# oresat-gps-card.net
KiCad netlist of a schematic drawn in EAGLE
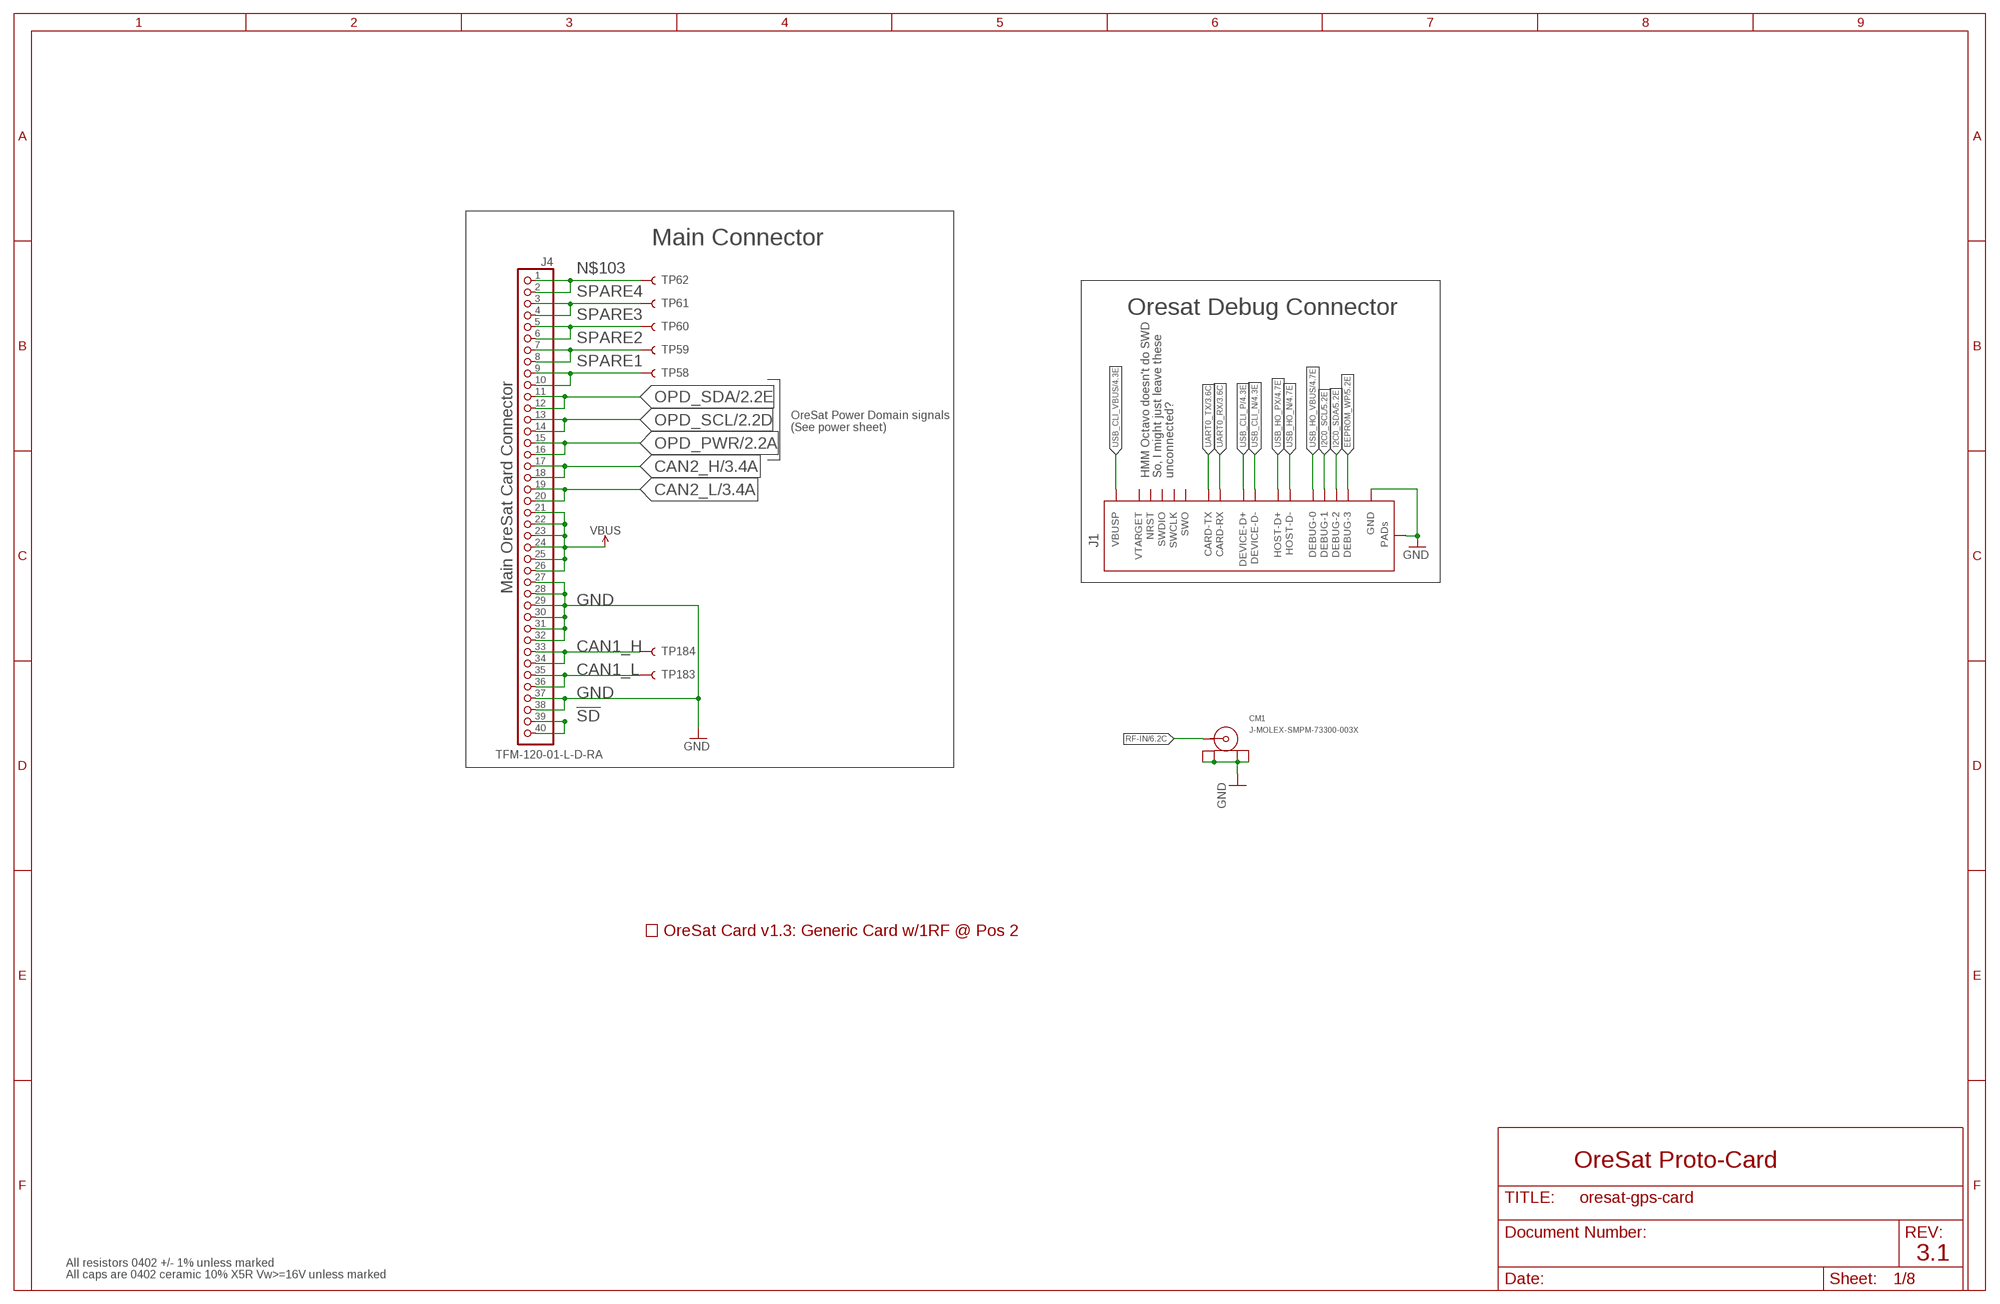
[diagram p0: schematic, sheet 1]
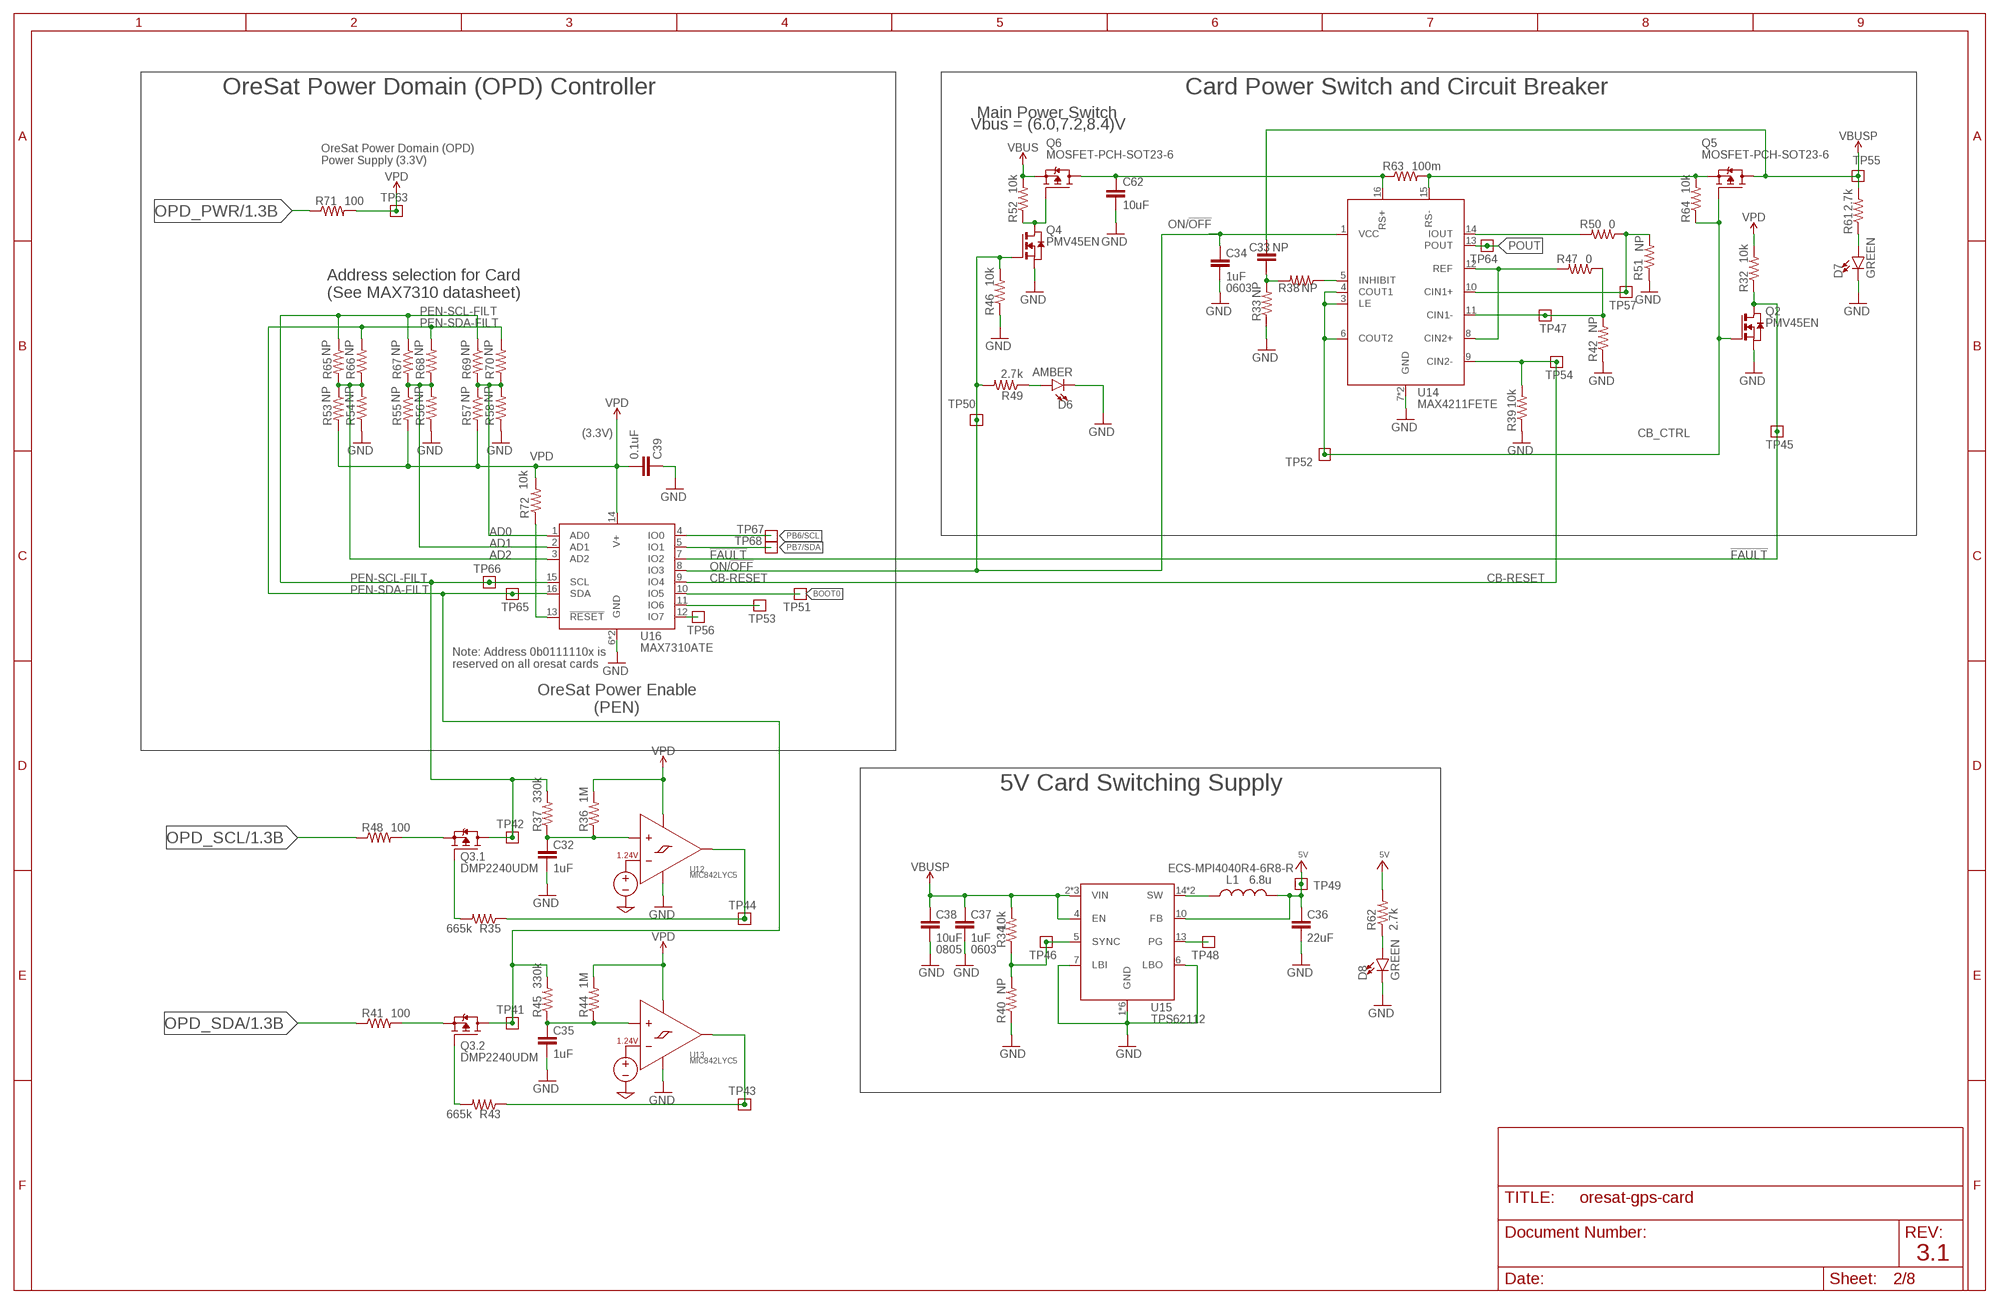
[diagram p1: schematic, sheet 2]
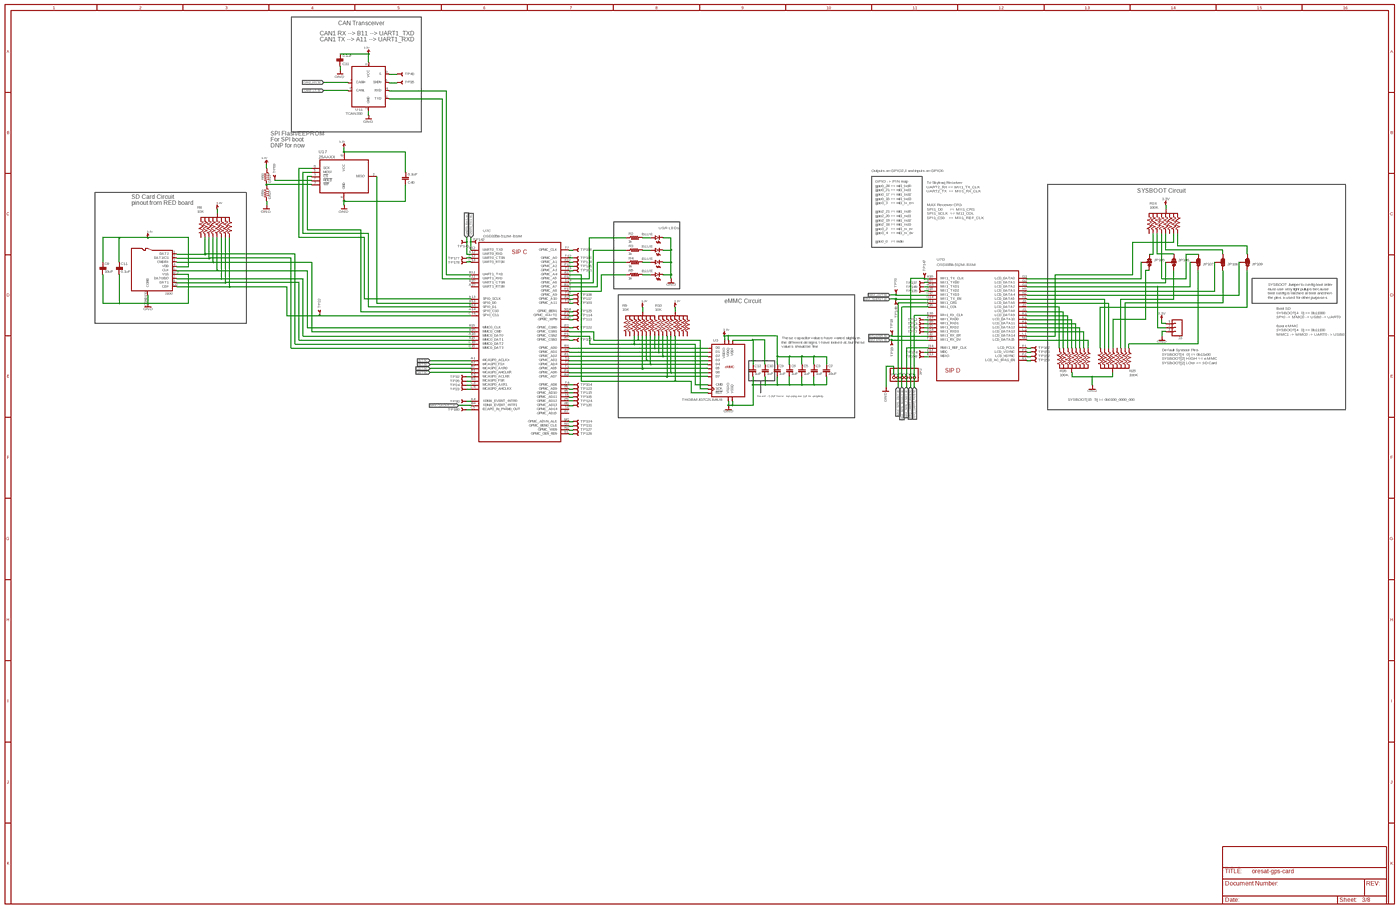
[diagram p2: schematic, sheet 3, overview]
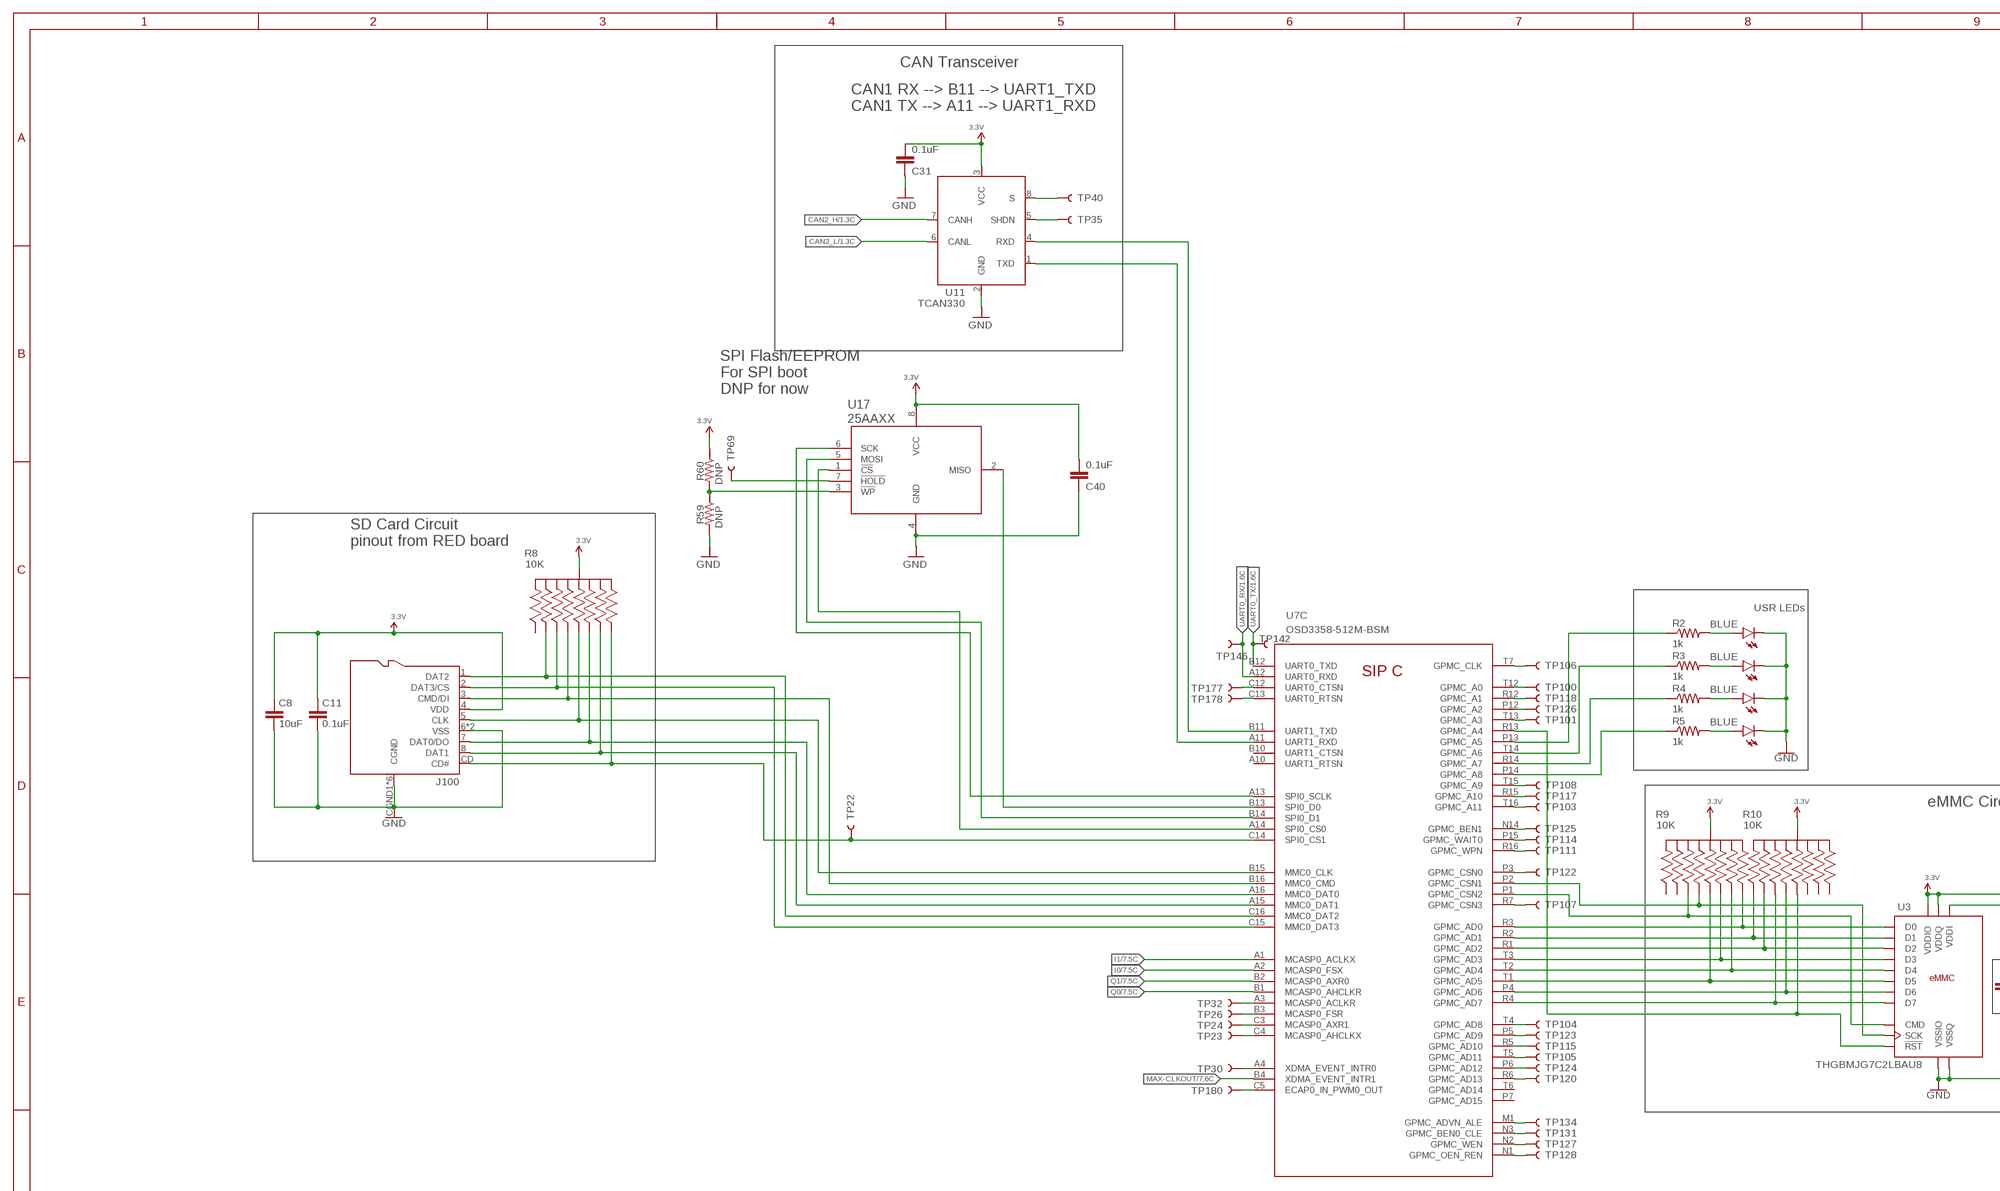
[diagram p3: schematic, sheet 3, part 1 of 4]
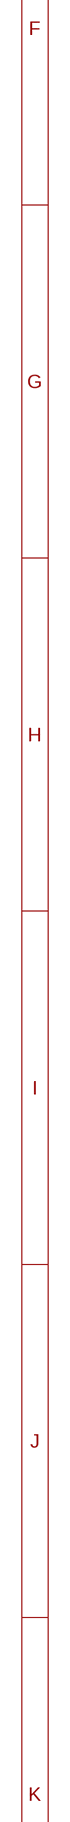
[diagram p4: schematic, sheet 3, part 2 of 4]
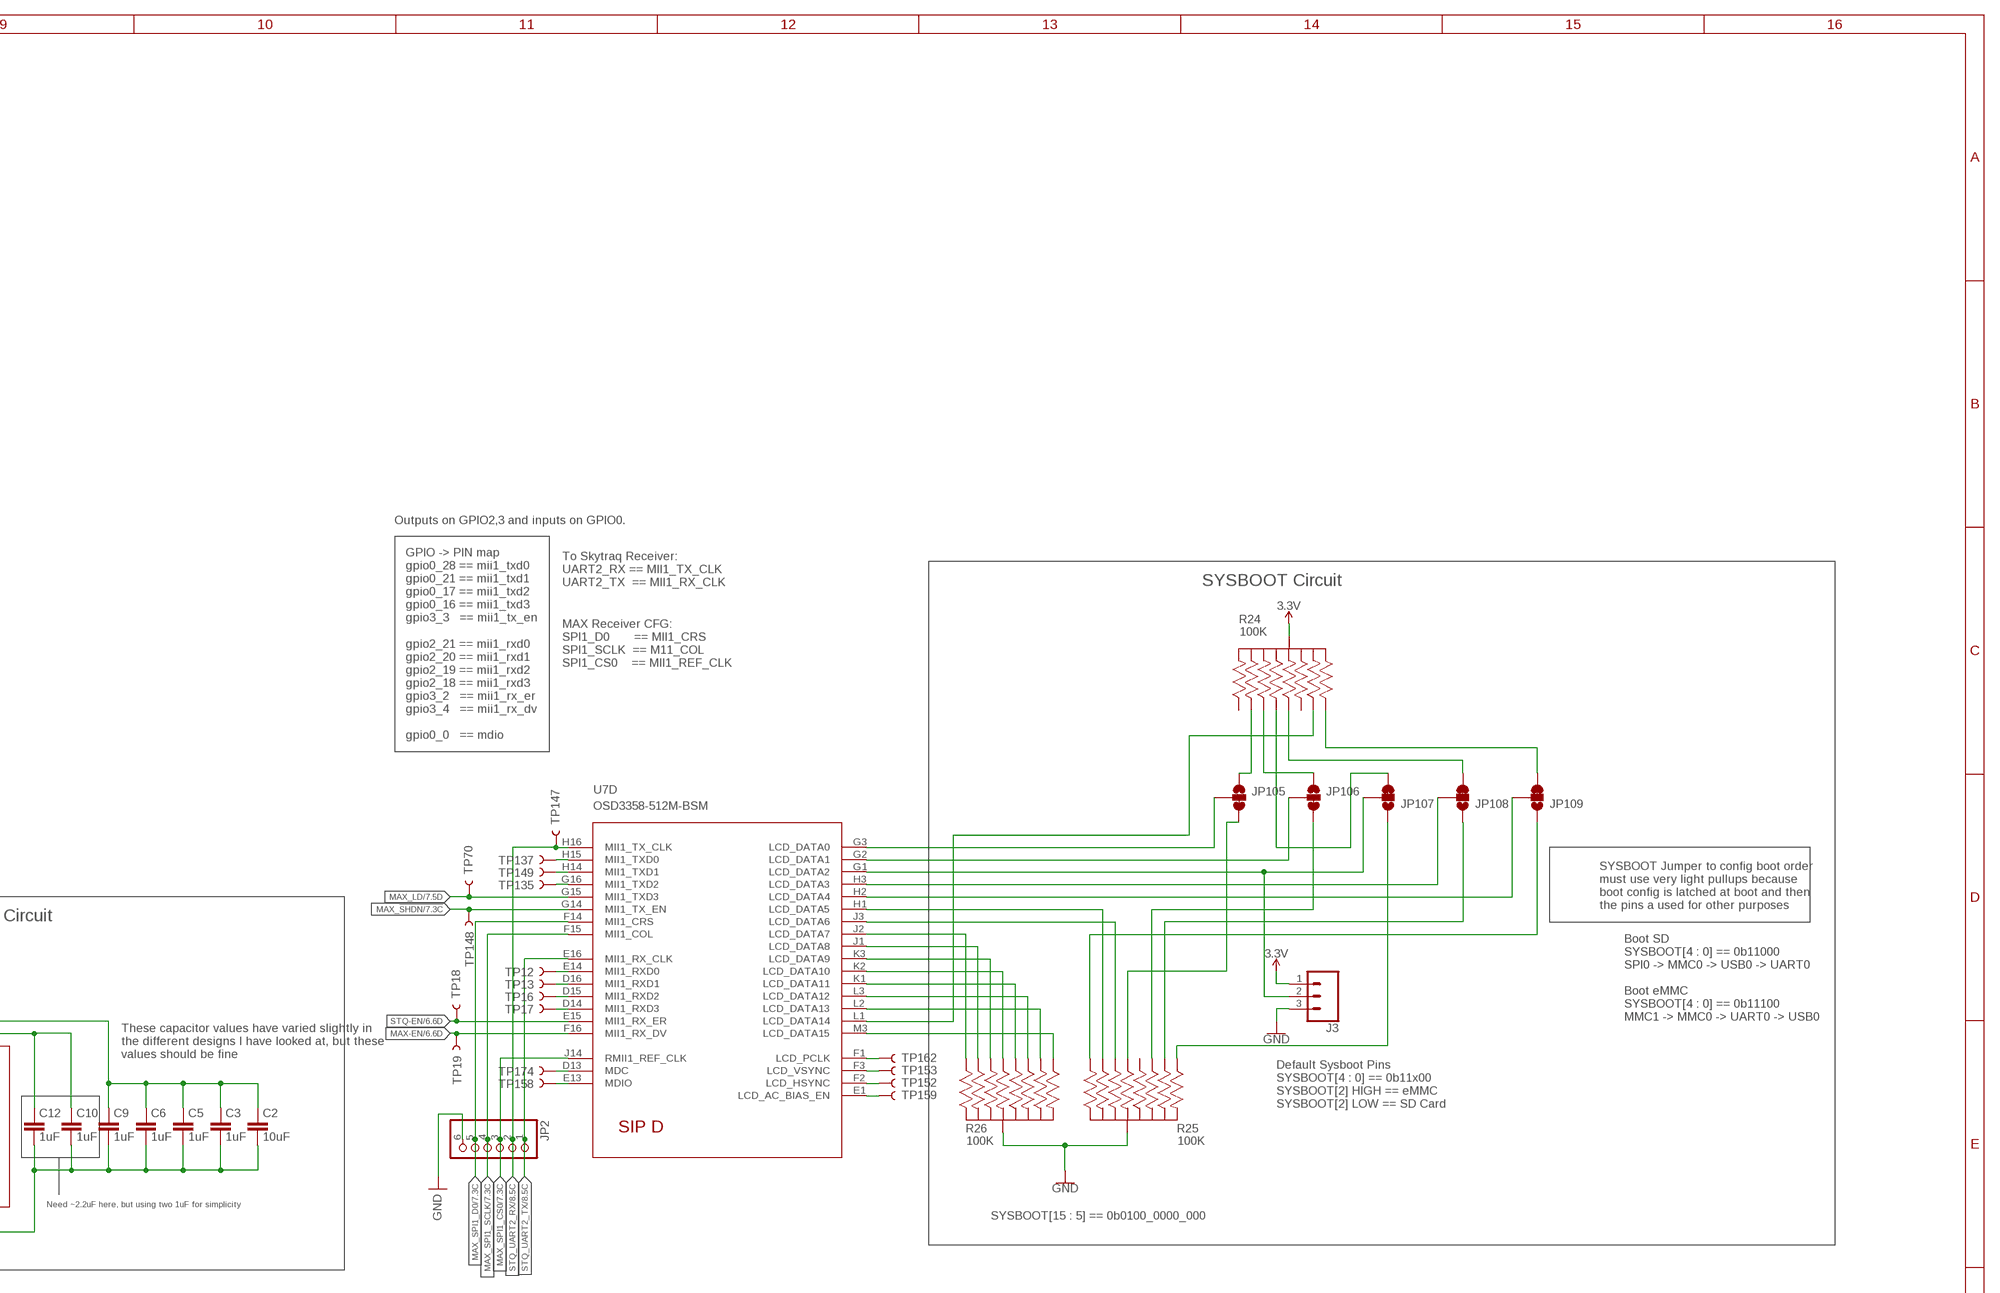
[diagram p5: schematic, sheet 3, part 3 of 4]
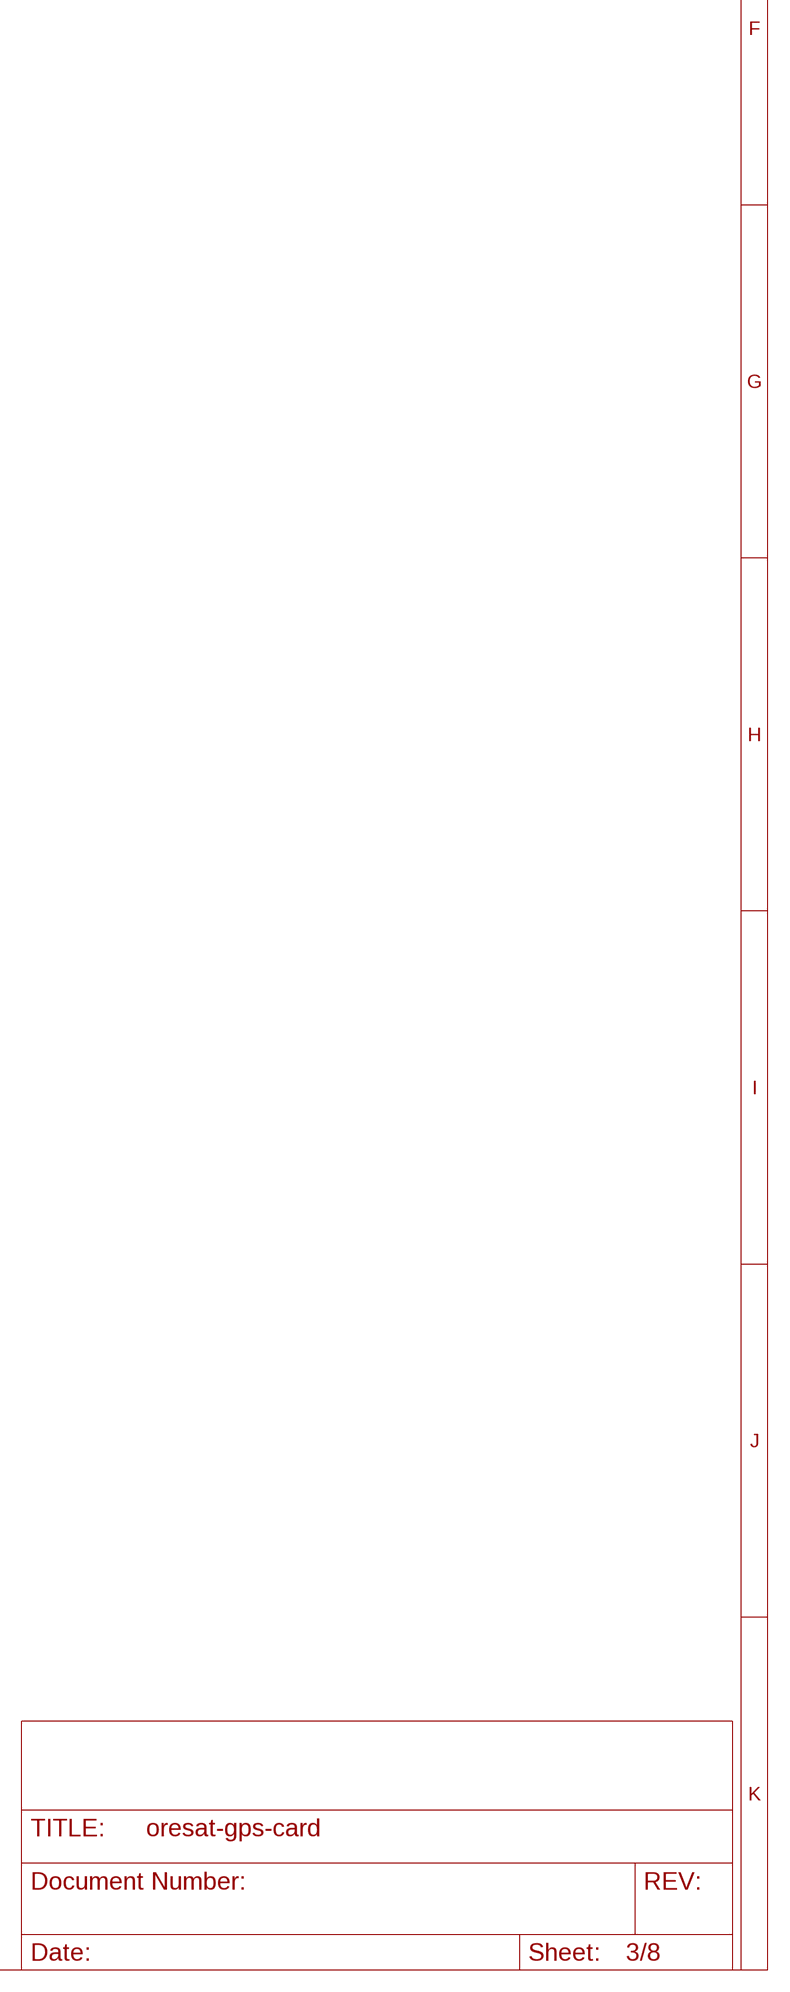
[diagram p6: schematic, sheet 3, part 4 of 4]
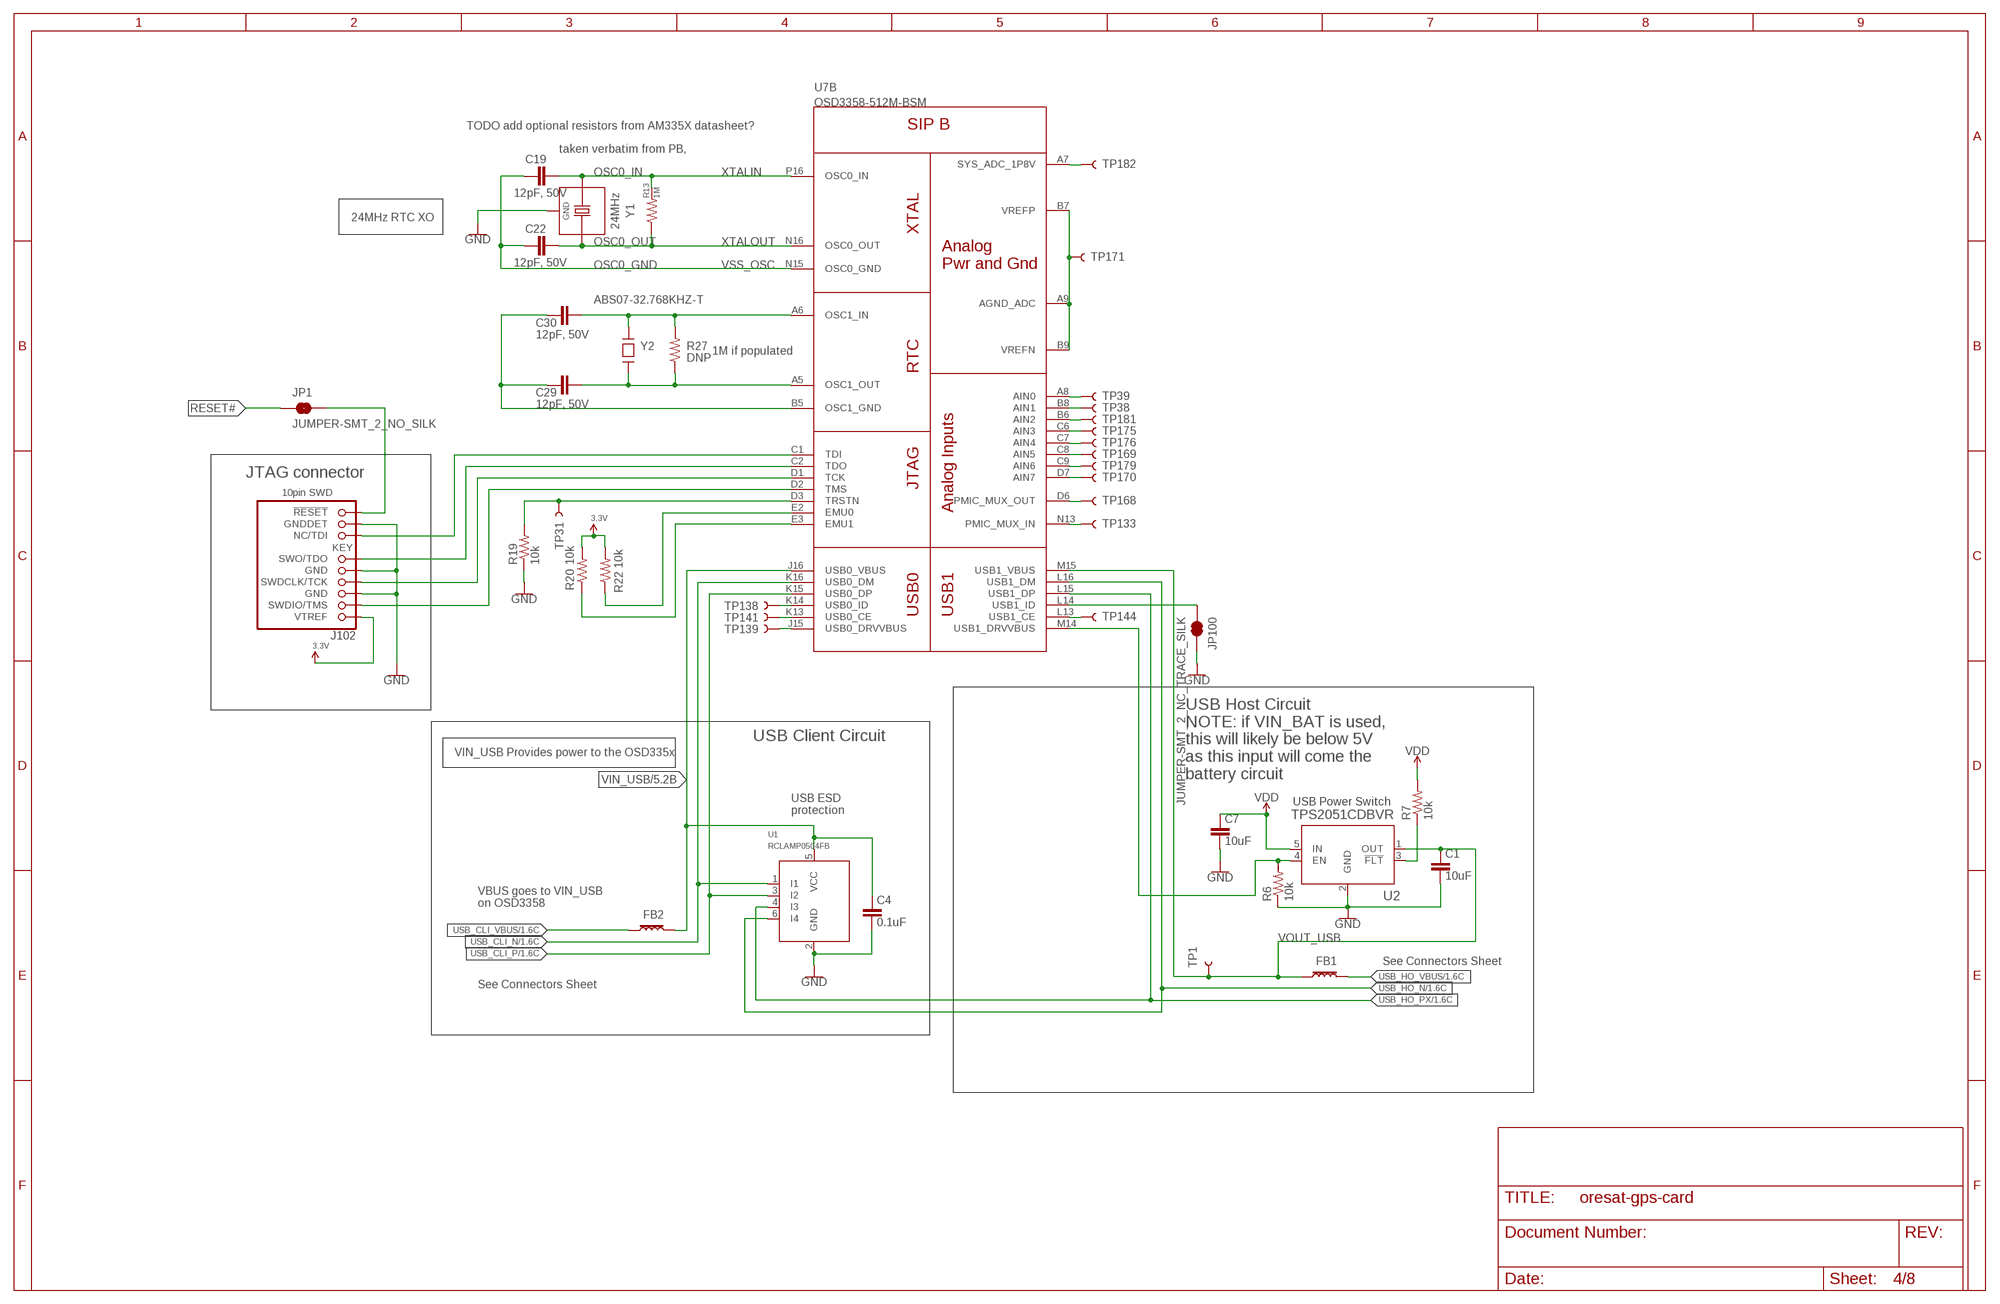
[diagram p7: schematic, sheet 4]
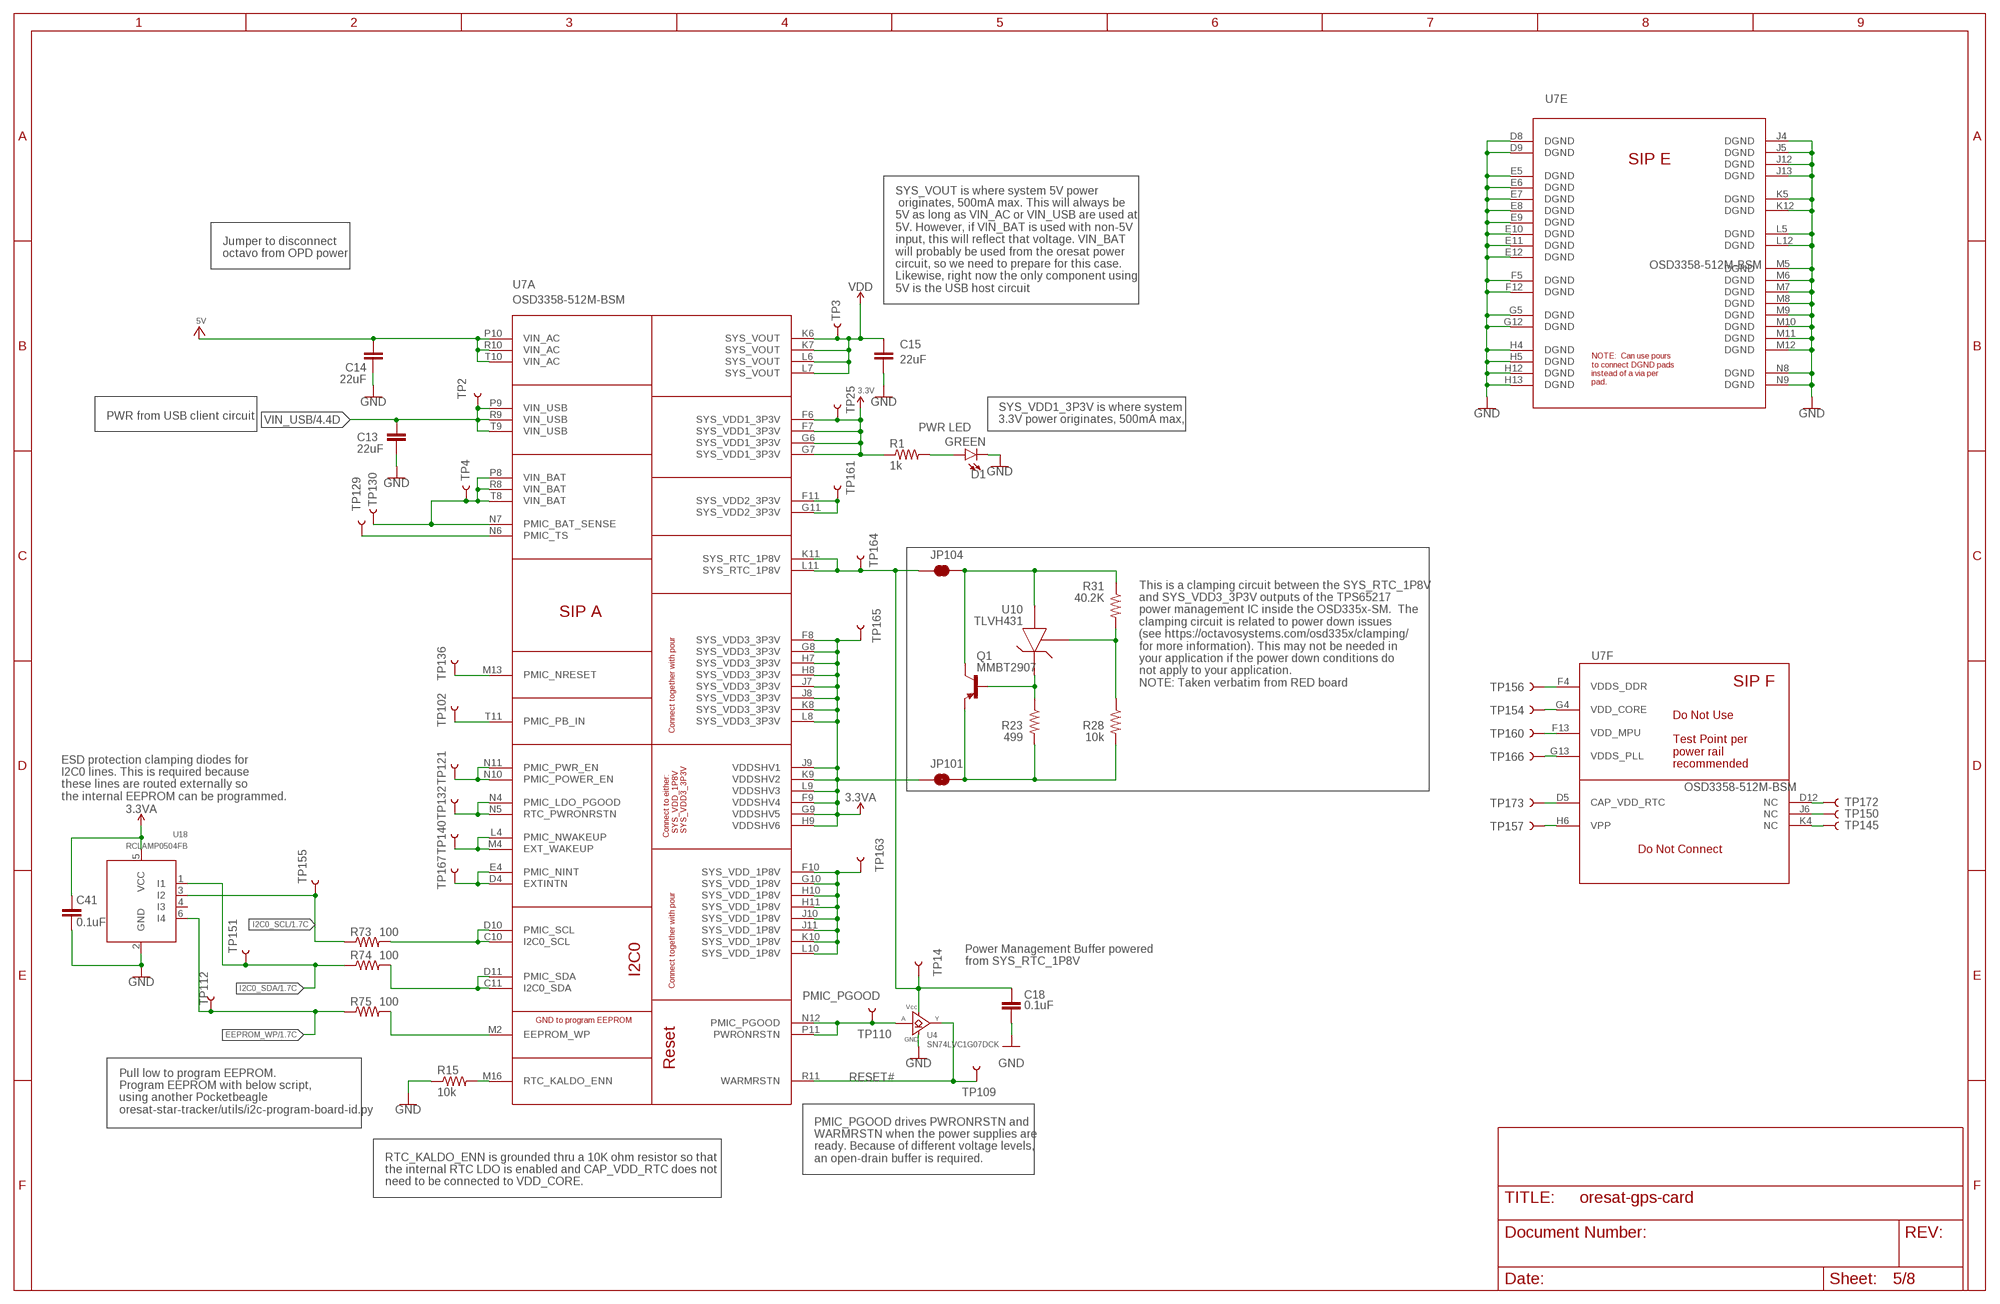
[diagram p8: schematic, sheet 5]
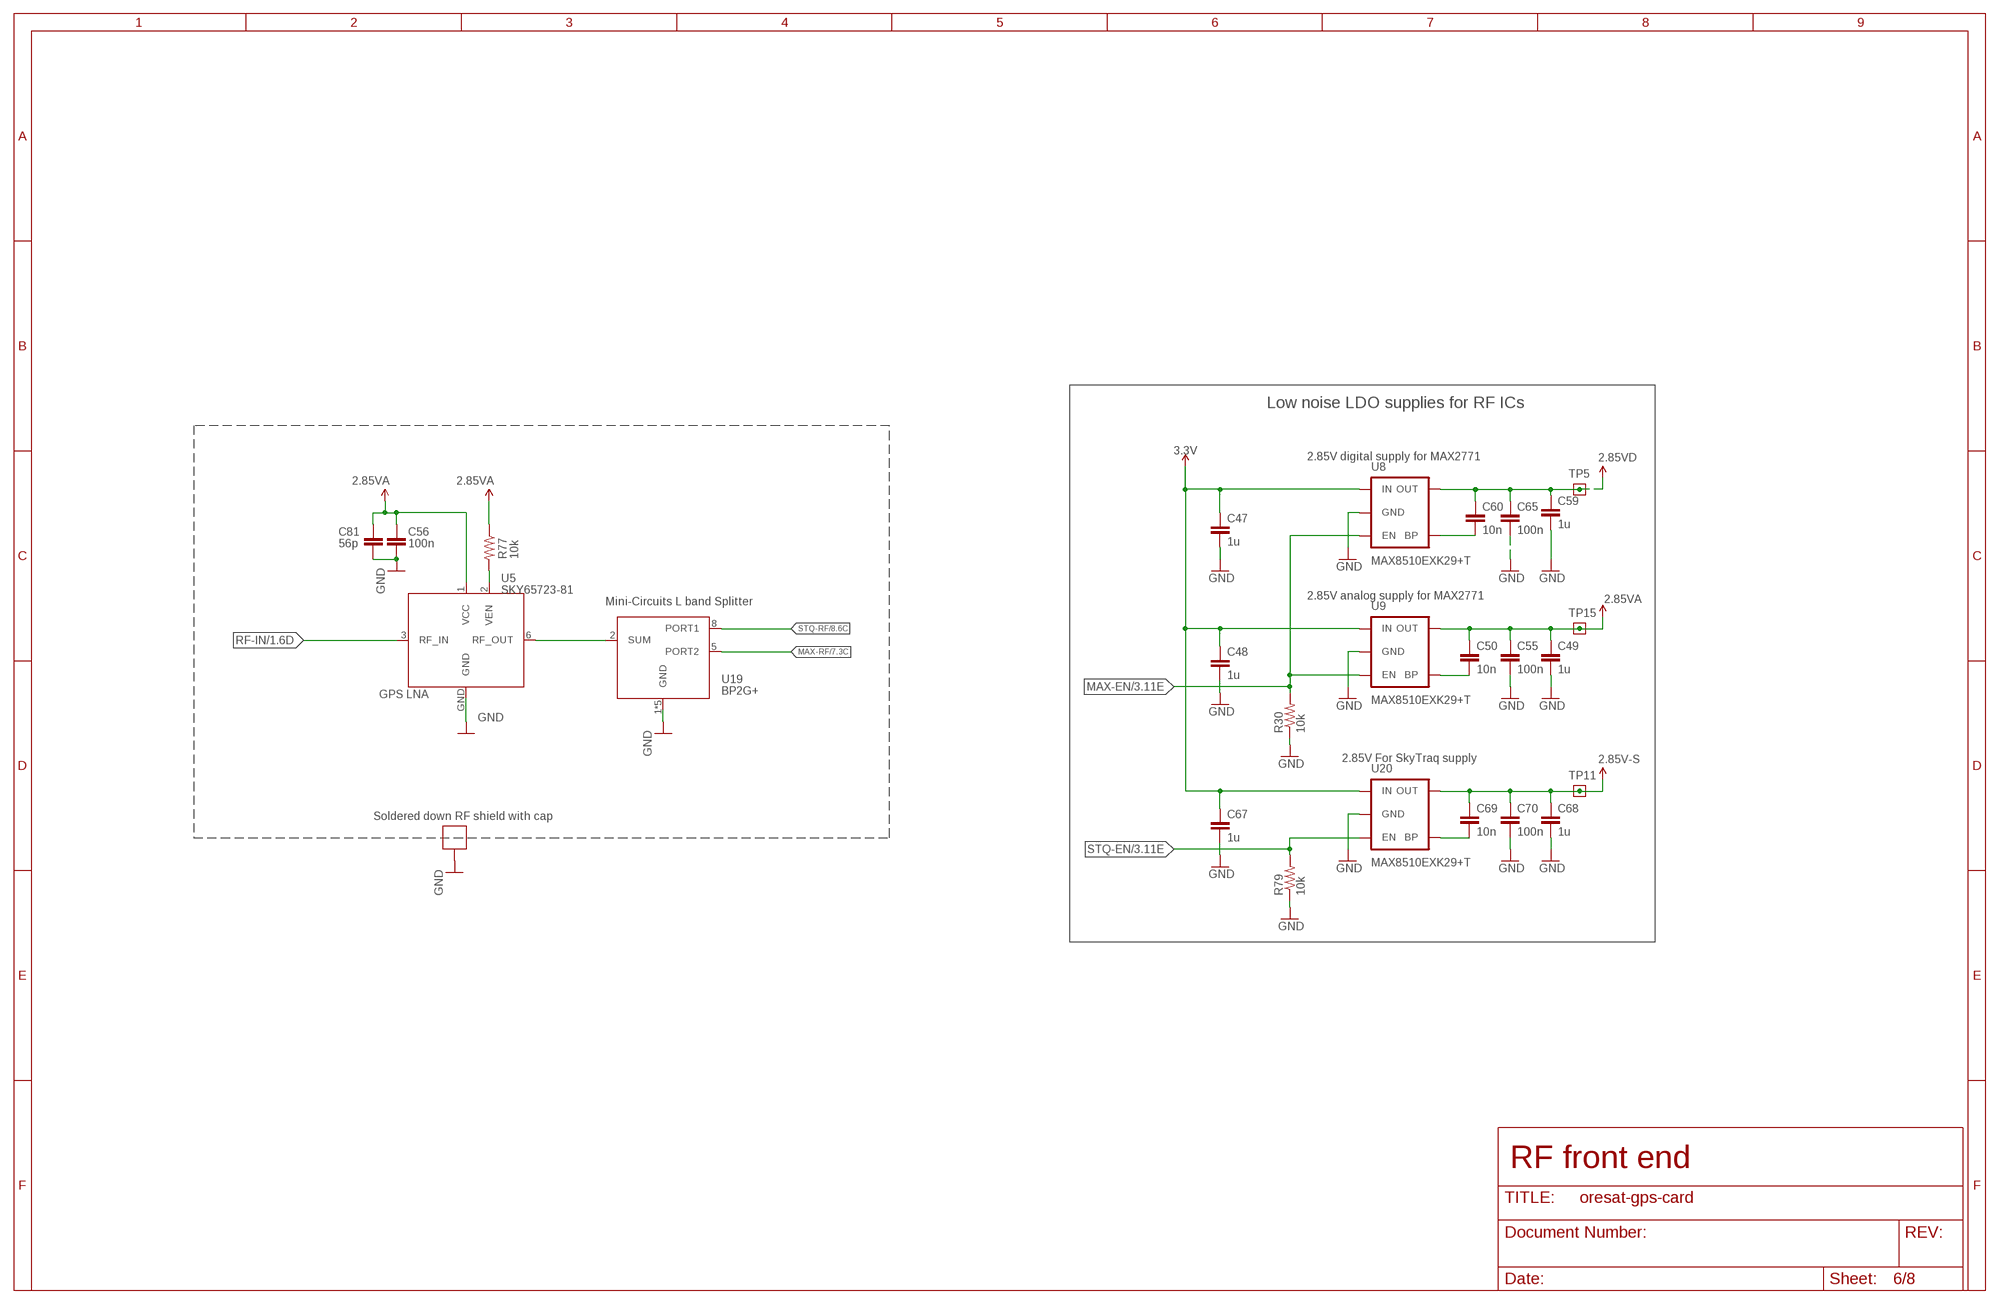
[diagram p9: schematic, sheet 6]
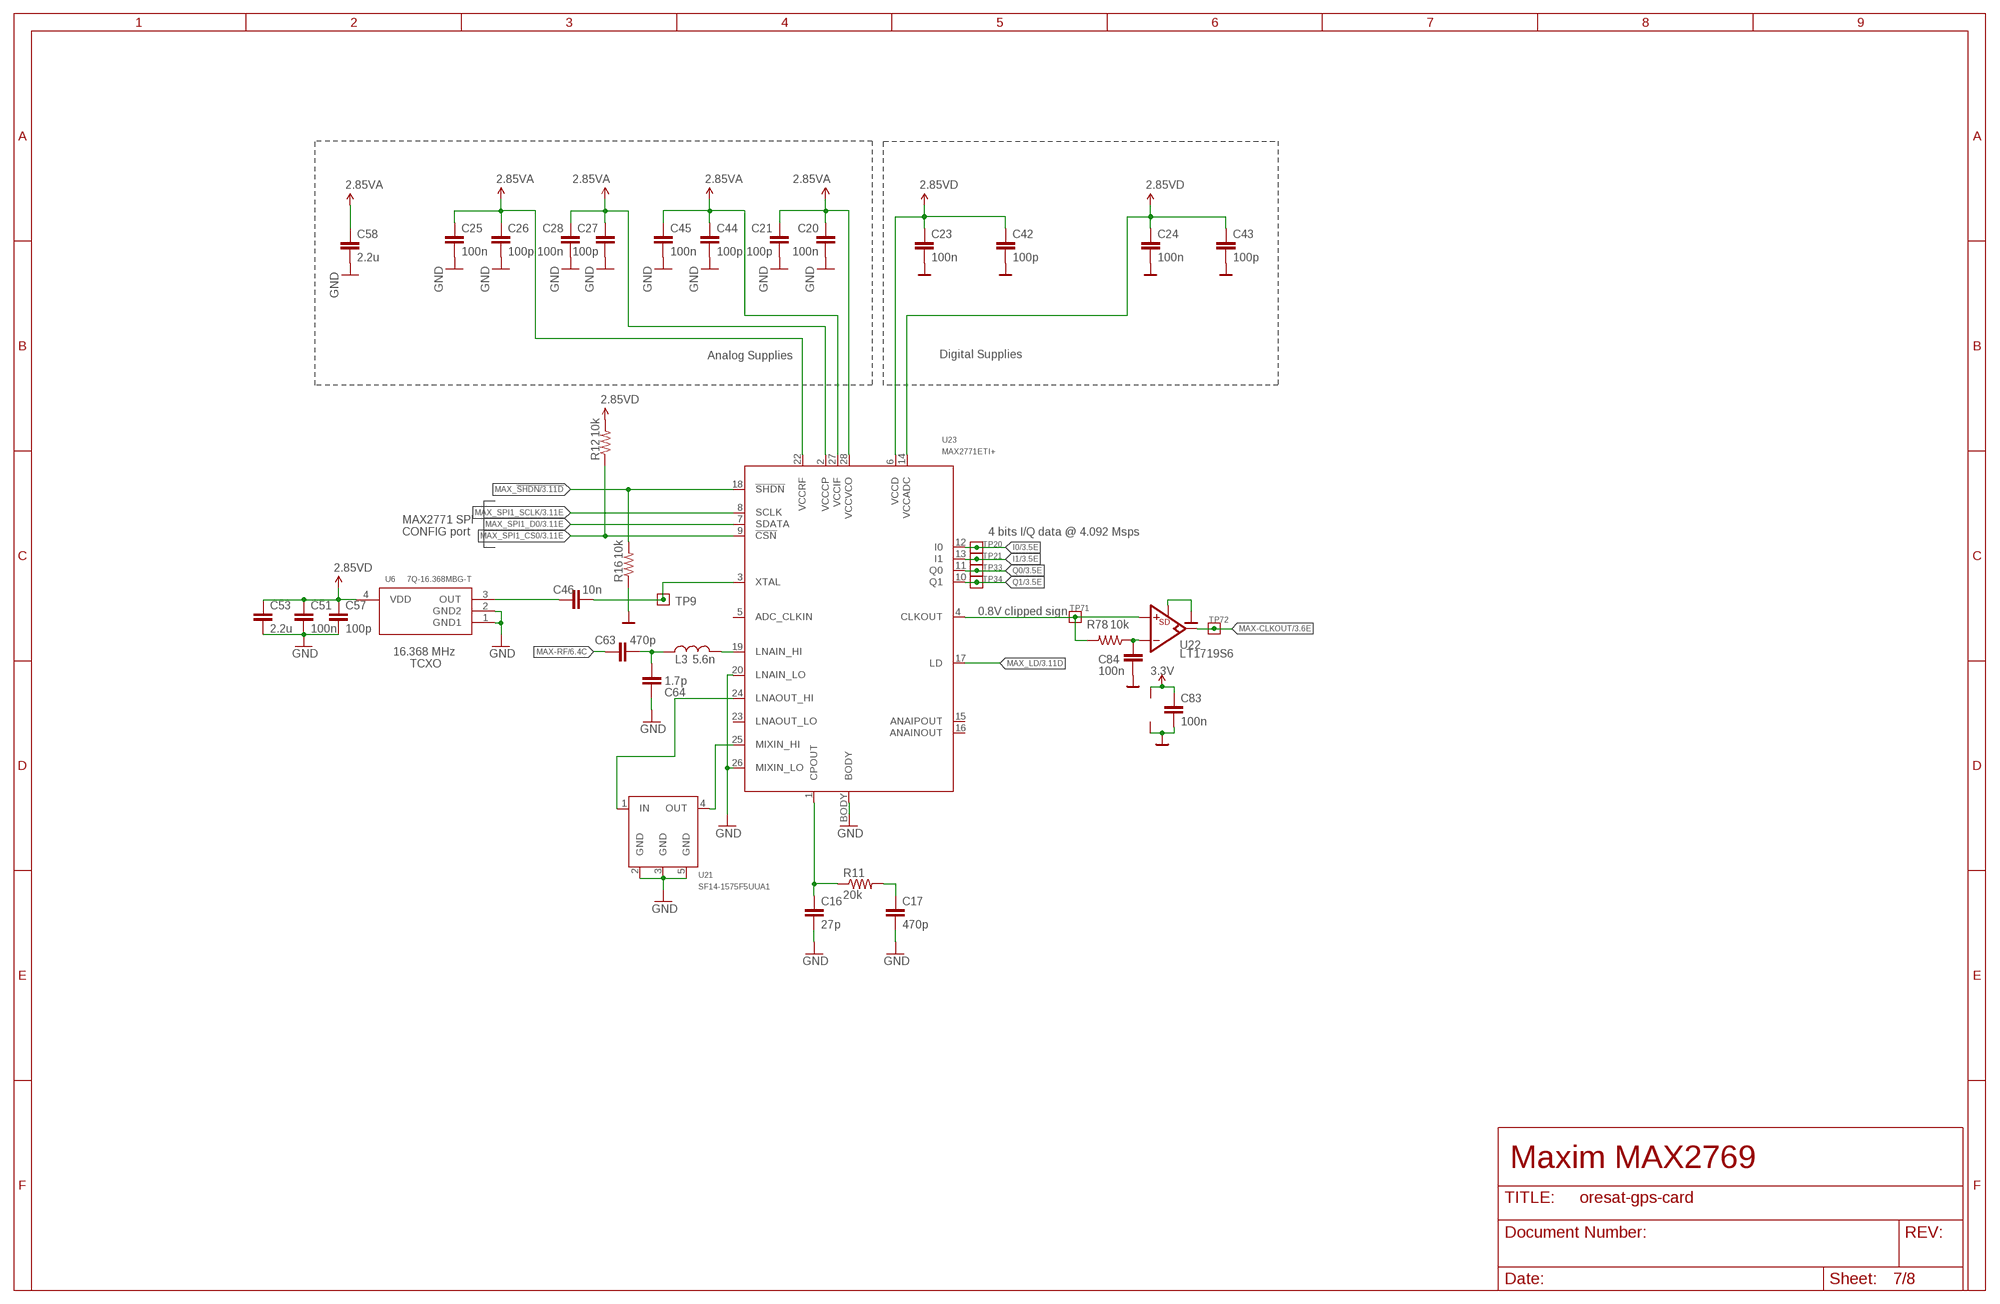
[diagram p10: schematic, sheet 7]
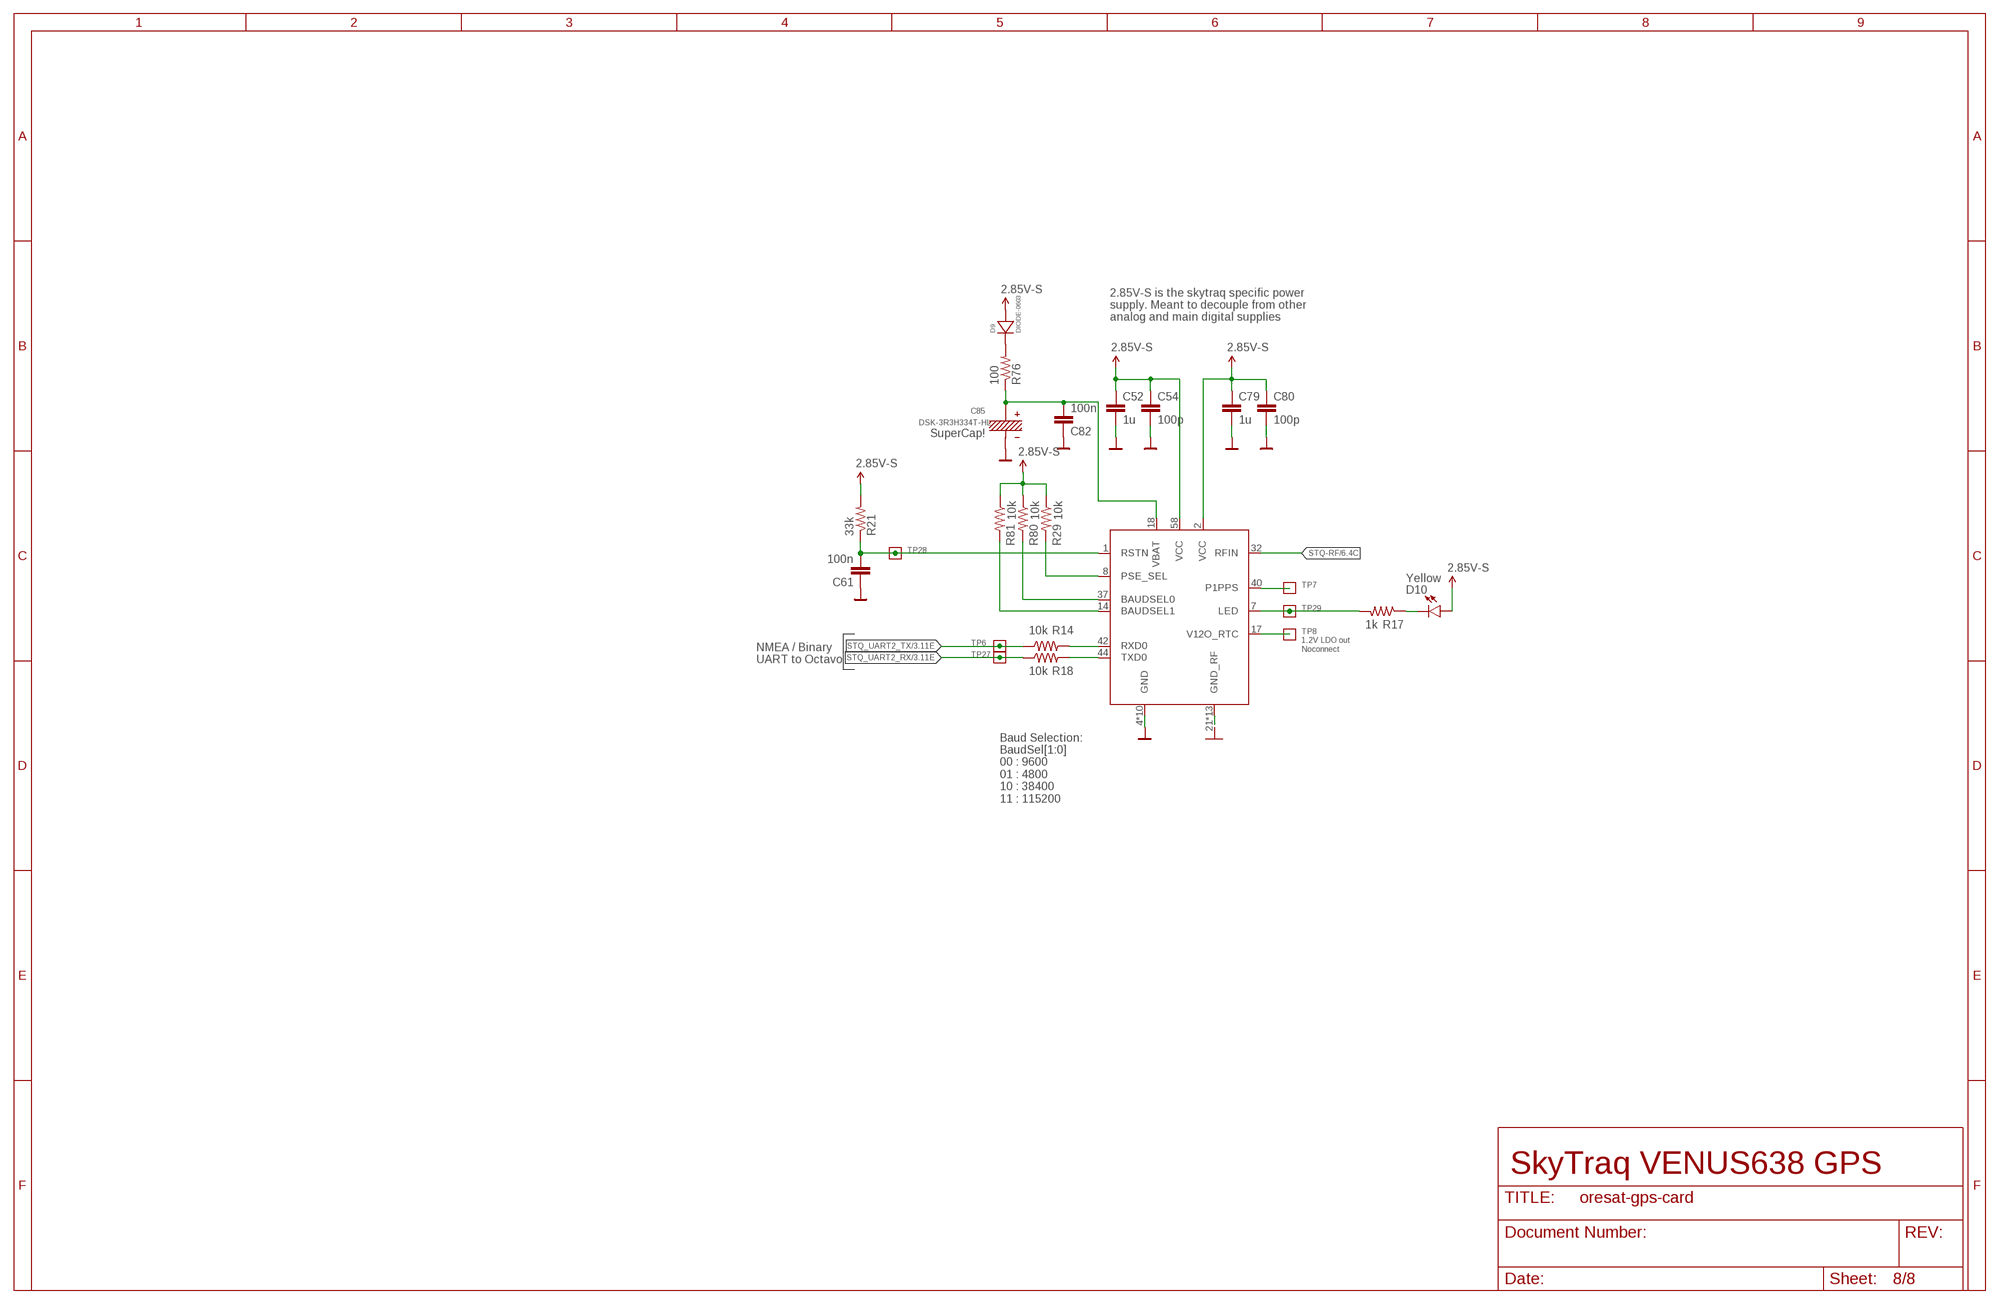
[diagram p11: schematic, sheet 8]

(export (version "E")
  (design (tool "Eeschema 10.0.6"))
  (components
    (comp (ref "C16")
      (value "27p")
      (footprint "eagle-import:.0603-B-NOSILK")
      (libsource (lib "eagle-import") (part "C-EU0603-B-NOSILK"))
    )
    (comp (ref "C17")
      (value "470p")
      (footprint "eagle-import:.0603-B-NOSILK")
      (libsource (lib "eagle-import") (part "C-EU0603-B-NOSILK"))
    )
    (comp (ref "C20")
      (value "100n")
      (footprint "eagle-import:.0603-B-NOSILK")
      (libsource (lib "eagle-import") (part "C-EU0603-B-NOSILK"))
    )
    (comp (ref "C21")
      (value "100p")
      (footprint "eagle-import:.0603-B-NOSILK")
      (libsource (lib "eagle-import") (part "C-EU0603-B-NOSILK"))
    )
    (comp (ref "C23")
      (value "100n")
      (footprint "eagle-import:.0603-B-NOSILK")
      (libsource (lib "eagle-import") (part "C-EU0603-B-NOSILK"))
    )
    (comp (ref "C24")
      (value "100n")
      (footprint "eagle-import:.0603-B-NOSILK")
      (libsource (lib "eagle-import") (part "C-EU0603-B-NOSILK"))
    )
    (comp (ref "C25")
      (value "100n")
      (footprint "eagle-import:.0603-B-NOSILK")
      (libsource (lib "eagle-import") (part "C-EU0603-B-NOSILK"))
    )
    (comp (ref "C26")
      (value "100p")
      (footprint "eagle-import:.0603-B-NOSILK")
      (libsource (lib "eagle-import") (part "C-EU0603-B-NOSILK"))
    )
    (comp (ref "C27")
      (value "100p")
      (footprint "eagle-import:.0603-B-NOSILK")
      (libsource (lib "eagle-import") (part "C-EU0603-B-NOSILK"))
    )
    (comp (ref "C28")
      (value "100n")
      (footprint "eagle-import:.0603-B-NOSILK")
      (libsource (lib "eagle-import") (part "C-EU0603-B-NOSILK"))
    )
    (comp (ref "C42")
      (value "100p")
      (footprint "eagle-import:.0603-B-NOSILK")
      (libsource (lib "eagle-import") (part "C-EU0603-B-NOSILK"))
    )
    (comp (ref "C43")
      (value "100p")
      (footprint "eagle-import:.0603-B-NOSILK")
      (libsource (lib "eagle-import") (part "C-EU0603-B-NOSILK"))
    )
    (comp (ref "C44")
      (value "100p")
      (footprint "eagle-import:.0603-B-NOSILK")
      (libsource (lib "eagle-import") (part "C-EU0603-B-NOSILK"))
    )
    (comp (ref "C45")
      (value "100n")
      (footprint "eagle-import:.0603-B-NOSILK")
      (libsource (lib "eagle-import") (part "C-EU0603-B-NOSILK"))
    )
    (comp (ref "C46")
      (value "10n")
      (footprint "eagle-import:.0603-B-NOSILK")
      (libsource (lib "eagle-import") (part "C-EU0603-B-NOSILK"))
    )
    (comp (ref "C51")
      (value "100n")
      (footprint "eagle-import:.0603-B-NOSILK")
      (libsource (lib "eagle-import") (part "C-EU0603-B-NOSILK"))
    )
    (comp (ref "C53")
      (value "2.2u")
      (footprint "eagle-import:.0603-B-NOSILK")
      (libsource (lib "eagle-import") (part "C-EU0603-B-NOSILK"))
    )
    (comp (ref "C57")
      (value "100p")
      (footprint "eagle-import:.0603-B-NOSILK")
      (libsource (lib "eagle-import") (part "C-EU0603-B-NOSILK"))
    )
    (comp (ref "C58")
      (value "2.2u")
      (footprint "eagle-import:.0603-B-NOSILK")
      (libsource (lib "eagle-import") (part "rcl_custom_C-EU0603-B-NOSILK"))
    )
    (comp (ref "C63")
      (value "470p")
      (footprint "eagle-import:.0402-B-NOSILK")
      (libsource (lib "eagle-import") (part "C-EU0402-B-NOSILK"))
    )
    (comp (ref "C64")
      (value "1.7p")
      (footprint "eagle-import:.0402-B-NOSILK")
      (libsource (lib "eagle-import") (part "C-EU0402-B-NOSILK"))
    )
    (comp (ref "C83")
      (value "100n")
      (footprint "eagle-import:.0603-B-NOSILK")
      (libsource (lib "eagle-import") (part "C-EU0603-B-NOSILK"))
    )
    (comp (ref "C84")
      (value "100n")
      (footprint "eagle-import:.0603-B-NOSILK")
      (libsource (lib "eagle-import") (part "C-EU0603-B-NOSILK"))
    )
    (comp (ref "L3")
      (value "5.6n")
      (footprint "eagle-import:.0402-B-NOSILK")
      (libsource (lib "eagle-import") (part "L-US0402-B-NOSILK"))
    )
    (comp (ref "R11")
      (value "20k")
      (footprint "eagle-import:.0603-B-NOSILK")
      (libsource (lib "eagle-import") (part "R-US_0603-B-NOSILK"))
    )
    (comp (ref "R12")
      (value "10k")
      (footprint "eagle-import:.0603-B-NOSILK")
      (libsource (lib "eagle-import") (part "R-US_0603-B-NOSILK"))
    )
    (comp (ref "R16")
      (value "10k")
      (footprint "eagle-import:.0603-B-NOSILK")
      (libsource (lib "eagle-import") (part "R-US_0603-B-NOSILK"))
    )
    (comp (ref "R78")
      (value "10k")
      (footprint "eagle-import:.0603-B-NOSILK")
      (libsource (lib "eagle-import") (part "R-US_0603-B-NOSILK"))
    )
    (comp (ref "TP9")
      (value "TEST-POINT15MIL-TEST-POINT")
      (footprint "eagle-import:15MIL-TEST-POINT")
      (libsource (lib "eagle-import") (part "TEST-POINT15MIL-TEST-POINT"))
    )
    (comp (ref "TP20")
      (value "TEST-POINT-LARGE-SQUARE")
      (footprint "eagle-import:1X01")
      (libsource (lib "eagle-import") (part "TEST-POINT-LARGE-SQUARE"))
    )
    (comp (ref "TP21")
      (value "TEST-POINT-LARGE-SQUARE")
      (footprint "eagle-import:1X01")
      (libsource (lib "eagle-import") (part "TEST-POINT-LARGE-SQUARE"))
    )
    (comp (ref "TP33")
      (value "TEST-POINT-LARGE-SQUARE")
      (footprint "eagle-import:1X01")
      (libsource (lib "eagle-import") (part "TEST-POINT-LARGE-SQUARE"))
    )
    (comp (ref "TP34")
      (value "TEST-POINT-LARGE-SQUARE")
      (footprint "eagle-import:1X01")
      (libsource (lib "eagle-import") (part "TEST-POINT-LARGE-SQUARE"))
    )
    (comp (ref "TP71")
      (value "TEST-POINT-LARGE-SQUARE")
      (footprint "eagle-import:1X01")
      (libsource (lib "eagle-import") (part "TEST-POINT-LARGE-SQUARE"))
    )
    (comp (ref "TP72")
      (value "TEST-POINT-LARGE-SQUARE")
      (footprint "eagle-import:1X01")
      (libsource (lib "eagle-import") (part "TEST-POINT-LARGE-SQUARE"))
    )
    (comp (ref "U6")
      (value "7Q-16.368MBG-T")
      (footprint "eagle-import:TCX_7Q")
      (fields (field (name "MFR") "TXC Corporation"))
      (libsource (lib "eagle-import") (part "7Q-16.368MBG-T"))
    )
    (comp (ref "U21")
      (value "SF14-1575F5UUA1")
      (footprint "eagle-import:SAW_1.4X1.1")
      (fields (field (name "MFR") "Kyocera International"))
      (libsource (lib "eagle-import") (part "SAW_1.4X1.1"))
    )
    (comp (ref "U22")
      (value "LT1719S6")
      (footprint "eagle-import:SOT23-6")
      (libsource (lib "eagle-import") (part "IC_COMP_W_SDSOT23-6"))
    )
    (comp (ref "U23")
      (value "MAX2771ETI+")
      (footprint "eagle-import:90-0023")
      (fields (field (name "MFR") "Maxim Integrated"))
      (libsource (lib "eagle-import") (part "MAX2771ETI+"))
    )
    (comp (ref "C13")
      (value "22uF")
      (footprint "eagle-import:C1210")
      (libsource (lib "eagle-import") (part "C-EUC1210"))
    )
    (comp (ref "C14")
      (value "22uF")
      (footprint "eagle-import:C1210")
      (libsource (lib "eagle-import") (part "C-EUC1210"))
    )
    (comp (ref "C15")
      (value "22uF")
      (footprint "eagle-import:C1210")
      (libsource (lib "eagle-import") (part "C-EUC1210"))
    )
    (comp (ref "C18")
      (value "0.1uF")
      (footprint "eagle-import:.0603-A")
      (libsource (lib "eagle-import") (part "C-EU0603-A"))
    )
    (comp (ref "C41")
      (value "0.1uF")
      (footprint "eagle-import:.0603-A")
      (libsource (lib "eagle-import") (part "C-EU0603-A"))
    )
    (comp (ref "D1")
      (value "GREEN")
      (footprint "eagle-import:LED-0603")
      (libsource (lib "eagle-import") (part "LED-GREEN0603"))
    )
    (comp (ref "JP101")
      (value "JUMPER-SMT_2_NC_TRACE_SILK")
      (footprint "eagle-import:SMT-JUMPER_2_NC_TRACE_SILK")
      (libsource (lib "eagle-import") (part "JUMPER-SMT_2_NC_TRACE_SILK"))
    )
    (comp (ref "JP104")
      (value "JUMPER-SMT_2_NC_TRACE_SILK")
      (footprint "eagle-import:SMT-JUMPER_2_NC_TRACE_SILK")
      (libsource (lib "eagle-import") (part "JUMPER-SMT_2_NC_TRACE_SILK"))
    )
    (comp (ref "Q1")
      (value "MMBT2907")
      (footprint "eagle-import:SOT23-BEC")
      (fields (field (name "MPN") "MMBT2907A-7-F"))
      (libsource (lib "eagle-import") (part "MMBT2907SMD"))
    )
    (comp (ref "R1")
      (value "1k")
      (footprint "eagle-import:.0603-A")
      (libsource (lib "eagle-import") (part "R-US_0603-A"))
    )
    (comp (ref "R15")
      (value "10k")
      (footprint "eagle-import:.0603-A")
      (libsource (lib "eagle-import") (part "R-US_0603-A"))
    )
    (comp (ref "R23")
      (value "499")
      (footprint "eagle-import:.0603-A")
      (libsource (lib "eagle-import") (part "R-US_0603-A"))
    )
    (comp (ref "R28")
      (value "10k")
      (footprint "eagle-import:.0603-A")
      (libsource (lib "eagle-import") (part "R-US_0603-A"))
    )
    (comp (ref "R31")
      (value "40.2K")
      (footprint "eagle-import:.0603-A")
      (libsource (lib "eagle-import") (part "R-US_0603-A"))
    )
    (comp (ref "R73")
      (value "100")
      (footprint "eagle-import:.0603-A")
      (libsource (lib "eagle-import") (part "R-US_0603-A"))
    )
    (comp (ref "R74")
      (value "100")
      (footprint "eagle-import:.0603-A")
      (libsource (lib "eagle-import") (part "R-US_0603-A"))
    )
    (comp (ref "R75")
      (value "100")
      (footprint "eagle-import:.0603-A")
      (libsource (lib "eagle-import") (part "R-US_0603-A"))
    )
    (comp (ref "TP2")
      (value "TEST-POINT3X4")
      (footprint "eagle-import:PAD.03X.04")
      (libsource (lib "eagle-import") (part "TEST-POINT3X4"))
    )
    (comp (ref "TP3")
      (value "TEST-POINT3X4")
      (footprint "eagle-import:PAD.03X.04")
      (libsource (lib "eagle-import") (part "TEST-POINT3X4"))
    )
    (comp (ref "TP4")
      (value "TEST-POINT3X4")
      (footprint "eagle-import:PAD.03X.04")
      (libsource (lib "eagle-import") (part "TEST-POINT3X4"))
    )
    (comp (ref "TP14")
      (value "TEST-POINT3X4")
      (footprint "eagle-import:PAD.03X.04")
      (libsource (lib "eagle-import") (part "TEST-POINT3X4"))
    )
    (comp (ref "TP25")
      (value "TEST-POINT3X4")
      (footprint "eagle-import:PAD.03X.04")
      (libsource (lib "eagle-import") (part "TEST-POINT3X4"))
    )
    (comp (ref "TP102")
      (value "TEST-POINT3X4")
      (footprint "eagle-import:PAD.03X.04")
      (libsource (lib "eagle-import") (part "TEST-POINT3X4"))
    )
    (comp (ref "TP109")
      (value "TEST-POINT3X4")
      (footprint "eagle-import:PAD.03X.04")
      (libsource (lib "eagle-import") (part "TEST-POINT3X4"))
    )
    (comp (ref "TP110")
      (value "TEST-POINT3X4")
      (footprint "eagle-import:PAD.03X.04")
      (libsource (lib "eagle-import") (part "TEST-POINT3X4"))
    )
    (comp (ref "TP112")
      (value "TEST-POINT3X4")
      (footprint "eagle-import:PAD.03X.04")
      (libsource (lib "eagle-import") (part "TEST-POINT3X4"))
    )
    (comp (ref "TP121")
      (value "TEST-POINT3X4")
      (footprint "eagle-import:PAD.03X.04")
      (libsource (lib "eagle-import") (part "TEST-POINT3X4"))
    )
    (comp (ref "TP129")
      (value "TEST-POINT3X4")
      (footprint "eagle-import:PAD.03X.04")
      (libsource (lib "eagle-import") (part "TEST-POINT3X4"))
    )
    (comp (ref "TP130")
      (value "TEST-POINT3X4")
      (footprint "eagle-import:PAD.03X.04")
      (libsource (lib "eagle-import") (part "TEST-POINT3X4"))
    )
    (comp (ref "TP132")
      (value "TEST-POINT3X4")
      (footprint "eagle-import:PAD.03X.04")
      (libsource (lib "eagle-import") (part "TEST-POINT3X4"))
    )
    (comp (ref "TP136")
      (value "TEST-POINT3X4")
      (footprint "eagle-import:PAD.03X.04")
      (libsource (lib "eagle-import") (part "TEST-POINT3X4"))
    )
    (comp (ref "TP140")
      (value "TEST-POINT3X4")
      (footprint "eagle-import:PAD.03X.04")
      (libsource (lib "eagle-import") (part "TEST-POINT3X4"))
    )
    (comp (ref "TP145")
      (value "TEST-POINT3X4")
      (footprint "eagle-import:PAD.03X.04")
      (libsource (lib "eagle-import") (part "TEST-POINT3X4"))
    )
    (comp (ref "TP150")
      (value "TEST-POINT3X4")
      (footprint "eagle-import:PAD.03X.04")
      (libsource (lib "eagle-import") (part "TEST-POINT3X4"))
    )
    (comp (ref "TP151")
      (value "TEST-POINT3X4")
      (footprint "eagle-import:PAD.03X.04")
      (libsource (lib "eagle-import") (part "TEST-POINT3X4"))
    )
    (comp (ref "TP154")
      (value "TEST-POINT3X4")
      (footprint "eagle-import:PAD.03X.04")
      (libsource (lib "eagle-import") (part "TEST-POINT3X4"))
    )
    (comp (ref "TP155")
      (value "TEST-POINT3X4")
      (footprint "eagle-import:PAD.03X.04")
      (libsource (lib "eagle-import") (part "TEST-POINT3X4"))
    )
    (comp (ref "TP156")
      (value "TEST-POINT3X4")
      (footprint "eagle-import:PAD.03X.04")
      (libsource (lib "eagle-import") (part "TEST-POINT3X4"))
    )
    (comp (ref "TP157")
      (value "TEST-POINT3X4")
      (footprint "eagle-import:PAD.03X.04")
      (libsource (lib "eagle-import") (part "TEST-POINT3X4"))
    )
    (comp (ref "TP160")
      (value "TEST-POINT3X4")
      (footprint "eagle-import:PAD.03X.04")
      (libsource (lib "eagle-import") (part "TEST-POINT3X4"))
    )
    (comp (ref "TP161")
      (value "TEST-POINT3X4")
      (footprint "eagle-import:PAD.03X.04")
      (libsource (lib "eagle-import") (part "TEST-POINT3X4"))
    )
    (comp (ref "TP163")
      (value "TEST-POINT3X4")
      (footprint "eagle-import:PAD.03X.04")
      (libsource (lib "eagle-import") (part "TEST-POINT3X4"))
    )
    (comp (ref "TP164")
      (value "TEST-POINT3X4")
      (footprint "eagle-import:PAD.03X.04")
      (libsource (lib "eagle-import") (part "TEST-POINT3X4"))
    )
    (comp (ref "TP165")
      (value "TEST-POINT3X4")
      (footprint "eagle-import:PAD.03X.04")
      (libsource (lib "eagle-import") (part "TEST-POINT3X4"))
    )
    (comp (ref "TP166")
      (value "TEST-POINT3X4")
      (footprint "eagle-import:PAD.03X.04")
      (libsource (lib "eagle-import") (part "TEST-POINT3X4"))
    )
    (comp (ref "TP167")
      (value "TEST-POINT3X4")
      (footprint "eagle-import:PAD.03X.04")
      (libsource (lib "eagle-import") (part "TEST-POINT3X4"))
    )
    (comp (ref "TP172")
      (value "TEST-POINT3X4")
      (footprint "eagle-import:PAD.03X.04")
      (libsource (lib "eagle-import") (part "TEST-POINT3X4"))
    )
    (comp (ref "TP173")
      (value "TEST-POINT3X4")
      (footprint "eagle-import:PAD.03X.04")
      (libsource (lib "eagle-import") (part "TEST-POINT3X4"))
    )
    (comp (ref "U4")
      (value "SN74LVC1G07DCK")
      (footprint "eagle-import:C70(TI-DCK)")
      (fields (field (name "MPN") "SN74LVC1G07DCKR"))
      (libsource (lib "eagle-import") (part "SN74LVC1G07DCK"))
    )
    (comp (ref "U7")
      (value "OSD3358-512M-BSM")
      (footprint "eagle-import:OSD335X-BGA-256")
      (fields (field (name "MFR") "Octavo Systems"))
      (libsource (lib "eagle-import") (part "OSD3358-512M-BSM"))
    )
    (comp (ref "U10")
      (value "TLVH431")
      (footprint "eagle-import:SOT23-3")
      (fields (field (name "MPN") "TLVH431BQDBZRQ1"))
      (libsource (lib "eagle-import") (part "TLVH431"))
    )
    (comp (ref "U18")
      (value "RCLAMP0504FB")
      (footprint "eagle-import:SC70-6")
      (fields (field (name "MPN") "RCLAMP0504FBTCT"))
      (libsource (lib "eagle-import") (part "RCLAMP0504FB"))
    )
    (comp (ref "C2")
      (value "10uF")
      (footprint "eagle-import:.0805-B")
      (libsource (lib "eagle-import") (part "C-EU0805-B"))
    )
    (comp (ref "C3")
      (value "1uF")
      (footprint "eagle-import:.0603-A")
      (libsource (lib "eagle-import") (part "C-EU0603-A"))
    )
    (comp (ref "C5")
      (value "1uF")
      (footprint "eagle-import:.0603-A")
      (libsource (lib "eagle-import") (part "C-EU0603-A"))
    )
    (comp (ref "C6")
      (value "1uF")
      (footprint "eagle-import:.0603-A")
      (libsource (lib "eagle-import") (part "C-EU0603-A"))
    )
    (comp (ref "C8")
      (value "10uF")
      (footprint "eagle-import:.0805-B")
      (libsource (lib "eagle-import") (part "C-EU0805-B"))
    )
    (comp (ref "C9")
      (value "1uF")
      (footprint "eagle-import:.0603-A")
      (libsource (lib "eagle-import") (part "C-EU0603-A"))
    )
    (comp (ref "C10")
      (value "1uF")
      (footprint "eagle-import:.0603-A")
      (libsource (lib "eagle-import") (part "C-EU0603-A"))
    )
    (comp (ref "C11")
      (value "0.1uF")
      (footprint "eagle-import:.0603-A")
      (libsource (lib "eagle-import") (part "C-EU0603-A"))
    )
    (comp (ref "C12")
      (value "1uF")
      (footprint "eagle-import:.0603-A")
      (libsource (lib "eagle-import") (part "C-EU0603-A"))
    )
    (comp (ref "C31")
      (value "0.1uF")
      (footprint "eagle-import:.0603-A")
      (libsource (lib "eagle-import") (part "C-EU0603-A"))
    )
    (comp (ref "C40")
      (value "0.1uF")
      (footprint "eagle-import:.0603-A")
      (libsource (lib "eagle-import") (part "C-EU0603-A"))
    )
    (comp (ref "D2")
      (value "BLUE")
      (footprint "eagle-import:LED-0603")
      (libsource (lib "eagle-import") (part "LED-BLUE0603"))
    )
    (comp (ref "D3")
      (value "BLUE")
      (footprint "eagle-import:LED-0603")
      (libsource (lib "eagle-import") (part "LED-BLUE0603"))
    )
    (comp (ref "D4")
      (value "BLUE")
      (footprint "eagle-import:LED-0603")
      (libsource (lib "eagle-import") (part "LED-BLUE0603"))
    )
    (comp (ref "D5")
      (value "BLUE")
      (footprint "eagle-import:LED-0603")
      (libsource (lib "eagle-import") (part "LED-BLUE0603"))
    )
    (comp (ref "J3")
      (value "CONN_03LONGPADS")
      (footprint "eagle-import:1X03_LONGPADS")
      (libsource (lib "eagle-import") (part "CONN_03LONGPADS"))
    )
    (comp (ref "J100")
      (value "DM3BT-DSF-PEJS")
      (footprint "eagle-import:DM3BT-DSF-PEJS")
      (fields (field (name "DPN") "HR1942CT-ND") (field (name "MFR") "Hirose Electric"))
      (libsource (lib "eagle-import") (part "DM3BT-DSF-PEJS"))
    )
    (comp (ref "JP2")
      (value "PINHD-1X6")
      (footprint "eagle-import:1X06")
      (libsource (lib "eagle-import") (part "PINHD-1X6"))
    )
    (comp (ref "JP105")
      (value "JUMPER-SMT_3_1-NC_TRACE_SILK")
      (footprint "eagle-import:SMT-JUMPER_3_1-NC_TRACE_SILK")
      (libsource (lib "eagle-import") (part "JUMPER-SMT_3_1-NC_TRACE_SILK"))
    )
    (comp (ref "JP106")
      (value "JUMPER-SMT_3_1-NC_TRACE_SILK")
      (footprint "eagle-import:SMT-JUMPER_3_1-NC_TRACE_SILK")
      (libsource (lib "eagle-import") (part "JUMPER-SMT_3_1-NC_TRACE_SILK"))
    )
    (comp (ref "JP107")
      (value "JUMPER-SMT_3_1-NC_TRACE_SILK")
      (footprint "eagle-import:SMT-JUMPER_3_1-NC_TRACE_SILK")
      (libsource (lib "eagle-import") (part "JUMPER-SMT_3_1-NC_TRACE_SILK"))
    )
    (comp (ref "JP108")
      (value "JUMPER-SMT_3_1-NC_TRACE_SILK")
      (footprint "eagle-import:SMT-JUMPER_3_1-NC_TRACE_SILK")
      (libsource (lib "eagle-import") (part "JUMPER-SMT_3_1-NC_TRACE_SILK"))
    )
    (comp (ref "JP109")
      (value "JUMPER-SMT_3_1-NC_TRACE_SILK")
      (footprint "eagle-import:SMT-JUMPER_3_1-NC_TRACE_SILK")
      (libsource (lib "eagle-import") (part "JUMPER-SMT_3_1-NC_TRACE_SILK"))
    )
    (comp (ref "R2")
      (value "1k")
      (footprint "eagle-import:.0603-A")
      (libsource (lib "eagle-import") (part "R-US_0603-A"))
    )
    (comp (ref "R3")
      (value "1k")
      (footprint "eagle-import:.0603-A")
      (libsource (lib "eagle-import") (part "R-US_0603-A"))
    )
    (comp (ref "R4")
      (value "1k")
      (footprint "eagle-import:.0603-A")
      (libsource (lib "eagle-import") (part "R-US_0603-A"))
    )
    (comp (ref "R5")
      (value "1k")
      (footprint "eagle-import:.0603-A")
      (libsource (lib "eagle-import") (part "R-US_0603-A"))
    )
    (comp (ref "R8")
      (value "10K")
      (footprint "eagle-import:ARRAY_EXBA-M")
      (fields
        (field (name "MFR") "Panasonic Electronic Components")
        (field (name "MPN") "EXB-A10PXXXJ")
        (field (name "MPN_1") "EXB-A10P103J")
      )
      (libsource (lib "eagle-import") (part "EXB-A10P391JC_ARRAY_EXBA-M"))
    )
    (comp (ref "R9")
      (value "10K")
      (footprint "eagle-import:ARRAY_EXBA-M")
      (fields
        (field (name "MFR") "Panasonic Electronic Components")
        (field (name "MPN") "EXB-A10PXXXJ")
        (field (name "MPN_1") "EXB-A10P103J")
      )
      (libsource (lib "eagle-import") (part "EXB-A10P391JC_ARRAY_EXBA-M"))
    )
    (comp (ref "R10")
      (value "10K")
      (footprint "eagle-import:ARRAY_EXBA-M")
      (fields
        (field (name "MFR") "Panasonic Electronic Components")
        (field (name "MPN") "EXB-A10PXXXJ")
        (field (name "DPN") "U7103CT-ND")
        (field (name "MPN_1") "EXB-A10P103J")
      )
      (libsource (lib "eagle-import") (part "EXB-A10P391JC_ARRAY_EXBA-M"))
    )
    (comp (ref "R24")
      (value "100K")
      (footprint "eagle-import:ARRAY_EXBA-M")
      (fields
        (field (name "MFR") "Panasonic Electronic Components")
        (field (name "MPN") "EXB-A10PXXXJ")
        (field (name "MPN_1") "EXB-A10P104J")
      )
      (libsource (lib "eagle-import") (part "EXB-A10P391JC_ARRAY_EXBA-M"))
    )
    (comp (ref "R25")
      (value "100K")
      (footprint "eagle-import:ARRAY_EXBA-M")
      (fields
        (field (name "MFR") "Panasonic Electronic Components")
        (field (name "MPN") "EXB-A10PXXXJ")
        (field (name "MPN_1") "EXB-A10P104J")
      )
      (libsource (lib "eagle-import") (part "EXB-A10P391JC_ARRAY_EXBA-M"))
    )
    (comp (ref "R26")
      (value "100K")
      (footprint "eagle-import:ARRAY_EXBA-M")
      (fields
        (field (name "MFR") "Panasonic Electronic Components")
        (field (name "MPN") "EXB-A10PXXXJ")
        (field (name "MPN_1") "EXB-A10P104J")
      )
      (libsource (lib "eagle-import") (part "EXB-A10P391JC_ARRAY_EXBA-M"))
    )
    (comp (ref "R59")
      (value "DNP")
      (footprint "eagle-import:.0603-A")
      (libsource (lib "eagle-import") (part "R-US_0603-A"))
    )
    (comp (ref "R60")
      (value "DNP")
      (footprint "eagle-import:.0603-A")
      (libsource (lib "eagle-import") (part "R-US_0603-A"))
    )
    (comp (ref "TP12")
      (value "TEST-POINT3X4")
      (footprint "eagle-import:PAD.03X.04")
      (libsource (lib "eagle-import") (part "TEST-POINT3X4"))
    )
    (comp (ref "TP13")
      (value "TEST-POINT3X4")
      (footprint "eagle-import:PAD.03X.04")
      (libsource (lib "eagle-import") (part "TEST-POINT3X4"))
    )
    (comp (ref "TP16")
      (value "TEST-POINT3X4")
      (footprint "eagle-import:PAD.03X.04")
      (libsource (lib "eagle-import") (part "TEST-POINT3X4"))
    )
    (comp (ref "TP17")
      (value "TEST-POINT3X4")
      (footprint "eagle-import:PAD.03X.04")
      (libsource (lib "eagle-import") (part "TEST-POINT3X4"))
    )
    (comp (ref "TP18")
      (value "TEST-POINT3X4")
      (footprint "eagle-import:PAD.03X.04")
      (libsource (lib "eagle-import") (part "TEST-POINT3X4"))
    )
    (comp (ref "TP19")
      (value "TEST-POINT3X4")
      (footprint "eagle-import:PAD.03X.04")
      (libsource (lib "eagle-import") (part "TEST-POINT3X4"))
    )
    (comp (ref "TP22")
      (value "TEST-POINT3X4")
      (footprint "eagle-import:PAD.03X.04")
      (libsource (lib "eagle-import") (part "TEST-POINT3X4"))
    )
    (comp (ref "TP23")
      (value "TEST-POINT3X4")
      (footprint "eagle-import:PAD.03X.04")
      (libsource (lib "eagle-import") (part "TEST-POINT3X4"))
    )
    (comp (ref "TP24")
      (value "TEST-POINT3X4")
      (footprint "eagle-import:PAD.03X.04")
      (libsource (lib "eagle-import") (part "TEST-POINT3X4"))
    )
    (comp (ref "TP26")
      (value "TEST-POINT3X4")
      (footprint "eagle-import:PAD.03X.04")
      (libsource (lib "eagle-import") (part "TEST-POINT3X4"))
    )
    (comp (ref "TP30")
      (value "TEST-POINT3X4")
      (footprint "eagle-import:PAD.03X.04")
      (libsource (lib "eagle-import") (part "TEST-POINT3X4"))
    )
    (comp (ref "TP32")
      (value "TEST-POINT3X4")
      (footprint "eagle-import:PAD.03X.04")
      (libsource (lib "eagle-import") (part "TEST-POINT3X4"))
    )
    (comp (ref "TP35")
      (value "TEST-POINT3X4")
      (footprint "eagle-import:PAD.03X.04")
      (libsource (lib "eagle-import") (part "TEST-POINT3X4"))
    )
    (comp (ref "TP40")
      (value "TEST-POINT3X4")
      (footprint "eagle-import:PAD.03X.04")
      (libsource (lib "eagle-import") (part "TEST-POINT3X4"))
    )
    (comp (ref "TP69")
      (value "TEST-POINT3X4")
      (footprint "eagle-import:PAD.03X.04")
      (libsource (lib "eagle-import") (part "TEST-POINT3X4"))
    )
    (comp (ref "TP70")
      (value "TEST-POINT3X4")
      (footprint "eagle-import:PAD.03X.04")
      (libsource (lib "eagle-import") (part "TEST-POINT3X4"))
    )
    (comp (ref "TP100")
      (value "TEST-POINT3X4")
      (footprint "eagle-import:PAD.03X.04")
      (libsource (lib "eagle-import") (part "TEST-POINT3X4"))
    )
    (comp (ref "TP101")
      (value "TEST-POINT3X4")
      (footprint "eagle-import:PAD.03X.04")
      (libsource (lib "eagle-import") (part "TEST-POINT3X4"))
    )
    (comp (ref "TP103")
      (value "TEST-POINT3X4")
      (footprint "eagle-import:PAD.03X.04")
      (libsource (lib "eagle-import") (part "TEST-POINT3X4"))
    )
    (comp (ref "TP104")
      (value "TEST-POINT3X4")
      (footprint "eagle-import:PAD.03X.04")
      (libsource (lib "eagle-import") (part "TEST-POINT3X4"))
    )
    (comp (ref "TP105")
      (value "TEST-POINT3X4")
      (footprint "eagle-import:PAD.03X.04")
      (libsource (lib "eagle-import") (part "TEST-POINT3X4"))
    )
    (comp (ref "TP106")
      (value "TEST-POINT3X4")
      (footprint "eagle-import:PAD.03X.04")
      (libsource (lib "eagle-import") (part "TEST-POINT3X4"))
    )
    (comp (ref "TP107")
      (value "TEST-POINT3X4")
      (footprint "eagle-import:PAD.03X.04")
      (libsource (lib "eagle-import") (part "TEST-POINT3X4"))
    )
    (comp (ref "TP108")
      (value "TEST-POINT3X4")
      (footprint "eagle-import:PAD.03X.04")
      (libsource (lib "eagle-import") (part "TEST-POINT3X4"))
    )
    (comp (ref "TP111")
      (value "TEST-POINT3X4")
      (footprint "eagle-import:PAD.03X.04")
      (libsource (lib "eagle-import") (part "TEST-POINT3X4"))
    )
    (comp (ref "TP114")
      (value "TEST-POINT3X4")
      (footprint "eagle-import:PAD.03X.04")
      (libsource (lib "eagle-import") (part "TEST-POINT3X4"))
    )
    (comp (ref "TP115")
      (value "TEST-POINT3X4")
      (footprint "eagle-import:PAD.03X.04")
      (libsource (lib "eagle-import") (part "TEST-POINT3X4"))
    )
    (comp (ref "TP117")
      (value "TEST-POINT3X4")
      (footprint "eagle-import:PAD.03X.04")
      (libsource (lib "eagle-import") (part "TEST-POINT3X4"))
    )
    (comp (ref "TP118")
      (value "TEST-POINT3X4")
      (footprint "eagle-import:PAD.03X.04")
      (libsource (lib "eagle-import") (part "TEST-POINT3X4"))
    )
    (comp (ref "TP120")
      (value "TEST-POINT3X4")
      (footprint "eagle-import:PAD.03X.04")
      (libsource (lib "eagle-import") (part "TEST-POINT3X4"))
    )
    (comp (ref "TP122")
      (value "TEST-POINT3X4")
      (footprint "eagle-import:PAD.03X.04")
      (libsource (lib "eagle-import") (part "TEST-POINT3X4"))
    )
    (comp (ref "TP123")
      (value "TEST-POINT3X4")
      (footprint "eagle-import:PAD.03X.04")
      (libsource (lib "eagle-import") (part "TEST-POINT3X4"))
    )
    (comp (ref "TP124")
      (value "TEST-POINT3X4")
      (footprint "eagle-import:PAD.03X.04")
      (libsource (lib "eagle-import") (part "TEST-POINT3X4"))
    )
    (comp (ref "TP125")
      (value "TEST-POINT3X4")
      (footprint "eagle-import:PAD.03X.04")
      (libsource (lib "eagle-import") (part "TEST-POINT3X4"))
    )
    (comp (ref "TP126")
      (value "TEST-POINT3X4")
      (footprint "eagle-import:PAD.03X.04")
      (libsource (lib "eagle-import") (part "TEST-POINT3X4"))
    )
    (comp (ref "TP127")
      (value "TEST-POINT3X4")
      (footprint "eagle-import:PAD.03X.04")
      (libsource (lib "eagle-import") (part "TEST-POINT3X4"))
    )
    (comp (ref "TP128")
      (value "TEST-POINT3X4")
      (footprint "eagle-import:PAD.03X.04")
      (libsource (lib "eagle-import") (part "TEST-POINT3X4"))
    )
    (comp (ref "TP131")
      (value "TEST-POINT3X4")
      (footprint "eagle-import:PAD.03X.04")
      (libsource (lib "eagle-import") (part "TEST-POINT3X4"))
    )
    (comp (ref "TP134")
      (value "TEST-POINT3X4")
      (footprint "eagle-import:PAD.03X.04")
      (libsource (lib "eagle-import") (part "TEST-POINT3X4"))
    )
    (comp (ref "TP135")
      (value "TEST-POINT3X4")
      (footprint "eagle-import:PAD.03X.04")
      (libsource (lib "eagle-import") (part "TEST-POINT3X4"))
    )
    (comp (ref "TP137")
      (value "TEST-POINT3X4")
      (footprint "eagle-import:PAD.03X.04")
      (libsource (lib "eagle-import") (part "TEST-POINT3X4"))
    )
    (comp (ref "TP142")
      (value "TEST-POINT3X4")
      (footprint "eagle-import:PAD.03X.04")
      (libsource (lib "eagle-import") (part "TEST-POINT3X4"))
    )
    (comp (ref "TP146")
      (value "TEST-POINT3X4")
      (footprint "eagle-import:PAD.03X.04")
      (libsource (lib "eagle-import") (part "TEST-POINT3X4"))
    )
    (comp (ref "TP147")
      (value "TEST-POINT3X4")
      (footprint "eagle-import:PAD.03X.04")
      (libsource (lib "eagle-import") (part "TEST-POINT3X4"))
    )
    (comp (ref "TP148")
      (value "TEST-POINT3X4")
      (footprint "eagle-import:PAD.03X.04")
      (libsource (lib "eagle-import") (part "TEST-POINT3X4"))
    )
    (comp (ref "TP149")
      (value "TEST-POINT3X4")
      (footprint "eagle-import:PAD.03X.04")
      (libsource (lib "eagle-import") (part "TEST-POINT3X4"))
    )
    (comp (ref "TP152")
      (value "TEST-POINT3X4")
      (footprint "eagle-import:PAD.03X.04")
      (libsource (lib "eagle-import") (part "TEST-POINT3X4"))
    )
    (comp (ref "TP153")
      (value "TEST-POINT3X4")
      (footprint "eagle-import:PAD.03X.04")
      (libsource (lib "eagle-import") (part "TEST-POINT3X4"))
    )
    (comp (ref "TP158")
      (value "TEST-POINT3X4")
      (footprint "eagle-import:PAD.03X.04")
      (libsource (lib "eagle-import") (part "TEST-POINT3X4"))
    )
    (comp (ref "TP159")
      (value "TEST-POINT3X4")
      (footprint "eagle-import:PAD.03X.04")
      (libsource (lib "eagle-import") (part "TEST-POINT3X4"))
    )
    (comp (ref "TP162")
      (value "TEST-POINT3X4")
      (footprint "eagle-import:PAD.03X.04")
      (libsource (lib "eagle-import") (part "TEST-POINT3X4"))
    )
    (comp (ref "TP174")
      (value "TEST-POINT3X4")
      (footprint "eagle-import:PAD.03X.04")
      (libsource (lib "eagle-import") (part "TEST-POINT3X4"))
    )
    (comp (ref "TP177")
      (value "TEST-POINT3X4")
      (footprint "eagle-import:PAD.03X.04")
      (libsource (lib "eagle-import") (part "TEST-POINT3X4"))
    )
    (comp (ref "TP178")
      (value "TEST-POINT3X4")
      (footprint "eagle-import:PAD.03X.04")
      (libsource (lib "eagle-import") (part "TEST-POINT3X4"))
    )
    (comp (ref "TP180")
      (value "TEST-POINT3X4")
      (footprint "eagle-import:PAD.03X.04")
      (libsource (lib "eagle-import") (part "TEST-POINT3X4"))
    )
    (comp (ref "U3")
      (value "THGBMJG7C2LBAU8")
      (footprint "eagle-import:BGA-153(11.5X13)(EMMC-BA)")
      (libsource (lib "eagle-import") (part "EMMC+RESET+5.1-COMPATIBLE-BA"))
    )
    (comp (ref "U11")
      (value "TCAN330")
      (footprint "eagle-import:SOT23-8_TI-DCN")
      (fields (field (name "MPN") "TCAN330GDCNT"))
      (libsource (lib "eagle-import") (part "TCAN330"))
    )
    (comp (ref "U17")
      (value "25AAXX")
      (footprint "eagle-import:SOIC8")
      (fields (field (name "MPN") "25AA02E48T-I/SN"))
      (libsource (lib "eagle-import") (part "25AAXX"))
    )
    (comp (ref "C1")
      (value "10uF")
      (footprint "eagle-import:.0805-B")
      (libsource (lib "eagle-import") (part "C-EU0805-B"))
    )
    (comp (ref "C4")
      (value "0.1uF")
      (footprint "eagle-import:.0603-A")
      (libsource (lib "eagle-import") (part "C-EU0603-A"))
    )
    (comp (ref "C7")
      (value "10uF")
      (footprint "eagle-import:.0805-B")
      (libsource (lib "eagle-import") (part "C-EU0805-B"))
    )
    (comp (ref "C19")
      (value "12pF, 50V")
      (footprint "eagle-import:.0603-A")
      (libsource (lib "eagle-import") (part "C-EU0603-A"))
    )
    (comp (ref "C22")
      (value "12pF, 50V")
      (footprint "eagle-import:.0603-A")
      (libsource (lib "eagle-import") (part "C-EU0603-A"))
    )
    (comp (ref "C29")
      (value "12pF, 50V")
      (footprint "eagle-import:.0603-A")
      (libsource (lib "eagle-import") (part "C-EU0603-A"))
    )
    (comp (ref "C30")
      (value "12pF, 50V")
      (footprint "eagle-import:.0603-A")
      (libsource (lib "eagle-import") (part "C-EU0603-A"))
    )
    (comp (ref "FB1")
      (value "30Ω/1.8A")
      (footprint "eagle-import:0603")
      (fields (field (name "MPN") "BLM18KG300JH1D"))
      (libsource (lib "eagle-import") (part "FERRITE_BEAD-0603"))
    )
    (comp (ref "FB2")
      (value "30Ω/1.8A")
      (footprint "eagle-import:0603")
      (fields (field (name "MPN") "BLM18KG300JH1D"))
      (libsource (lib "eagle-import") (part "FERRITE_BEAD-0603"))
    )
    (comp (ref "J102")
      (value "FTSH-105-XX-X-DV-K")
      (footprint "eagle-import:CON10_2X5_DUK_FTSH")
      (libsource (lib "eagle-import") (part "FTSH-105-XX-X-DV-K"))
    )
    (comp (ref "JP1")
      (value "JUMPER-SMT_2_NO_SILK")
      (footprint "eagle-import:SMT-JUMPER_2_NO_SILK")
      (libsource (lib "eagle-import") (part "JUMPER-SMT_2_NO_SILK"))
    )
    (comp (ref "JP100")
      (value "JUMPER-SMT_2_NC_TRACE_SILK")
      (footprint "eagle-import:SMT-JUMPER_2_NC_TRACE_SILK")
      (libsource (lib "eagle-import") (part "JUMPER-SMT_2_NC_TRACE_SILK"))
    )
    (comp (ref "R6")
      (value "10k")
      (footprint "eagle-import:.0603-A")
      (libsource (lib "eagle-import") (part "R-US_0603-A"))
    )
    (comp (ref "R7")
      (value "10k")
      (footprint "eagle-import:.0603-A")
      (libsource (lib "eagle-import") (part "R-US_0603-A"))
    )
    (comp (ref "R13")
      (value "1M")
      (footprint "eagle-import:.0603-A")
      (libsource (lib "eagle-import") (part "R-US_0603-A"))
    )
    (comp (ref "R19")
      (value "10k")
      (footprint "eagle-import:.0603-A")
      (libsource (lib "eagle-import") (part "R-US_0603-A"))
    )
    (comp (ref "R20")
      (value "10k")
      (footprint "eagle-import:.0603-A")
      (libsource (lib "eagle-import") (part "R-US_0603-A"))
    )
    (comp (ref "R22")
      (value "10k")
      (footprint "eagle-import:.0603-A")
      (libsource (lib "eagle-import") (part "R-US_0603-A"))
    )
    (comp (ref "R27")
      (value "DNP")
      (footprint "eagle-import:.0603-A")
      (libsource (lib "eagle-import") (part "R-US_0603-A"))
    )
    (comp (ref "TP1")
      (value "TEST-POINT3X4")
      (footprint "eagle-import:PAD.03X.04")
      (libsource (lib "eagle-import") (part "TEST-POINT3X4"))
    )
    (comp (ref "TP31")
      (value "TEST-POINT3X4")
      (footprint "eagle-import:PAD.03X.04")
      (libsource (lib "eagle-import") (part "TEST-POINT3X4"))
    )
    (comp (ref "TP38")
      (value "TEST-POINT3X4")
      (footprint "eagle-import:PAD.03X.04")
      (libsource (lib "eagle-import") (part "TEST-POINT3X4"))
    )
    (comp (ref "TP39")
      (value "TEST-POINT3X4")
      (footprint "eagle-import:PAD.03X.04")
      (libsource (lib "eagle-import") (part "TEST-POINT3X4"))
    )
    (comp (ref "TP133")
      (value "TEST-POINT3X4")
      (footprint "eagle-import:PAD.03X.04")
      (libsource (lib "eagle-import") (part "TEST-POINT3X4"))
    )
    (comp (ref "TP138")
      (value "TEST-POINT3X4")
      (footprint "eagle-import:PAD.03X.04")
      (libsource (lib "eagle-import") (part "TEST-POINT3X4"))
    )
    (comp (ref "TP139")
      (value "TEST-POINT3X4")
      (footprint "eagle-import:PAD.03X.04")
      (libsource (lib "eagle-import") (part "TEST-POINT3X4"))
    )
    (comp (ref "TP141")
      (value "TEST-POINT3X4")
      (footprint "eagle-import:PAD.03X.04")
      (libsource (lib "eagle-import") (part "TEST-POINT3X4"))
    )
    (comp (ref "TP144")
      (value "TEST-POINT3X4")
      (footprint "eagle-import:PAD.03X.04")
      (libsource (lib "eagle-import") (part "TEST-POINT3X4"))
    )
    (comp (ref "TP168")
      (value "TEST-POINT3X4")
      (footprint "eagle-import:PAD.03X.04")
      (libsource (lib "eagle-import") (part "TEST-POINT3X4"))
    )
    (comp (ref "TP169")
      (value "TEST-POINT3X4")
      (footprint "eagle-import:PAD.03X.04")
      (libsource (lib "eagle-import") (part "TEST-POINT3X4"))
    )
    (comp (ref "TP170")
      (value "TEST-POINT3X4")
      (footprint "eagle-import:PAD.03X.04")
      (libsource (lib "eagle-import") (part "TEST-POINT3X4"))
    )
    (comp (ref "TP171")
      (value "TEST-POINT3X4")
      (footprint "eagle-import:PAD.03X.04")
      (libsource (lib "eagle-import") (part "TEST-POINT3X4"))
    )
    (comp (ref "TP175")
      (value "TEST-POINT3X4")
      (footprint "eagle-import:PAD.03X.04")
      (libsource (lib "eagle-import") (part "TEST-POINT3X4"))
    )
    (comp (ref "TP176")
      (value "TEST-POINT3X4")
      (footprint "eagle-import:PAD.03X.04")
      (libsource (lib "eagle-import") (part "TEST-POINT3X4"))
    )
    (comp (ref "TP179")
      (value "TEST-POINT3X4")
      (footprint "eagle-import:PAD.03X.04")
      (libsource (lib "eagle-import") (part "TEST-POINT3X4"))
    )
    (comp (ref "TP181")
      (value "TEST-POINT3X4")
      (footprint "eagle-import:PAD.03X.04")
      (libsource (lib "eagle-import") (part "TEST-POINT3X4"))
    )
    (comp (ref "TP182")
      (value "TEST-POINT3X4")
      (footprint "eagle-import:PAD.03X.04")
      (libsource (lib "eagle-import") (part "TEST-POINT3X4"))
    )
    (comp (ref "U1")
      (value "RCLAMP0504FB")
      (footprint "eagle-import:SC70-6")
      (fields (field (name "MPN") "RCLAMP0504FBTCT"))
      (libsource (lib "eagle-import") (part "RCLAMP0504FB"))
    )
    (comp (ref "U2")
      (value "TPS2051CDBVR")
      (footprint "eagle-import:DBV5")
      (fields (field (name "MFR") "Texas Instruments"))
      (libsource (lib "eagle-import") (part "TPS2051CDBVR"))
    )
    (comp (ref "Y1")
      (value "24MHz")
      (footprint "eagle-import:5X3.2-4SMD")
      (fields (field (name "MPN") "ECS-240-12-30BQ-AEN-TR"))
      (libsource (lib "eagle-import") (part "ECS-240-12-30BQ-AEN-TR"))
    )
    (comp (ref "Y2")
      (value "ABS07-32.768KHZ-T")
      (footprint "eagle-import:CRYSTAL_3.2X1.5")
      (libsource (lib "eagle-import") (part "ABS07-32.768KHZ-T"))
    )
    (comp (ref "CM1")
      (value "J-MOLEX-SMPM-73300-003X")
      (footprint "eagle-import:J-MOLEX-SMPM-073300-003X")
      (fields (field (name "MFG") "MOLEX"))
      (libsource (lib "eagle-import") (part "J-MOLEX-SMPM-73300-003X"))
    )
    (comp (ref "J1")
      (value "ORESAT-DEBUG-CONNECTOR-CARD")
      (footprint "eagle-import:TE_2-1734592-0")
      (fields (field (name "MPN") "2-1734592-0"))
      (libsource (lib "eagle-import") (part "ORESAT-DEBUG-CONNECTOR-CARD"))
    )
    (comp (ref "J4")
      (value "TFM-120-01-L-D-RA")
      (footprint "eagle-import:J-SAMTEC-TFM-120-X1-XXX-D-RA")
      (libsource (lib "eagle-import") (part "J-SAMTEC-TFM-120-X1-XXX-D-RA"))
    )
    (comp (ref "PCB1")
      (value "ORESAT-CARD-V1.3-GENERIC-1RF-POS2")
      (footprint "eagle-import:ORESAT-CARD-V1.3-GENERIC-1RF-POS2")
      (libsource (lib "eagle-import") (part "ORESAT-CARD-V1.3-GENERIC-1RF-POS2"))
    )
    (comp (ref "TP58")
      (value "TEST-POINT3X4")
      (footprint "eagle-import:PAD.03X.04")
      (libsource (lib "eagle-import") (part "TEST-POINT3X4"))
    )
    (comp (ref "TP59")
      (value "TEST-POINT3X4")
      (footprint "eagle-import:PAD.03X.04")
      (libsource (lib "eagle-import") (part "TEST-POINT3X4"))
    )
    (comp (ref "TP60")
      (value "TEST-POINT3X4")
      (footprint "eagle-import:PAD.03X.04")
      (libsource (lib "eagle-import") (part "TEST-POINT3X4"))
    )
    (comp (ref "TP61")
      (value "TEST-POINT3X4")
      (footprint "eagle-import:PAD.03X.04")
      (libsource (lib "eagle-import") (part "TEST-POINT3X4"))
    )
    (comp (ref "TP62")
      (value "TEST-POINT3X4")
      (footprint "eagle-import:PAD.03X.04")
      (libsource (lib "eagle-import") (part "TEST-POINT3X4"))
    )
    (comp (ref "TP183")
      (value "TEST-POINT3X4")
      (footprint "eagle-import:PAD.03X.04")
      (libsource (lib "eagle-import") (part "TEST-POINT3X4"))
    )
    (comp (ref "TP184")
      (value "TEST-POINT3X4")
      (footprint "eagle-import:PAD.03X.04")
      (libsource (lib "eagle-import") (part "TEST-POINT3X4"))
    )
    (comp (ref "C47")
      (value "1u")
      (footprint "eagle-import:.0603-B-NOSILK")
      (libsource (lib "eagle-import") (part "rcl_custom_C-EU0603-B-NOSILK"))
    )
    (comp (ref "C48")
      (value "1u")
      (footprint "eagle-import:.0603-B-NOSILK")
      (libsource (lib "eagle-import") (part "rcl_custom_C-EU0603-B-NOSILK"))
    )
    (comp (ref "C49")
      (value "1u")
      (footprint "eagle-import:.0603-B-NOSILK")
      (libsource (lib "eagle-import") (part "rcl_custom_C-EU0603-B-NOSILK"))
    )
    (comp (ref "C50")
      (value "10n")
      (footprint "eagle-import:.0603-B-NOSILK")
      (libsource (lib "eagle-import") (part "C-EU0603-B-NOSILK"))
    )
    (comp (ref "C55")
      (value "100n")
      (footprint "eagle-import:.0603-B-NOSILK")
      (libsource (lib "eagle-import") (part "C-EU0603-B-NOSILK"))
    )
    (comp (ref "C56")
      (value "100n")
      (footprint "eagle-import:.0603-B-NOSILK")
      (libsource (lib "eagle-import") (part "C-EU0603-B-NOSILK"))
    )
    (comp (ref "C59")
      (value "1u")
      (footprint "eagle-import:.0603-B-NOSILK")
      (libsource (lib "eagle-import") (part "rcl_custom_C-EU0603-B-NOSILK"))
    )
    (comp (ref "C60")
      (value "10n")
      (footprint "eagle-import:.0603-B-NOSILK")
      (libsource (lib "eagle-import") (part "C-EU0603-B-NOSILK"))
    )
    (comp (ref "C65")
      (value "100n")
      (footprint "eagle-import:.0603-B-NOSILK")
      (libsource (lib "eagle-import") (part "C-EU0603-B-NOSILK"))
    )
    (comp (ref "C67")
      (value "1u")
      (footprint "eagle-import:.0603-B-NOSILK")
      (libsource (lib "eagle-import") (part "rcl_custom_C-EU0603-B-NOSILK"))
    )
    (comp (ref "C68")
      (value "1u")
      (footprint "eagle-import:.0603-B-NOSILK")
      (libsource (lib "eagle-import") (part "rcl_custom_C-EU0603-B-NOSILK"))
    )
    (comp (ref "C69")
      (value "10n")
      (footprint "eagle-import:.0603-B-NOSILK")
      (libsource (lib "eagle-import") (part "C-EU0603-B-NOSILK"))
    )
    (comp (ref "C70")
      (value "100n")
      (footprint "eagle-import:.0603-B-NOSILK")
      (libsource (lib "eagle-import") (part "C-EU0603-B-NOSILK"))
    )
    (comp (ref "C81")
      (value "56p")
      (footprint "eagle-import:.0402-C-NOSILK")
      (libsource (lib "eagle-import") (part "rcl_custom_C-EU0402-C-NOSILK"))
    )
    (comp (ref "R30")
      (value "10k")
      (footprint "eagle-import:.0603-B-NOSILK")
      (libsource (lib "eagle-import") (part "R-US_0603-B-NOSILK"))
    )
    (comp (ref "R77")
      (value "10k")
      (footprint "eagle-import:0402-C-NOSILK@1")
      (libsource (lib "eagle-import") (part "rcl_custom_R-US_0402-C-NOSILK"))
    )
    (comp (ref "R79")
      (value "10k")
      (footprint "eagle-import:.0603-B-NOSILK")
      (libsource (lib "eagle-import") (part "R-US_0603-B-NOSILK"))
    )
    (comp (ref "SH1")
      (value "BMI-S-202-SHIELD")
      (footprint "eagle-import:BMI-S-202")
      (fields (field (name "MFR") "Laird Technologies EMI") (field (name "MPN") "BMI-S-202-C"))
      (libsource (lib "eagle-import") (part "BMI-S-202-SHIELD"))
    )
    (comp (ref "TP5")
      (value "TEST-POINT15MIL-TEST-POINT")
      (footprint "eagle-import:15MIL-TEST-POINT")
      (libsource (lib "eagle-import") (part "TEST-POINT15MIL-TEST-POINT"))
    )
    (comp (ref "TP11")
      (value "TEST-POINT15MIL-TEST-POINT")
      (footprint "eagle-import:15MIL-TEST-POINT")
      (libsource (lib "eagle-import") (part "TEST-POINT15MIL-TEST-POINT"))
    )
    (comp (ref "TP15")
      (value "TEST-POINT15MIL-TEST-POINT")
      (footprint "eagle-import:15MIL-TEST-POINT")
      (libsource (lib "eagle-import") (part "TEST-POINT15MIL-TEST-POINT"))
    )
    (comp (ref "U5")
      (value "SKY65723-81")
      (footprint "eagle-import:SKY65723-81")
      (fields (field (name "MFR") "Skyworks Solutions"))
      (libsource (lib "eagle-import") (part "SKY65723-81"))
    )
    (comp (ref "U8")
      (value "MAX8510EXK29+T")
      (footprint "eagle-import:SC70")
      (fields (field (name "MFR") "Maxim Integrated"))
      (libsource (lib "eagle-import") (part "V_REG_LDOSMD2"))
    )
    (comp (ref "U9")
      (value "MAX8510EXK29+T")
      (footprint "eagle-import:SC70")
      (fields (field (name "MFR") "Maxim Integrated"))
      (libsource (lib "eagle-import") (part "V_REG_LDOSMD2"))
    )
    (comp (ref "U19")
      (value "BP2G+")
      (footprint "eagle-import:MINICIRCUITS")
      (libsource (lib "eagle-import") (part "MINICIRCUITS-BP2G"))
    )
    (comp (ref "U20")
      (value "MAX8510EXK29+T")
      (footprint "eagle-import:SC70")
      (fields (field (name "MFR") "Maxim Integrated"))
      (libsource (lib "eagle-import") (part "V_REG_LDOSMD2"))
    )
    (comp (ref "C52")
      (value "1u")
      (footprint "eagle-import:.0603-B-NOSILK")
      (libsource (lib "eagle-import") (part "C-EU0603-B-NOSILK"))
    )
    (comp (ref "C54")
      (value "100p")
      (footprint "eagle-import:.0603-B-NOSILK")
      (libsource (lib "eagle-import") (part "C-EU0603-B-NOSILK"))
    )
    (comp (ref "C61")
      (value "100n")
      (footprint "eagle-import:.0603-B-NOSILK")
      (libsource (lib "eagle-import") (part "C-EU0603-B-NOSILK"))
    )
    (comp (ref "C79")
      (value "1u")
      (footprint "eagle-import:.0603-B-NOSILK")
      (libsource (lib "eagle-import") (part "C-EU0603-B-NOSILK"))
    )
    (comp (ref "C80")
      (value "100p")
      (footprint "eagle-import:.0603-B-NOSILK")
      (libsource (lib "eagle-import") (part "C-EU0603-B-NOSILK"))
    )
    (comp (ref "C82")
      (value "100n")
      (footprint "eagle-import:.0603-B-NOSILK")
      (libsource (lib "eagle-import") (part "C-EU0603-B-NOSILK"))
    )
    (comp (ref "C85")
      (value "DSK-3R3H334T-HL")
      (footprint "eagle-import:CAP-ELNA-DS-SERIES")
      (libsource (lib "eagle-import") (part "CAP-ELNA-DS"))
    )
    (comp (ref "D9")
      (value "DIODE-0603")
      (footprint "eagle-import:0603-B-NOSILK-DIODE")
      (libsource (lib "eagle-import") (part "DIODE-0603"))
    )
    (comp (ref "D10")
      (value "Yellow")
      (footprint "eagle-import:LED-0603")
      (libsource (lib "eagle-import") (part "LED-YELLOW0603"))
    )
    (comp (ref "R14")
      (value "10k")
      (footprint "eagle-import:.0603-B-NOSILK")
      (libsource (lib "eagle-import") (part "R-US_0603-B-NOSILK"))
    )
    (comp (ref "R17")
      (value "1k")
      (footprint "eagle-import:.0603-B-NOSILK")
      (libsource (lib "eagle-import") (part "R-US_0603-B-NOSILK"))
    )
    (comp (ref "R18")
      (value "10k")
      (footprint "eagle-import:.0603-B-NOSILK")
      (libsource (lib "eagle-import") (part "R-US_0603-B-NOSILK"))
    )
    (comp (ref "R21")
      (value "33k")
      (footprint "eagle-import:.0603-B-NOSILK")
      (libsource (lib "eagle-import") (part "R-US_0603-B-NOSILK"))
    )
    (comp (ref "R29")
      (value "10k")
      (footprint "eagle-import:.0603-B-NOSILK")
      (libsource (lib "eagle-import") (part "R-US_0603-B-NOSILK"))
    )
    (comp (ref "R76")
      (value "100")
      (footprint "eagle-import:.0603-B-NOSILK")
      (libsource (lib "eagle-import") (part "R-US_0603-B-NOSILK"))
    )
    (comp (ref "R80")
      (value "10k")
      (footprint "eagle-import:.0603-B-NOSILK")
      (libsource (lib "eagle-import") (part "R-US_0603-B-NOSILK"))
    )
    (comp (ref "R81")
      (value "10k")
      (footprint "eagle-import:.0603-B-NOSILK")
      (libsource (lib "eagle-import") (part "R-US_0603-B-NOSILK"))
    )
    (comp (ref "TP6")
      (value "TEST-POINT15MIL-TEST-POINT")
      (footprint "eagle-import:15MIL-TEST-POINT")
      (libsource (lib "eagle-import") (part "TEST-POINT15MIL-TEST-POINT"))
    )
    (comp (ref "TP7")
      (value "TEST-POINT15MIL-TEST-POINT")
      (footprint "eagle-import:15MIL-TEST-POINT")
      (libsource (lib "eagle-import") (part "TEST-POINT15MIL-TEST-POINT"))
    )
    (comp (ref "TP8")
      (value "TEST-POINT15MIL-TEST-POINT")
      (footprint "eagle-import:15MIL-TEST-POINT")
      (libsource (lib "eagle-import") (part "TEST-POINT15MIL-TEST-POINT"))
    )
    (comp (ref "TP27")
      (value "TEST-POINT15MIL-TEST-POINT")
      (footprint "eagle-import:15MIL-TEST-POINT")
      (libsource (lib "eagle-import") (part "TEST-POINT15MIL-TEST-POINT"))
    )
    (comp (ref "TP28")
      (value "TEST-POINT15MIL-TEST-POINT")
      (footprint "eagle-import:15MIL-TEST-POINT")
      (libsource (lib "eagle-import") (part "TEST-POINT15MIL-TEST-POINT"))
    )
    (comp (ref "TP29")
      (value "TEST-POINT15MIL-TEST-POINT")
      (footprint "eagle-import:15MIL-TEST-POINT")
      (libsource (lib "eagle-import") (part "TEST-POINT15MIL-TEST-POINT"))
    )
    (comp (ref "U24")
      (value "VENUS838LPX-L")
      (footprint "eagle-import:VENUS838LPX")
      (libsource (lib "eagle-import") (part "VENUS838LPX-L"))
    )
    (comp (ref "C32")
      (value "1uF")
      (footprint "eagle-import:.0805-B-NOSILK")
      (libsource (lib "eagle-import") (part "C-EU0805-B-NOSILK"))
    )
    (comp (ref "C33")
      (value "NP")
      (footprint "eagle-import:.0603-A")
      (fields (field (name "MFR") "Samsung") (field (name "MPN") "CL05B104KO5NNNC"))
      (libsource (lib "eagle-import") (part "C-EU0603-A"))
    )
    (comp (ref "C34")
      (value "1uF")
      (footprint "eagle-import:.0603-A")
      (libsource (lib "eagle-import") (part "C-EU0603-A"))
    )
    (comp (ref "C35")
      (value "1uF")
      (footprint "eagle-import:.0805-B-NOSILK")
      (libsource (lib "eagle-import") (part "C-EU0805-B-NOSILK"))
    )
    (comp (ref "C36")
      (value "22uF")
      (footprint "eagle-import:C1210")
      (libsource (lib "eagle-import") (part "C-EUC1210"))
    )
    (comp (ref "C37")
      (value "1uF")
      (footprint "eagle-import:.0603-A")
      (libsource (lib "eagle-import") (part "C-EU0603-A"))
    )
    (comp (ref "C38")
      (value "10uF")
      (footprint "eagle-import:.0805-B")
      (libsource (lib "eagle-import") (part "C-EU0805-B"))
    )
    (comp (ref "C39")
      (value "0.1uF")
      (footprint "eagle-import:.0603-A")
      (libsource (lib "eagle-import") (part "C-EU0603-A"))
    )
    (comp (ref "C62")
      (value "10uF")
      (footprint "eagle-import:.0805-B")
      (libsource (lib "eagle-import") (part "C-EU0805-B"))
    )
    (comp (ref "D6")
      (value "AMBER")
      (footprint "eagle-import:LED-0603")
      (libsource (lib "eagle-import") (part "SparkFun-LED_529_LED-GREEN0603"))
    )
    (comp (ref "D7")
      (value "GREEN")
      (footprint "eagle-import:LED-0603")
      (libsource (lib "eagle-import") (part "LED-GREEN0603"))
    )
    (comp (ref "D8")
      (value "GREEN")
      (footprint "eagle-import:LED-0603")
      (libsource (lib "eagle-import") (part "LED-GREEN0603"))
    )
    (comp (ref "L1")
      (value "6.8u")
      (footprint "eagle-import:ECS-MPI4040")
      (fields (field (name "MPN") "ECS-MPI4040R4-6R8-R"))
      (libsource (lib "eagle-import") (part "L-ECS-MPI4040"))
    )
    (comp (ref "Q2")
      (value "PMV45EN")
      (footprint "eagle-import:SOT23")
      (fields (field (name "MPN") "PMV45EN2R"))
      (libsource (lib "eagle-import") (part "PMV45EN"))
    )
    (comp (ref "Q3")
      (value "DMP2240UDM")
      (footprint "eagle-import:SOT23-6")
      (fields (field (name "MPN") "DMP2240UDM-7"))
      (libsource (lib "eagle-import") (part "Q-MOSFET-PCH-dual-SOT23-6_MOSFET-PCH-SOT23-6"))
    )
    (comp (ref "Q4")
      (value "PMV45EN")
      (footprint "eagle-import:SOT23")
      (fields (field (name "MPN") "PMV45EN2R"))
      (libsource (lib "eagle-import") (part "PMV45EN"))
    )
    (comp (ref "Q5")
      (value "MOSFET-PCH-SOT23-6")
      (footprint "eagle-import:SOT23-6")
      (fields (field (name "MPN") "DMP3050LVT-7") (field (name "MPN_1") "DMP3050LVT-7"))
      (libsource (lib "eagle-import") (part "MOSFET-PCH-SOT23-6"))
    )
    (comp (ref "Q6")
      (value "MOSFET-PCH-SOT23-6")
      (footprint "eagle-import:SOT23-6")
      (fields (field (name "MPN") "DMP3050LVT-7") (field (name "MPN_1") "DMP3050LVT-7"))
      (libsource (lib "eagle-import") (part "MOSFET-PCH-SOT23-6"))
    )
    (comp (ref "R32")
      (value "10k")
      (footprint "eagle-import:.0603-A")
      (libsource (lib "eagle-import") (part "R-US_0603-A"))
    )
    (comp (ref "R33")
      (value "NP")
      (footprint "eagle-import:.0603-A")
      (fields (field (name "MFR") "Samsung") (field (name "MPN") "RC1005F6653CS"))
      (libsource (lib "eagle-import") (part "R-US_0603-A"))
    )
    (comp (ref "R34")
      (value "10k")
      (footprint "eagle-import:.0603-A")
      (libsource (lib "eagle-import") (part "R-US_0603-A"))
    )
    (comp (ref "R35")
      (value "665k")
      (footprint "eagle-import:.0603-A")
      (libsource (lib "eagle-import") (part "R-US_0603-A"))
    )
    (comp (ref "R36")
      (value "1M")
      (footprint "eagle-import:.0603-A")
      (libsource (lib "eagle-import") (part "R-US_0603-A"))
    )
    (comp (ref "R37")
      (value "330k")
      (footprint "eagle-import:.0603-A")
      (libsource (lib "eagle-import") (part "R-US_0603-A"))
    )
    (comp (ref "R38")
      (value "NP")
      (footprint "eagle-import:.0603-A")
      (fields (field (name "MFR") "Samsung") (field (name "MPN") "RC1005F6653CS"))
      (libsource (lib "eagle-import") (part "R-US_0603-A"))
    )
    (comp (ref "R39")
      (value "10k")
      (footprint "eagle-import:.0603-A")
      (libsource (lib "eagle-import") (part "R-US_0603-A"))
    )
    (comp (ref "R40")
      (value "NP")
      (footprint "eagle-import:.0603-A")
      (fields (field (name "MFR") "Samsung") (field (name "MPN") "RC1005F6653CS"))
      (libsource (lib "eagle-import") (part "R-US_0603-A"))
    )
    (comp (ref "R41")
      (value "100")
      (footprint "eagle-import:.0603-A")
      (libsource (lib "eagle-import") (part "R-US_0603-A"))
    )
    (comp (ref "R42")
      (value "NP")
      (footprint "eagle-import:.0603-A")
      (fields (field (name "MFR") "Samsung") (field (name "MPN") "RC1005F6653CS"))
      (libsource (lib "eagle-import") (part "R-US_0603-A"))
    )
    (comp (ref "R43")
      (value "665k")
      (footprint "eagle-import:.0603-A")
      (libsource (lib "eagle-import") (part "R-US_0603-A"))
    )
    (comp (ref "R44")
      (value "1M")
      (footprint "eagle-import:.0603-A")
      (libsource (lib "eagle-import") (part "R-US_0603-A"))
    )
    (comp (ref "R45")
      (value "330k")
      (footprint "eagle-import:.0603-A")
      (libsource (lib "eagle-import") (part "R-US_0603-A"))
    )
    (comp (ref "R46")
      (value "10k")
      (footprint "eagle-import:.0603-A")
      (libsource (lib "eagle-import") (part "R-US_0603-A"))
    )
    (comp (ref "R47")
      (value "0")
      (footprint "eagle-import:.0603-A")
      (libsource (lib "eagle-import") (part "R-US_0603-A"))
    )
    (comp (ref "R48")
      (value "100")
      (footprint "eagle-import:.0603-A")
      (libsource (lib "eagle-import") (part "R-US_0603-A"))
    )
    (comp (ref "R49")
      (value "2.7k")
      (footprint "eagle-import:.0603-A")
      (libsource (lib "eagle-import") (part "R-US_0603-A"))
    )
    (comp (ref "R50")
      (value "0")
      (footprint "eagle-import:.0603-A")
      (libsource (lib "eagle-import") (part "R-US_0603-A"))
    )
    (comp (ref "R51")
      (value "NP")
      (footprint "eagle-import:.0603-A")
      (fields (field (name "MFR") "Samsung") (field (name "MPN") "RC1005F6653CS"))
      (libsource (lib "eagle-import") (part "R-US_0603-A"))
    )
    (comp (ref "R52")
      (value "10k")
      (footprint "eagle-import:.0603-A")
      (libsource (lib "eagle-import") (part "R-US_0603-A"))
    )
    (comp (ref "R53")
      (value "NP")
      (footprint "eagle-import:.0603-A")
      (fields (field (name "MFR") "Samsung") (field (name "MPN") "RC1005F6653CS"))
      (libsource (lib "eagle-import") (part "R-US_0603-A"))
    )
    (comp (ref "R54")
      (value "NP")
      (footprint "eagle-import:.0603-A")
      (fields (field (name "MFR") "Samsung") (field (name "MPN") "RC1005F6653CS"))
      (libsource (lib "eagle-import") (part "R-US_0603-A"))
    )
    (comp (ref "R55")
      (value "NP")
      (footprint "eagle-import:.0603-A")
      (fields (field (name "MFR") "Samsung") (field (name "MPN") "RC1005F6653CS"))
      (libsource (lib "eagle-import") (part "R-US_0603-A"))
    )
    (comp (ref "R56")
      (value "NP")
      (footprint "eagle-import:.0603-A")
      (fields (field (name "MFR") "Samsung") (field (name "MPN") "RC1005F6653CS"))
      (libsource (lib "eagle-import") (part "R-US_0603-A"))
    )
    (comp (ref "R57")
      (value "NP")
      (footprint "eagle-import:.0603-A")
      (fields (field (name "MFR") "Samsung") (field (name "MPN") "RC1005F6653CS"))
      (libsource (lib "eagle-import") (part "R-US_0603-A"))
    )
    (comp (ref "R58")
      (value "NP")
      (footprint "eagle-import:.0603-A")
      (fields (field (name "MFR") "Samsung") (field (name "MPN") "RC1005F6653CS"))
      (libsource (lib "eagle-import") (part "R-US_0603-A"))
    )
    (comp (ref "R61")
      (value "2.7k")
      (footprint "eagle-import:.0603-A")
      (libsource (lib "eagle-import") (part "R-US_0603-A"))
    )
    (comp (ref "R62")
      (value "2.7k")
      (footprint "eagle-import:.0603-A")
      (libsource (lib "eagle-import") (part "R-US_0603-A"))
    )
    (comp (ref "R63")
      (value "100m")
      (footprint "eagle-import:R1206")
      (libsource (lib "eagle-import") (part "rcl_334_R-US_R1206"))
    )
    (comp (ref "R64")
      (value "10k")
      (footprint "eagle-import:.0603-A")
      (libsource (lib "eagle-import") (part "R-US_0603-A"))
    )
    (comp (ref "R65")
      (value "NP")
      (footprint "eagle-import:.0603-A")
      (fields (field (name "MFR") "Samsung") (field (name "MPN") "RC1005F6653CS"))
      (libsource (lib "eagle-import") (part "R-US_0603-A"))
    )
    (comp (ref "R66")
      (value "NP")
      (footprint "eagle-import:.0603-A")
      (fields (field (name "MFR") "Samsung") (field (name "MPN") "RC1005F6653CS"))
      (libsource (lib "eagle-import") (part "R-US_0603-A"))
    )
    (comp (ref "R67")
      (value "NP")
      (footprint "eagle-import:.0603-A")
      (fields (field (name "MFR") "Samsung") (field (name "MPN") "RC1005F6653CS"))
      (libsource (lib "eagle-import") (part "R-US_0603-A"))
    )
    (comp (ref "R68")
      (value "NP")
      (footprint "eagle-import:.0603-A")
      (fields (field (name "MFR") "Samsung") (field (name "MPN") "RC1005F6653CS"))
      (libsource (lib "eagle-import") (part "R-US_0603-A"))
    )
    (comp (ref "R69")
      (value "NP")
      (footprint "eagle-import:.0603-A")
      (fields (field (name "MFR") "Samsung") (field (name "MPN") "RC1005F6653CS"))
      (libsource (lib "eagle-import") (part "R-US_0603-A"))
    )
    (comp (ref "R70")
      (value "NP")
      (footprint "eagle-import:.0603-A")
      (fields (field (name "MFR") "Samsung") (field (name "MPN") "RC1005F6653CS"))
      (libsource (lib "eagle-import") (part "R-US_0603-A"))
    )
    (comp (ref "R71")
      (value "100")
      (footprint "eagle-import:.0603-A")
      (libsource (lib "eagle-import") (part "R-US_0603-A"))
    )
    (comp (ref "R72")
      (value "10k")
      (footprint "eagle-import:.0603-A")
      (libsource (lib "eagle-import") (part "R-US_0603-A"))
    )
    (comp (ref "TP41")
      (value "TEST-POINT")
      (footprint "eagle-import:2MM-TEST-POINT")
      (libsource (lib "eagle-import") (part "TEST-POINT"))
    )
    (comp (ref "TP42")
      (value "TEST-POINT")
      (footprint "eagle-import:2MM-TEST-POINT")
      (libsource (lib "eagle-import") (part "TEST-POINT"))
    )
    (comp (ref "TP43")
      (value "TEST-POINT")
      (footprint "eagle-import:2MM-TEST-POINT")
      (libsource (lib "eagle-import") (part "TEST-POINT"))
    )
    (comp (ref "TP44")
      (value "TEST-POINT")
      (footprint "eagle-import:2MM-TEST-POINT")
      (libsource (lib "eagle-import") (part "TEST-POINT"))
    )
    (comp (ref "TP45")
      (value "TEST-POINT")
      (footprint "eagle-import:2MM-TEST-POINT")
      (libsource (lib "eagle-import") (part "TEST-POINT"))
    )
    (comp (ref "TP46")
      (value "TEST-POINT")
      (footprint "eagle-import:2MM-TEST-POINT")
      (libsource (lib "eagle-import") (part "TEST-POINT"))
    )
    (comp (ref "TP47")
      (value "TEST-POINT")
      (footprint "eagle-import:2MM-TEST-POINT")
      (libsource (lib "eagle-import") (part "TEST-POINT"))
    )
    (comp (ref "TP48")
      (value "TEST-POINT")
      (footprint "eagle-import:2MM-TEST-POINT")
      (libsource (lib "eagle-import") (part "TEST-POINT"))
    )
    (comp (ref "TP49")
      (value "TEST-POINT")
      (footprint "eagle-import:2MM-TEST-POINT")
      (libsource (lib "eagle-import") (part "TEST-POINT"))
    )
    (comp (ref "TP50")
      (value "TEST-POINT")
      (footprint "eagle-import:2MM-TEST-POINT")
      (libsource (lib "eagle-import") (part "TEST-POINT"))
    )
    (comp (ref "TP51")
      (value "TEST-POINT")
      (footprint "eagle-import:2MM-TEST-POINT")
      (libsource (lib "eagle-import") (part "TEST-POINT"))
    )
    (comp (ref "TP52")
      (value "TEST-POINT")
      (footprint "eagle-import:2MM-TEST-POINT")
      (libsource (lib "eagle-import") (part "TEST-POINT"))
    )
    (comp (ref "TP53")
      (value "TEST-POINT")
      (footprint "eagle-import:2MM-TEST-POINT")
      (libsource (lib "eagle-import") (part "TEST-POINT"))
    )
    (comp (ref "TP54")
      (value "TEST-POINT")
      (footprint "eagle-import:2MM-TEST-POINT")
      (libsource (lib "eagle-import") (part "TEST-POINT"))
    )
    (comp (ref "TP55")
      (value "TEST-POINT")
      (footprint "eagle-import:2MM-TEST-POINT")
      (libsource (lib "eagle-import") (part "TEST-POINT"))
    )
    (comp (ref "TP56")
      (value "TEST-POINT")
      (footprint "eagle-import:2MM-TEST-POINT")
      (libsource (lib "eagle-import") (part "TEST-POINT"))
    )
    (comp (ref "TP57")
      (value "TEST-POINT")
      (footprint "eagle-import:2MM-TEST-POINT")
      (libsource (lib "eagle-import") (part "TEST-POINT"))
    )
    (comp (ref "TP63")
      (value "TEST-POINT")
      (footprint "eagle-import:2MM-TEST-POINT")
      (libsource (lib "eagle-import") (part "TEST-POINT"))
    )
    (comp (ref "TP64")
      (value "TEST-POINT")
      (footprint "eagle-import:2MM-TEST-POINT")
      (libsource (lib "eagle-import") (part "TEST-POINT"))
    )
    (comp (ref "TP65")
      (value "TEST-POINT")
      (footprint "eagle-import:2MM-TEST-POINT")
      (libsource (lib "eagle-import") (part "TEST-POINT"))
    )
    (comp (ref "TP66")
      (value "TEST-POINT")
      (footprint "eagle-import:2MM-TEST-POINT")
      (libsource (lib "eagle-import") (part "TEST-POINT"))
    )
    (comp (ref "TP67")
      (value "TEST-POINT")
      (footprint "eagle-import:2MM-TEST-POINT")
      (libsource (lib "eagle-import") (part "TEST-POINT"))
    )
    (comp (ref "TP68")
      (value "TEST-POINT")
      (footprint "eagle-import:2MM-TEST-POINT")
      (libsource (lib "eagle-import") (part "TEST-POINT"))
    )
    (comp (ref "U12")
      (value "MIC842LYC5")
      (footprint "eagle-import:SC70-5")
      (libsource (lib "eagle-import") (part "MIC842LYC5"))
    )
    (comp (ref "U13")
      (value "MIC842LYC5")
      (footprint "eagle-import:SC70-5")
      (libsource (lib "eagle-import") (part "MIC842LYC5"))
    )
    (comp (ref "U14")
      (value "MAX4211FETE")
      (footprint "eagle-import:QFN65P400X400X80-17T210")
      (fields (field (name "MPN") "MAX4211FETE+"))
      (libsource (lib "eagle-import") (part "MAX4211"))
    )
    (comp (ref "U15")
      (value "TPS62112")
      (footprint "eagle-import:S-PVQFN-16")
      (fields (field (name "MPN") "TPS62112RSAR"))
      (libsource (lib "eagle-import") (part "TPS6211X"))
    )
    (comp (ref "U16")
      (value "MAX7310ATE")
      (footprint "eagle-import:QFN65P400X400X80-17T210")
      (fields
        (field (name "MPN") "MAX7310ATE+")
        (field (name "MFR") "Maxim")
        (field (name "MPN_1") "MAX7310ATE")
      )
      (libsource (lib "eagle-import") (part "MAX7310"))
    )
  )
  (nets
    (net (code "1") (name "2.85V-S") (class "Default")
      (node (ref "C52") (pin "1") (pinfunction "1_1") (pintype "passive"))
      (node (ref "C54") (pin "1") (pinfunction "1_1") (pintype "passive"))
      (node (ref "C68") (pin "1") (pinfunction "1_1") (pintype "passive"))
      (node (ref "C69") (pin "1") (pinfunction "1_1") (pintype "passive"))
      (node (ref "C70") (pin "1") (pinfunction "1_1") (pintype "passive"))
      (node (ref "C79") (pin "1") (pinfunction "1_1") (pintype "passive"))
      (node (ref "C80") (pin "1") (pinfunction "1_1") (pintype "passive"))
      (node (ref "D10") (pin "A") (pinfunction "A_A") (pintype "passive"))
      (node (ref "D9") (pin "ANODE") (pinfunction "ANODE_ANODE") (pintype "passive"))
      (node (ref "R21") (pin "2") (pinfunction "2_2") (pintype "passive"))
      (node (ref "R29") (pin "1") (pinfunction "1_1") (pintype "passive"))
      (node (ref "R80") (pin "1") (pinfunction "1_1") (pintype "passive"))
      (node (ref "R81") (pin "1") (pinfunction "1_1") (pintype "passive"))
      (node (ref "TP11") (pin "P$1") (pinfunction "1_P$1") (pintype "passive"))
      (node (ref "U20") (pin "5") (pinfunction "OUT_5") (pintype "passive"))
      (node (ref "U24") (pin "2") (pinfunction "VCC_2") (pintype "power_in"))
      (node (ref "U24") (pin "58") (pinfunction "VCC_58") (pintype "power_in"))
    )
    (net (code "2") (name "2.85VA") (class "Default")
      (node (ref "C20") (pin "1") (pinfunction "1_1") (pintype "passive"))
      (node (ref "C21") (pin "1") (pinfunction "1_1") (pintype "passive"))
      (node (ref "C25") (pin "1") (pinfunction "1_1") (pintype "passive"))
      (node (ref "C26") (pin "1") (pinfunction "1_1") (pintype "passive"))
      (node (ref "C27") (pin "1") (pinfunction "1_1") (pintype "passive"))
      (node (ref "C28") (pin "1") (pinfunction "1_1") (pintype "passive"))
      (node (ref "C44") (pin "1") (pinfunction "1_1") (pintype "passive"))
      (node (ref "C45") (pin "1") (pinfunction "1_1") (pintype "passive"))
      (node (ref "C49") (pin "1") (pinfunction "1_1") (pintype "passive"))
      (node (ref "C50") (pin "1") (pinfunction "1_1") (pintype "passive"))
      (node (ref "C55") (pin "1") (pinfunction "1_1") (pintype "passive"))
      (node (ref "C56") (pin "1") (pinfunction "1_1") (pintype "passive"))
      (node (ref "C58") (pin "1") (pinfunction "1_1") (pintype "passive"))
      (node (ref "C81") (pin "1") (pinfunction "1_1") (pintype "passive"))
      (node (ref "R77") (pin "1") (pinfunction "1_1") (pintype "passive"))
      (node (ref "TP15") (pin "P$1") (pinfunction "1_P$1") (pintype "passive"))
      (node (ref "U23") (pin "2") (pinfunction "VCCCP_2") (pintype "power_in"))
      (node (ref "U23") (pin "22") (pinfunction "VCCRF_22") (pintype "power_in"))
      (node (ref "U23") (pin "27") (pinfunction "VCCIF_27") (pintype "power_in"))
      (node (ref "U23") (pin "28") (pinfunction "VCCVCO_28") (pintype "power_in"))
      (node (ref "U5") (pin "1") (pinfunction "VCC_1") (pintype "power_in"))
      (node (ref "U9") (pin "5") (pinfunction "OUT_5") (pintype "passive"))
    )
    (net (code "3") (name "2.85VD") (class "Default")
      (node (ref "C23") (pin "1") (pinfunction "1_1") (pintype "passive"))
      (node (ref "C24") (pin "1") (pinfunction "1_1") (pintype "passive"))
      (node (ref "C42") (pin "1") (pinfunction "1_1") (pintype "passive"))
      (node (ref "C43") (pin "1") (pinfunction "1_1") (pintype "passive"))
      (node (ref "C51") (pin "1") (pinfunction "1_1") (pintype "passive"))
      (node (ref "C53") (pin "1") (pinfunction "1_1") (pintype "passive"))
      (node (ref "C57") (pin "1") (pinfunction "1_1") (pintype "passive"))
      (node (ref "C59") (pin "1") (pinfunction "1_1") (pintype "passive"))
      (node (ref "C60") (pin "1") (pinfunction "1_1") (pintype "passive"))
      (node (ref "C65") (pin "1") (pinfunction "1_1") (pintype "passive"))
      (node (ref "R12") (pin "2") (pinfunction "2_2") (pintype "passive"))
      (node (ref "TP5") (pin "P$1") (pinfunction "1_P$1") (pintype "passive"))
      (node (ref "U23") (pin "14") (pinfunction "VCCADC_14") (pintype "power_in"))
      (node (ref "U23") (pin "6") (pinfunction "VCCD_6") (pintype "power_in"))
      (node (ref "U6") (pin "4") (pinfunction "VDD_4") (pintype "bidirectional"))
      (node (ref "U8") (pin "5") (pinfunction "OUT_5") (pintype "passive"))
    )
    (net (code "4") (name "3.3V") (class "Default")
      (node (ref "C11") (pin "1") (pinfunction "1_1") (pintype "passive"))
      (node (ref "C2") (pin "1") (pinfunction "1_1") (pintype "passive"))
      (node (ref "C3") (pin "1") (pinfunction "1_1") (pintype "passive"))
      (node (ref "C31") (pin "2") (pinfunction "2_2") (pintype "passive"))
      (node (ref "C40") (pin "2") (pinfunction "2_2") (pintype "passive"))
      (node (ref "C47") (pin "1") (pinfunction "1_1") (pintype "passive"))
      (node (ref "C48") (pin "1") (pinfunction "1_1") (pintype "passive"))
      (node (ref "C5") (pin "1") (pinfunction "1_1") (pintype "passive"))
      (node (ref "C6") (pin "1") (pinfunction "1_1") (pintype "passive"))
      (node (ref "C67") (pin "1") (pinfunction "1_1") (pintype "passive"))
      (node (ref "C8") (pin "1") (pinfunction "1_1") (pintype "passive"))
      (node (ref "C83") (pin "1") (pinfunction "1_1") (pintype "passive"))
      (node (ref "C9") (pin "1") (pinfunction "1_1") (pintype "passive"))
      (node (ref "J100") (pin "4") (pinfunction "VDD_4") (pintype "bidirectional"))
      (node (ref "J102") (pin "1") (pinfunction "VTREF_1") (pintype "passive"))
      (node (ref "J3") (pin "1") (pinfunction "1_1") (pintype "passive"))
      (node (ref "R1") (pin "1") (pinfunction "1_1") (pintype "passive"))
      (node (ref "R10") (pin "10") (pinfunction "55_10") (pintype "passive"))
      (node (ref "R10") (pin "5") (pinfunction "55_5") (pintype "passive"))
      (node (ref "R20") (pin "2") (pinfunction "2_2") (pintype "passive"))
      (node (ref "R22") (pin "2") (pinfunction "2_2") (pintype "passive"))
      (node (ref "R24") (pin "10") (pinfunction "55_10") (pintype "passive"))
      (node (ref "R24") (pin "5") (pinfunction "55_5") (pintype "passive"))
      (node (ref "R60") (pin "1") (pinfunction "1_1") (pintype "passive"))
      (node (ref "R8") (pin "10") (pinfunction "55_10") (pintype "passive"))
      (node (ref "R8") (pin "5") (pinfunction "55_5") (pintype "passive"))
      (node (ref "R9") (pin "10") (pinfunction "55_10") (pintype "passive"))
      (node (ref "R9") (pin "5") (pinfunction "55_5") (pintype "passive"))
      (node (ref "TP25") (pin "P$1") (pinfunction "1_P$1") (pintype "bidirectional"))
      (node (ref "U11") (pin "3") (pinfunction "VCC_3") (pintype "power_in"))
      (node (ref "U17") (pin "8") (pinfunction "VCC_8") (pintype "power_in"))
      (node (ref "U20") (pin "1") (pinfunction "IN_1") (pintype "input"))
      (node (ref "U22") (pin "4") (pinfunction "V+_4") (pintype "power_in"))
      (node (ref "U3") (pin "C6") (pinfunction "VDDQ_C6") (pintype "power_in"))
      (node (ref "U3") (pin "E6") (pinfunction "VDDIO_E6") (pintype "power_in"))
      (node (ref "U3") (pin "F5") (pinfunction "VDDIO_F5") (pintype "power_in"))
      (node (ref "U3") (pin "J10") (pinfunction "VDDIO_J10") (pintype "power_in"))
      (node (ref "U3") (pin "K9") (pinfunction "VDDIO_K9") (pintype "power_in"))
      (node (ref "U3") (pin "M4") (pinfunction "VDDQ_M4") (pintype "power_in"))
      (node (ref "U3") (pin "N4") (pinfunction "VDDQ_N4") (pintype "power_in"))
      (node (ref "U3") (pin "P3") (pinfunction "VDDQ_P3") (pintype "power_in"))
      (node (ref "U3") (pin "P5") (pinfunction "VDDQ_P5") (pintype "power_in"))
      (node (ref "U7") (pin "F6") (pinfunction "SYS_VDD1_3P3V_F6") (pintype "power_in"))
      (node (ref "U7") (pin "F7") (pinfunction "SYS_VDD1_3P3V_F7") (pintype "power_in"))
      (node (ref "U7") (pin "G6") (pinfunction "SYS_VDD1_3P3V_G6") (pintype "power_in"))
      (node (ref "U7") (pin "G7") (pinfunction "SYS_VDD1_3P3V_G7") (pintype "power_in"))
      (node (ref "U8") (pin "1") (pinfunction "IN_1") (pintype "input"))
      (node (ref "U9") (pin "1") (pinfunction "IN_1") (pintype "input"))
    )
    (net (code "5") (name "3.3VA") (class "Default")
      (node (ref "C41") (pin "1") (pinfunction "1_1") (pintype "passive"))
      (node (ref "JP101") (pin "1") (pinfunction "1_1") (pintype "passive"))
      (node (ref "TP165") (pin "P$1") (pinfunction "1_P$1") (pintype "bidirectional"))
      (node (ref "U18") (pin "5") (pinfunction "VCC_5") (pintype "power_in"))
      (node (ref "U7") (pin "F8") (pinfunction "SYS_VDD3_3P3V_F8") (pintype "power_in"))
      (node (ref "U7") (pin "F9") (pinfunction "VDDSHV4_F9") (pintype "power_in"))
      (node (ref "U7") (pin "G8") (pinfunction "SYS_VDD3_3P3V_G8") (pintype "power_in"))
      (node (ref "U7") (pin "G9") (pinfunction "VDDSHV5_G9") (pintype "power_in"))
      (node (ref "U7") (pin "H7") (pinfunction "SYS_VDD3_3P3V_H7") (pintype "power_in"))
      (node (ref "U7") (pin "H8") (pinfunction "SYS_VDD3_3P3V_H8") (pintype "power_in"))
      (node (ref "U7") (pin "H9") (pinfunction "VDDSHV6_H9") (pintype "power_in"))
      (node (ref "U7") (pin "J7") (pinfunction "SYS_VDD3_3P3V_J7") (pintype "power_in"))
      (node (ref "U7") (pin "J8") (pinfunction "SYS_VDD3_3P3V_J8") (pintype "power_in"))
      (node (ref "U7") (pin "J9") (pinfunction "VDDSHV1_J9") (pintype "power_in"))
      (node (ref "U7") (pin "K8") (pinfunction "SYS_VDD3_3P3V_K8") (pintype "power_in"))
      (node (ref "U7") (pin "K9") (pinfunction "VDDSHV2_K9") (pintype "power_in"))
      (node (ref "U7") (pin "L8") (pinfunction "SYS_VDD3_3P3V_L8") (pintype "power_in"))
      (node (ref "U7") (pin "L9") (pinfunction "VDDSHV3_L9") (pintype "power_in"))
    )
    (net (code "6") (name "5V") (class "Default")
      (node (ref "C14") (pin "1") (pinfunction "1_1") (pintype "passive"))
      (node (ref "C36") (pin "1") (pinfunction "1_1") (pintype "passive"))
      (node (ref "L1") (pin "2") (pinfunction "2_2") (pintype "passive"))
      (node (ref "R62") (pin "2") (pinfunction "2_2") (pintype "passive"))
      (node (ref "TP49") (pin "1") (pinfunction "1_1") (pintype "passive"))
      (node (ref "U15") (pin "10") (pinfunction "FB_10") (pintype "input"))
      (node (ref "U7") (pin "P10") (pinfunction "VIN_AC_P10") (pintype "power_in"))
      (node (ref "U7") (pin "R10") (pinfunction "VIN_AC_R10") (pintype "power_in"))
      (node (ref "U7") (pin "T10") (pinfunction "VIN_AC_T10") (pintype "power_in"))
    )
    (net (code "7") (name "AD0") (class "Default")
      (node (ref "R57") (pin "1") (pinfunction "1_1") (pintype "passive"))
      (node (ref "R58") (pin "2") (pinfunction "2_2") (pintype "passive"))
      (node (ref "R69") (pin "2") (pinfunction "2_2") (pintype "passive"))
      (node (ref "R70") (pin "1") (pinfunction "1_1") (pintype "passive"))
      (node (ref "U16") (pin "1") (pinfunction "AD0_1") (pintype "input"))
    )
    (net (code "8") (name "AD1") (class "Default")
      (node (ref "R55") (pin "1") (pinfunction "1_1") (pintype "passive"))
      (node (ref "R56") (pin "2") (pinfunction "2_2") (pintype "passive"))
      (node (ref "R67") (pin "2") (pinfunction "2_2") (pintype "passive"))
      (node (ref "R68") (pin "1") (pinfunction "1_1") (pintype "passive"))
      (node (ref "U16") (pin "2") (pinfunction "AD1_2") (pintype "input"))
    )
    (net (code "9") (name "AD2") (class "Default")
      (node (ref "R53") (pin "1") (pinfunction "1_1") (pintype "passive"))
      (node (ref "R54") (pin "2") (pinfunction "2_2") (pintype "passive"))
      (node (ref "R65") (pin "2") (pinfunction "2_2") (pintype "passive"))
      (node (ref "R66") (pin "1") (pinfunction "1_1") (pintype "passive"))
      (node (ref "U16") (pin "3") (pinfunction "AD2_3") (pintype "input"))
    )
    (net (code "10") (name "BOOT0") (class "Default")
      (node (ref "TP51") (pin "1") (pinfunction "1_1") (pintype "passive"))
      (node (ref "U16") (pin "10") (pinfunction "IO5_10") (pintype "bidirectional"))
    )
    (net (code "11") (name "CAN1_H") (class "Default")
      (node (ref "J4") (pin "33") (pinfunction "33_33") (pintype "passive"))
      (node (ref "J4") (pin "34") (pinfunction "34_34") (pintype "passive"))
      (node (ref "TP184") (pin "P$1") (pinfunction "1_P$1") (pintype "bidirectional"))
    )
    (net (code "12") (name "CAN1_L") (class "Default")
      (node (ref "J4") (pin "35") (pinfunction "35_35") (pintype "passive"))
      (node (ref "J4") (pin "36") (pinfunction "36_36") (pintype "passive"))
      (node (ref "TP183") (pin "P$1") (pinfunction "1_P$1") (pintype "bidirectional"))
    )
    (net (code "13") (name "CAN2_H") (class "Default")
      (node (ref "J4") (pin "17") (pinfunction "17_17") (pintype "passive"))
      (node (ref "J4") (pin "18") (pinfunction "18_18") (pintype "passive"))
      (node (ref "U11") (pin "7") (pinfunction "CANH_7") (pintype "bidirectional"))
    )
    (net (code "14") (name "CAN2_L") (class "Default")
      (node (ref "J4") (pin "19") (pinfunction "19_19") (pintype "passive"))
      (node (ref "J4") (pin "20") (pinfunction "20_20") (pintype "passive"))
      (node (ref "U11") (pin "6") (pinfunction "CANL_6") (pintype "bidirectional"))
    )
    (net (code "15") (name "CB-RESET") (class "Default")
      (node (ref "R39") (pin "2") (pinfunction "2_2") (pintype "passive"))
      (node (ref "TP54") (pin "1") (pinfunction "1_1") (pintype "passive"))
      (node (ref "U14") (pin "9") (pinfunction "CIN2-_9") (pintype "input"))
      (node (ref "U16") (pin "9") (pinfunction "IO4_9") (pintype "bidirectional"))
    )
    (net (code "16") (name "CB_CTRL") (class "Default")
      (node (ref "Q2") (pin "1") (pinfunction "G_1") (pintype "passive"))
      (node (ref "Q5") (pin "3") (pinfunction "G_3") (pintype "passive"))
      (node (ref "R64") (pin "1") (pinfunction "1_1") (pintype "passive"))
      (node (ref "TP52") (pin "1") (pinfunction "1_1") (pintype "passive"))
      (node (ref "U14") (pin "3") (pinfunction "LE_3") (pintype "input"))
      (node (ref "U14") (pin "4") (pinfunction "COUT1_4") (pintype "open_collector"))
      (node (ref "U14") (pin "6") (pinfunction "COUT2_6") (pintype "open_collector"))
    )
    (net (code "17") (name "EEPROM_WP") (class "Default")
      (node (ref "J1") (pin "20") (pinfunction "DEBUG-3_20") (pintype "passive"))
      (node (ref "R75") (pin "1") (pinfunction "1_1") (pintype "passive"))
      (node (ref "TP112") (pin "P$1") (pinfunction "1_P$1") (pintype "bidirectional"))
      (node (ref "U18") (pin "6") (pinfunction "I4_6") (pintype "bidirectional"))
    )
    (net (code "18") (name "GND") (class "Default")
      (node (ref "C1") (pin "2") (pinfunction "2_2") (pintype "passive"))
      (node (ref "C10") (pin "2") (pinfunction "2_2") (pintype "passive"))
      (node (ref "C11") (pin "2") (pinfunction "2_2") (pintype "passive"))
      (node (ref "C12") (pin "2") (pinfunction "2_2") (pintype "passive"))
      (node (ref "C13") (pin "2") (pinfunction "2_2") (pintype "passive"))
      (node (ref "C14") (pin "2") (pinfunction "2_2") (pintype "passive"))
      (node (ref "C15") (pin "2") (pinfunction "2_2") (pintype "passive"))
      (node (ref "C16") (pin "2") (pinfunction "2_2") (pintype "passive"))
      (node (ref "C17") (pin "2") (pinfunction "2_2") (pintype "passive"))
      (node (ref "C18") (pin "2") (pinfunction "2_2") (pintype "passive"))
      (node (ref "C2") (pin "2") (pinfunction "2_2") (pintype "passive"))
      (node (ref "C20") (pin "2") (pinfunction "2_2") (pintype "passive"))
      (node (ref "C21") (pin "2") (pinfunction "2_2") (pintype "passive"))
      (node (ref "C23") (pin "2") (pinfunction "2_2") (pintype "passive"))
      (node (ref "C24") (pin "2") (pinfunction "2_2") (pintype "passive"))
      (node (ref "C25") (pin "2") (pinfunction "2_2") (pintype "passive"))
      (node (ref "C26") (pin "2") (pinfunction "2_2") (pintype "passive"))
      (node (ref "C27") (pin "2") (pinfunction "2_2") (pintype "passive"))
      (node (ref "C28") (pin "2") (pinfunction "2_2") (pintype "passive"))
      (node (ref "C3") (pin "2") (pinfunction "2_2") (pintype "passive"))
      (node (ref "C31") (pin "1") (pinfunction "1_1") (pintype "passive"))
      (node (ref "C32") (pin "2") (pinfunction "2_2") (pintype "passive"))
      (node (ref "C34") (pin "2") (pinfunction "2_2") (pintype "passive"))
      (node (ref "C35") (pin "2") (pinfunction "2_2") (pintype "passive"))
      (node (ref "C36") (pin "2") (pinfunction "2_2") (pintype "passive"))
      (node (ref "C37") (pin "2") (pinfunction "2_2") (pintype "passive"))
      (node (ref "C38") (pin "2") (pinfunction "2_2") (pintype "passive"))
      (node (ref "C39") (pin "1") (pinfunction "1_1") (pintype "passive"))
      (node (ref "C4") (pin "2") (pinfunction "2_2") (pintype "passive"))
      (node (ref "C40") (pin "1") (pinfunction "1_1") (pintype "passive"))
      (node (ref "C41") (pin "2") (pinfunction "2_2") (pintype "passive"))
      (node (ref "C42") (pin "2") (pinfunction "2_2") (pintype "passive"))
      (node (ref "C43") (pin "2") (pinfunction "2_2") (pintype "passive"))
      (node (ref "C44") (pin "2") (pinfunction "2_2") (pintype "passive"))
      (node (ref "C45") (pin "2") (pinfunction "2_2") (pintype "passive"))
      (node (ref "C47") (pin "2") (pinfunction "2_2") (pintype "passive"))
      (node (ref "C48") (pin "2") (pinfunction "2_2") (pintype "passive"))
      (node (ref "C49") (pin "2") (pinfunction "2_2") (pintype "passive"))
      (node (ref "C5") (pin "2") (pinfunction "2_2") (pintype "passive"))
      (node (ref "C51") (pin "2") (pinfunction "2_2") (pintype "passive"))
      (node (ref "C52") (pin "2") (pinfunction "2_2") (pintype "passive"))
      (node (ref "C53") (pin "2") (pinfunction "2_2") (pintype "passive"))
      (node (ref "C54") (pin "2") (pinfunction "2_2") (pintype "passive"))
      (node (ref "C55") (pin "2") (pinfunction "2_2") (pintype "passive"))
      (node (ref "C56") (pin "2") (pinfunction "2_2") (pintype "passive"))
      (node (ref "C57") (pin "2") (pinfunction "2_2") (pintype "passive"))
      (node (ref "C58") (pin "2") (pinfunction "2_2") (pintype "passive"))
      (node (ref "C59") (pin "2") (pinfunction "2_2") (pintype "passive"))
      (node (ref "C6") (pin "2") (pinfunction "2_2") (pintype "passive"))
      (node (ref "C61") (pin "1") (pinfunction "1_1") (pintype "passive"))
      (node (ref "C62") (pin "2") (pinfunction "2_2") (pintype "passive"))
      (node (ref "C64") (pin "1") (pinfunction "1_1") (pintype "passive"))
      (node (ref "C65") (pin "2") (pinfunction "2_2") (pintype "passive"))
      (node (ref "C67") (pin "2") (pinfunction "2_2") (pintype "passive"))
      (node (ref "C68") (pin "2") (pinfunction "2_2") (pintype "passive"))
      (node (ref "C7") (pin "2") (pinfunction "2_2") (pintype "passive"))
      (node (ref "C70") (pin "2") (pinfunction "2_2") (pintype "passive"))
      (node (ref "C79") (pin "2") (pinfunction "2_2") (pintype "passive"))
      (node (ref "C8") (pin "2") (pinfunction "2_2") (pintype "passive"))
      (node (ref "C80") (pin "2") (pinfunction "2_2") (pintype "passive"))
      (node (ref "C81") (pin "2") (pinfunction "2_2") (pintype "passive"))
      (node (ref "C82") (pin "1") (pinfunction "1_1") (pintype "passive"))
      (node (ref "C83") (pin "2") (pinfunction "2_2") (pintype "passive"))
      (node (ref "C84") (pin "2") (pinfunction "2_2") (pintype "passive"))
      (node (ref "C85") (pin "-") (pinfunction "-_-") (pintype "passive"))
      (node (ref "C9") (pin "2") (pinfunction "2_2") (pintype "passive"))
      (node (ref "CM1") (pin "P$1") (pinfunction "SHIELD3_P$1") (pintype "passive"))
      (node (ref "CM1") (pin "P$2") (pinfunction "SHIELD2_P$2") (pintype "passive"))
      (node (ref "CM1") (pin "P$3") (pinfunction "SHIELD1_P$3") (pintype "passive"))
      (node (ref "CM1") (pin "P$4") (pinfunction "SHIELD_P$4") (pintype "passive"))
      (node (ref "D1") (pin "C") (pinfunction "C_C") (pintype "passive"))
      (node (ref "D2") (pin "C") (pinfunction "C_C") (pintype "passive"))
      (node (ref "D3") (pin "C") (pinfunction "C_C") (pintype "passive"))
      (node (ref "D4") (pin "C") (pinfunction "C_C") (pintype "passive"))
      (node (ref "D5") (pin "C") (pinfunction "C_C") (pintype "passive"))
      (node (ref "D6") (pin "C") (pinfunction "C_C") (pintype "passive"))
      (node (ref "D7") (pin "C") (pinfunction "C_C") (pintype "passive"))
      (node (ref "D8") (pin "C") (pinfunction "C_C") (pintype "passive"))
      (node (ref "J1") (pin "3") (pinfunction "GND_3") (pintype "passive"))
      (node (ref "J1") (pin "6") (pinfunction "GND_6") (pintype "passive"))
      (node (ref "J1") (pin "9") (pinfunction "GND_9") (pintype "passive"))
      (node (ref "J1") (pin "PAD1") (pinfunction "PAD_PAD1") (pintype "bidirectional"))
      (node (ref "J1") (pin "PAD2") (pinfunction "PAD_PAD2") (pintype "bidirectional"))
      (node (ref "J100") (pin "6") (pinfunction "VSS_6") (pintype "bidirectional"))
      (node (ref "J100") (pin "CGND1") (pinfunction "CGND_CGND1") (pintype "bidirectional"))
      (node (ref "J100") (pin "CGND2") (pinfunction "CGND_CGND2") (pintype "bidirectional"))
      (node (ref "J100") (pin "CGND3") (pinfunction "CGND_CGND3") (pintype "bidirectional"))
      (node (ref "J100") (pin "CGND4") (pinfunction "CGND_CGND4") (pintype "bidirectional"))
      (node (ref "J100") (pin "CGND5") (pinfunction "CGND_CGND5") (pintype "bidirectional"))
      (node (ref "J100") (pin "CGND6") (pinfunction "CGND_CGND6") (pintype "bidirectional"))
      (node (ref "J100") (pin "GND") (pinfunction "VSS_GND") (pintype "bidirectional"))
      (node (ref "J102") (pin "3") (pinfunction "GND_3") (pintype "passive"))
      (node (ref "J102") (pin "5") (pinfunction "GND_5") (pintype "passive"))
      (node (ref "J102") (pin "9") (pinfunction "GNDDET_9") (pintype "passive"))
      (node (ref "J3") (pin "3") (pinfunction "3_3") (pintype "passive"))
      (node (ref "J4") (pin "27") (pinfunction "27_27") (pintype "passive"))
      (node (ref "J4") (pin "28") (pinfunction "28_28") (pintype "passive"))
      (node (ref "J4") (pin "29") (pinfunction "29_29") (pintype "passive"))
      (node (ref "J4") (pin "30") (pinfunction "30_30") (pintype "passive"))
      (node (ref "J4") (pin "31") (pinfunction "31_31") (pintype "passive"))
      (node (ref "J4") (pin "32") (pinfunction "32_32") (pintype "passive"))
      (node (ref "J4") (pin "37") (pinfunction "37_37") (pintype "passive"))
      (node (ref "J4") (pin "38") (pinfunction "38_38") (pintype "passive"))
      (node (ref "JP100") (pin "2") (pinfunction "2_2") (pintype "passive"))
      (node (ref "JP2") (pin "6") (pinfunction "6_6") (pintype "passive"))
      (node (ref "Q2") (pin "2") (pinfunction "S_2") (pintype "passive"))
      (node (ref "Q4") (pin "2") (pinfunction "S_2") (pintype "passive"))
      (node (ref "R15") (pin "1") (pinfunction "1_1") (pintype "passive"))
      (node (ref "R16") (pin "1") (pinfunction "1_1") (pintype "passive"))
      (node (ref "R19") (pin "1") (pinfunction "1_1") (pintype "passive"))
      (node (ref "R25") (pin "10") (pinfunction "55_10") (pintype "passive"))
      (node (ref "R25") (pin "5") (pinfunction "55_5") (pintype "passive"))
      (node (ref "R26") (pin "10") (pinfunction "55_10") (pintype "passive"))
      (node (ref "R26") (pin "5") (pinfunction "55_5") (pintype "passive"))
      (node (ref "R30") (pin "1") (pinfunction "1_1") (pintype "passive"))
      (node (ref "R33") (pin "1") (pinfunction "1_1") (pintype "passive"))
      (node (ref "R39") (pin "1") (pinfunction "1_1") (pintype "passive"))
      (node (ref "R40") (pin "1") (pinfunction "1_1") (pintype "passive"))
      (node (ref "R42") (pin "1") (pinfunction "1_1") (pintype "passive"))
      (node (ref "R46") (pin "1") (pinfunction "1_1") (pintype "passive"))
      (node (ref "R51") (pin "1") (pinfunction "1_1") (pintype "passive"))
      (node (ref "R54") (pin "1") (pinfunction "1_1") (pintype "passive"))
      (node (ref "R56") (pin "1") (pinfunction "1_1") (pintype "passive"))
      (node (ref "R58") (pin "1") (pinfunction "1_1") (pintype "passive"))
      (node (ref "R59") (pin "2") (pinfunction "2_2") (pintype "passive"))
      (node (ref "R6") (pin "1") (pinfunction "1_1") (pintype "passive"))
      (node (ref "R79") (pin "1") (pinfunction "1_1") (pintype "passive"))
      (node (ref "SH1") (pin "P$1") (pinfunction "P$1_P$1") (pintype "power_in"))
      (node (ref "SH1") (pin "P$10") (pinfunction "P$1_P$10") (pintype "power_in"))
      (node (ref "SH1") (pin "P$11") (pinfunction "P$1_P$11") (pintype "power_in"))
      (node (ref "SH1") (pin "P$12") (pinfunction "P$1_P$12") (pintype "power_in"))
      (node (ref "SH1") (pin "P$2") (pinfunction "P$1_P$2") (pintype "power_in"))
      (node (ref "SH1") (pin "P$3") (pinfunction "P$1_P$3") (pintype "power_in"))
      (node (ref "SH1") (pin "P$4") (pinfunction "P$1_P$4") (pintype "power_in"))
      (node (ref "SH1") (pin "P$5") (pinfunction "P$1_P$5") (pintype "power_in"))
      (node (ref "SH1") (pin "P$6") (pinfunction "P$1_P$6") (pintype "power_in"))
      (node (ref "SH1") (pin "P$7") (pinfunction "P$1_P$7") (pintype "power_in"))
      (node (ref "SH1") (pin "P$8") (pinfunction "P$1_P$8") (pintype "power_in"))
      (node (ref "SH1") (pin "P$9") (pinfunction "P$1_P$9") (pintype "power_in"))
      (node (ref "U1") (pin "2") (pinfunction "GND_2") (pintype "power_in"))
      (node (ref "U11") (pin "2") (pinfunction "GND_2") (pintype "power_in"))
      (node (ref "U12") (pin "2") (pinfunction "GND_2") (pintype "power_in"))
      (node (ref "U13") (pin "2") (pinfunction "GND_2") (pintype "power_in"))
      (node (ref "U14") (pin "7") (pinfunction "GND_7") (pintype "power_in"))
      (node (ref "U14") (pin "EPAD") (pinfunction "GND_EPAD") (pintype "power_in"))
      (node (ref "U15") (pin "1") (pinfunction "GND_1") (pintype "power_in"))
      (node (ref "U15") (pin "11") (pinfunction "GND_11") (pintype "power_in"))
      (node (ref "U15") (pin "12") (pinfunction "GND_12") (pintype "power_in"))
      (node (ref "U15") (pin "16") (pinfunction "GND_16") (pintype "power_in"))
      (node (ref "U15") (pin "6") (pinfunction "LBO_6") (pintype "open_collector"))
      (node (ref "U15") (pin "7") (pinfunction "LBI_7") (pintype "input"))
      (node (ref "U15") (pin "9") (pinfunction "GND_9") (pintype "power_in"))
      (node (ref "U15") (pin "PAD") (pinfunction "GND_PAD") (pintype "power_in"))
      (node (ref "U16") (pin "6") (pinfunction "GND_6") (pintype "power_in"))
      (node (ref "U16") (pin "EPAD") (pinfunction "GND_EPAD") (pintype "power_in"))
      (node (ref "U17") (pin "4") (pinfunction "GND_4") (pintype "power_in"))
      (node (ref "U18") (pin "2") (pinfunction "GND_2") (pintype "power_in"))
      (node (ref "U19") (pin "1") (pinfunction "GND_1") (pintype "passive"))
      (node (ref "U19") (pin "3") (pinfunction "GND_3") (pintype "passive"))
      (node (ref "U19") (pin "4") (pinfunction "GND_4") (pintype "passive"))
      (node (ref "U19") (pin "6") (pinfunction "GND_6") (pintype "passive"))
      (node (ref "U19") (pin "7") (pinfunction "GND_7") (pintype "passive"))
      (node (ref "U2") (pin "2") (pinfunction "GND_2") (pintype "power_in"))
      (node (ref "U20") (pin "2") (pinfunction "GND_2") (pintype "input"))
      (node (ref "U21") (pin "2") (pinfunction "GND_2") (pintype "power_in"))
      (node (ref "U21") (pin "3") (pinfunction "GND_3") (pintype "power_in"))
      (node (ref "U21") (pin "5") (pinfunction "GND_5") (pintype "power_in"))
      (node (ref "U22") (pin "2") (pinfunction "V-_2") (pintype "power_in"))
      (node (ref "U22") (pin "6") (pinfunction "SD_6") (pintype "input"))
      (node (ref "U23") (pin "20") (pinfunction "LNAIN_LO_20") (pintype "input"))
      (node (ref "U23") (pin "26") (pinfunction "MIXIN_LO_26") (pintype "input"))
      (node (ref "U23") (pin "BODY") (pinfunction "BODY_BODY") (pintype "power_in"))
      (node (ref "U24") (pin "10") (pinfunction "GND_10") (pintype "power_in"))
      (node (ref "U24") (pin "11") (pinfunction "GND_11") (pintype "power_in"))
      (node (ref "U24") (pin "15") (pinfunction "GND_15") (pintype "power_in"))
      (node (ref "U24") (pin "19") (pinfunction "GND_19") (pintype "power_in"))
      (node (ref "U24") (pin "21") (pinfunction "GND_RF_21") (pintype "power_in"))
      (node (ref "U24") (pin "22") (pinfunction "GND_RF_22") (pintype "power_in"))
      (node (ref "U24") (pin "24") (pinfunction "GND_RF_24") (pintype "power_in"))
      (node (ref "U24") (pin "25") (pinfunction "GND_RF_25") (pintype "power_in"))
      (node (ref "U24") (pin "27") (pinfunction "GND_RF_27") (pintype "power_in"))
      (node (ref "U24") (pin "28") (pinfunction "GND_RF_28") (pintype "power_in"))
      (node (ref "U24") (pin "29") (pinfunction "GND_RF_29") (pintype "power_in"))
      (node (ref "U24") (pin "31") (pinfunction "GND_RF_31") (pintype "power_in"))
      (node (ref "U24") (pin "33") (pinfunction "GND_RF_33") (pintype "power_in"))
      (node (ref "U24") (pin "4") (pinfunction "GND_4") (pintype "power_in"))
      (node (ref "U24") (pin "49") (pinfunction "GND_49") (pintype "power_in"))
      (node (ref "U24") (pin "5") (pinfunction "GND_5") (pintype "power_in"))
      (node (ref "U24") (pin "6") (pinfunction "GND_6") (pintype "power_in"))
      (node (ref "U24") (pin "60") (pinfunction "GND_60") (pintype "power_in"))
      (node (ref "U24") (pin "61") (pinfunction "GND_RF_61") (pintype "power_in"))
      (node (ref "U24") (pin "62") (pinfunction "GND_RF_62") (pintype "power_in"))
      (node (ref "U24") (pin "64") (pinfunction "GND_64") (pintype "power_in"))
      (node (ref "U24") (pin "65") (pinfunction "GND_RF_65") (pintype "power_in"))
      (node (ref "U24") (pin "69") (pinfunction "GND_RF_69") (pintype "power_in"))
      (node (ref "U3") (pin "C4") (pinfunction "VSSQ_C4") (pintype "power_in"))
      (node (ref "U3") (pin "E7") (pinfunction "VSSIO_E7") (pintype "power_in"))
      (node (ref "U3") (pin "G5") (pinfunction "VSSIO_G5") (pintype "power_in"))
      (node (ref "U3") (pin "H10") (pinfunction "VSSIO_H10") (pintype "power_in"))
      (node (ref "U3") (pin "J5") (pinfunction "VSSIO_J5") (pintype "power_in"))
      (node (ref "U3") (pin "K8") (pinfunction "VSSIO_K8") (pintype "power_in"))
      (node (ref "U3") (pin "N2") (pinfunction "VSSQ_N2") (pintype "power_in"))
      (node (ref "U3") (pin "N5") (pinfunction "VSSQ_N5") (pintype "power_in"))
      (node (ref "U3") (pin "P4") (pinfunction "VSSQ_P4") (pintype "power_in"))
      (node (ref "U3") (pin "P6") (pinfunction "VSSQ_P6") (pintype "power_in"))
      (node (ref "U4") (pin "3") (pinfunction "GND_3") (pintype "bidirectional"))
      (node (ref "U5") (pin "GND") (pinfunction "GND_GND") (pintype "power_in"))
      (node (ref "U6") (pin "1") (pinfunction "GND1_1") (pintype "bidirectional"))
      (node (ref "U6") (pin "2") (pinfunction "GND2_2") (pintype "bidirectional"))
      (node (ref "U7") (pin "D8") (pinfunction "DGND_D8") (pintype "bidirectional"))
      (node (ref "U7") (pin "D9") (pinfunction "DGND_D9") (pintype "bidirectional"))
      (node (ref "U7") (pin "E10") (pinfunction "DGND_E10") (pintype "bidirectional"))
      (node (ref "U7") (pin "E11") (pinfunction "DGND_E11") (pintype "bidirectional"))
      (node (ref "U7") (pin "E12") (pinfunction "DGND_E12") (pintype "bidirectional"))
      (node (ref "U7") (pin "E5") (pinfunction "DGND_E5") (pintype "bidirectional"))
      (node (ref "U7") (pin "E6") (pinfunction "DGND_E6") (pintype "bidirectional"))
      (node (ref "U7") (pin "E7") (pinfunction "DGND_E7") (pintype "bidirectional"))
      (node (ref "U7") (pin "E8") (pinfunction "DGND_E8") (pintype "bidirectional"))
      (node (ref "U7") (pin "E9") (pinfunction "DGND_E9") (pintype "bidirectional"))
      (node (ref "U7") (pin "F12") (pinfunction "DGND_F12") (pintype "bidirectional"))
      (node (ref "U7") (pin "F5") (pinfunction "DGND_F5") (pintype "bidirectional"))
      (node (ref "U7") (pin "G12") (pinfunction "DGND_G12") (pintype "bidirectional"))
      (node (ref "U7") (pin "G5") (pinfunction "DGND_G5") (pintype "bidirectional"))
      (node (ref "U7") (pin "H12") (pinfunction "DGND_H12") (pintype "bidirectional"))
      (node (ref "U7") (pin "H13") (pinfunction "DGND_H13") (pintype "bidirectional"))
      (node (ref "U7") (pin "H4") (pinfunction "DGND_H4") (pintype "bidirectional"))
      (node (ref "U7") (pin "H5") (pinfunction "DGND_H5") (pintype "bidirectional"))
      (node (ref "U7") (pin "J12") (pinfunction "DGND_J12") (pintype "bidirectional"))
      (node (ref "U7") (pin "J13") (pinfunction "DGND_J13") (pintype "bidirectional"))
      (node (ref "U7") (pin "J4") (pinfunction "DGND_J4") (pintype "bidirectional"))
      (node (ref "U7") (pin "J5") (pinfunction "DGND_J5") (pintype "bidirectional"))
      (node (ref "U7") (pin "K12") (pinfunction "DGND_K12") (pintype "bidirectional"))
      (node (ref "U7") (pin "K5") (pinfunction "DGND_K5") (pintype "bidirectional"))
      (node (ref "U7") (pin "L12") (pinfunction "DGND_L12") (pintype "bidirectional"))
      (node (ref "U7") (pin "L5") (pinfunction "DGND_L5") (pintype "bidirectional"))
      (node (ref "U7") (pin "M10") (pinfunction "DGND_M10") (pintype "bidirectional"))
      (node (ref "U7") (pin "M11") (pinfunction "DGND_M11") (pintype "bidirectional"))
      (node (ref "U7") (pin "M12") (pinfunction "DGND_M12") (pintype "bidirectional"))
      (node (ref "U7") (pin "M5") (pinfunction "DGND_M5") (pintype "bidirectional"))
      (node (ref "U7") (pin "M6") (pinfunction "DGND_M6") (pintype "bidirectional"))
      (node (ref "U7") (pin "M7") (pinfunction "DGND_M7") (pintype "bidirectional"))
      (node (ref "U7") (pin "M8") (pinfunction "DGND_M8") (pintype "bidirectional"))
      (node (ref "U7") (pin "M9") (pinfunction "DGND_M9") (pintype "bidirectional"))
      (node (ref "U7") (pin "N8") (pinfunction "DGND_N8") (pintype "bidirectional"))
      (node (ref "U7") (pin "N9") (pinfunction "DGND_N9") (pintype "bidirectional"))
      (node (ref "U8") (pin "2") (pinfunction "GND_2") (pintype "input"))
      (node (ref "U9") (pin "2") (pinfunction "GND_2") (pintype "input"))
      (node (ref "Y1") (pin "2") (pinfunction "GND_2") (pintype "power_in"))
      (node (ref "Y1") (pin "4") (pinfunction "GND_4") (pintype "power_in"))
    )
    (net (code "19") (name "I0") (class "Default")
      (node (ref "TP20") (pin "1") (pinfunction "1_1") (pintype "passive"))
      (node (ref "U23") (pin "12") (pinfunction "I0_12") (pintype "output"))
      (node (ref "U7") (pin "A2") (pinfunction "MCASP0_FSX_A2") (pintype "bidirectional"))
    )
    (net (code "20") (name "I1") (class "Default")
      (node (ref "TP21") (pin "1") (pinfunction "1_1") (pintype "passive"))
      (node (ref "U23") (pin "13") (pinfunction "I1_13") (pintype "output"))
      (node (ref "U7") (pin "A1") (pinfunction "MCASP0_ACLKX_A1") (pintype "bidirectional"))
    )
    (net (code "21") (name "I2C0_SCL") (class "Default")
      (node (ref "J1") (pin "18") (pinfunction "DEBUG-1_18") (pintype "passive"))
      (node (ref "R73") (pin "1") (pinfunction "1_1") (pintype "passive"))
      (node (ref "TP155") (pin "P$1") (pinfunction "1_P$1") (pintype "bidirectional"))
      (node (ref "U18") (pin "3") (pinfunction "I2_3") (pintype "bidirectional"))
    )
    (net (code "22") (name "I2C0_SDA") (class "Default")
      (node (ref "J1") (pin "19") (pinfunction "DEBUG-2_19") (pintype "passive"))
      (node (ref "R74") (pin "1") (pinfunction "1_1") (pintype "passive"))
      (node (ref "TP151") (pin "P$1") (pinfunction "1_P$1") (pintype "bidirectional"))
      (node (ref "U18") (pin "1") (pinfunction "I1_1") (pintype "bidirectional"))
    )
    (net (code "23") (name "MAX-CLKOUT") (class "Default")
      (node (ref "TP72") (pin "1") (pinfunction "1_1") (pintype "passive"))
      (node (ref "U22") (pin "5") (pinfunction "OUT_5") (pintype "output"))
      (node (ref "U7") (pin "B4") (pinfunction "XDMA_EVENT_INTR1_B4") (pintype "bidirectional"))
    )
    (net (code "24") (name "MAX-EN") (class "Default")
      (node (ref "R30") (pin "2") (pinfunction "2_2") (pintype "passive"))
      (node (ref "TP19") (pin "P$1") (pinfunction "1_P$1") (pintype "bidirectional"))
      (node (ref "U7") (pin "F16") (pinfunction "MII1_RX_DV_F16") (pintype "bidirectional"))
      (node (ref "U8") (pin "3") (pinfunction "EN_3") (pintype "input"))
      (node (ref "U9") (pin "3") (pinfunction "EN_3") (pintype "input"))
    )
    (net (code "25") (name "MAX-RF") (class "Default")
      (node (ref "C63") (pin "1") (pinfunction "1_1") (pintype "passive"))
      (node (ref "U19") (pin "5") (pinfunction "PORT2_5") (pintype "passive"))
    )
    (net (code "26") (name "MAX_LD") (class "Default")
      (node (ref "TP70") (pin "P$1") (pinfunction "1_P$1") (pintype "bidirectional"))
      (node (ref "U23") (pin "17") (pinfunction "LD_17") (pintype "output"))
      (node (ref "U7") (pin "G15") (pinfunction "MII1_TXD3_G15") (pintype "bidirectional"))
    )
    (net (code "27") (name "MAX_SPI1_CS0") (class "Default")
      (node (ref "JP2") (pin "3") (pinfunction "3_3") (pintype "passive"))
      (node (ref "R12") (pin "1") (pinfunction "1_1") (pintype "passive"))
      (node (ref "U23") (pin "9") (pinfunction "~{CSN}_9") (pintype "input"))
      (node (ref "U7") (pin "J14") (pinfunction "RMII1_REF_CLK_J14") (pintype "bidirectional"))
    )
    (net (code "28") (name "MAX_SPI1_D0") (class "Default")
      (node (ref "JP2") (pin "5") (pinfunction "5_5") (pintype "passive"))
      (node (ref "U23") (pin "7") (pinfunction "SDATA_7") (pintype "bidirectional"))
      (node (ref "U7") (pin "F14") (pinfunction "MII1_CRS_F14") (pintype "bidirectional"))
    )
    (net (code "29") (name "MAX_SPI1_SCLK") (class "Default")
      (node (ref "JP2") (pin "4") (pinfunction "4_4") (pintype "passive"))
      (node (ref "U23") (pin "8") (pinfunction "SCLK_8") (pintype "input"))
      (node (ref "U7") (pin "F15") (pinfunction "MII1_COL_F15") (pintype "bidirectional"))
    )
    (net (code "30") (name "MAX_~{SHDN}") (class "Default")
      (node (ref "R16") (pin "2") (pinfunction "2_2") (pintype "passive"))
      (node (ref "TP148") (pin "P$1") (pinfunction "1_P$1") (pintype "bidirectional"))
      (node (ref "U23") (pin "18") (pinfunction "~{SHDN}_18") (pintype "input"))
      (node (ref "U7") (pin "G14") (pinfunction "MII1_TX_EN_G14") (pintype "bidirectional"))
    )
    (net (code "31") (name "N$103") (class "Default")
      (node (ref "J4") (pin "1") (pinfunction "1_1") (pintype "passive"))
      (node (ref "J4") (pin "2") (pinfunction "2_2") (pintype "passive"))
      (node (ref "TP62") (pin "P$1") (pinfunction "1_P$1") (pintype "bidirectional"))
    )
    (net (code "32") (name "Net-(C17-Pad1)") (class "Default")
      (node (ref "C17") (pin "1") (pinfunction "1_1") (pintype "passive"))
      (node (ref "R11") (pin "2") (pinfunction "2_2") (pintype "passive"))
    )
    (net (code "33") (name "Net-(C33-Pad1)") (class "Default")
      (node (ref "C33") (pin "1") (pinfunction "1_1") (pintype "passive"))
      (node (ref "R33") (pin "2") (pinfunction "2_2") (pintype "passive"))
      (node (ref "R38") (pin "2") (pinfunction "2_2") (pintype "passive"))
    )
    (net (code "34") (name "Net-(C63-Pad2)") (class "Default")
      (node (ref "C63") (pin "2") (pinfunction "2_2") (pintype "passive"))
      (node (ref "C64") (pin "2") (pinfunction "2_2") (pintype "passive"))
      (node (ref "L3") (pin "1") (pinfunction "1_1") (pintype "passive"))
    )
    (net (code "35") (name "Net-(D1-PadA)") (class "Default")
      (node (ref "D1") (pin "A") (pinfunction "A_A") (pintype "passive"))
      (node (ref "R1") (pin "2") (pinfunction "2_2") (pintype "passive"))
    )
    (net (code "36") (name "Net-(D2-PadA)") (class "Default")
      (node (ref "D2") (pin "A") (pinfunction "A_A") (pintype "passive"))
      (node (ref "R2") (pin "2") (pinfunction "2_2") (pintype "passive"))
    )
    (net (code "37") (name "Net-(D3-PadA)") (class "Default")
      (node (ref "D3") (pin "A") (pinfunction "A_A") (pintype "passive"))
      (node (ref "R3") (pin "2") (pinfunction "2_2") (pintype "passive"))
    )
    (net (code "38") (name "Net-(D4-PadA)") (class "Default")
      (node (ref "D4") (pin "A") (pinfunction "A_A") (pintype "passive"))
      (node (ref "R4") (pin "2") (pinfunction "2_2") (pintype "passive"))
    )
    (net (code "39") (name "Net-(D5-PadA)") (class "Default")
      (node (ref "D5") (pin "A") (pinfunction "A_A") (pintype "passive"))
      (node (ref "R5") (pin "2") (pinfunction "2_2") (pintype "passive"))
    )
    (net (code "40") (name "Net-(D6-PadA)") (class "Default")
      (node (ref "D6") (pin "A") (pinfunction "A_A") (pintype "passive"))
      (node (ref "R49") (pin "1") (pinfunction "1_1") (pintype "passive"))
    )
    (net (code "41") (name "Net-(D7-PadA)") (class "Default")
      (node (ref "D7") (pin "A") (pinfunction "A_A") (pintype "passive"))
      (node (ref "R61") (pin "1") (pinfunction "1_1") (pintype "passive"))
    )
    (net (code "42") (name "Net-(D8-PadA)") (class "Default")
      (node (ref "D8") (pin "A") (pinfunction "A_A") (pintype "passive"))
      (node (ref "R62") (pin "1") (pinfunction "1_1") (pintype "passive"))
    )
    (net (code "43") (name "Net-(D9-PadCATHODE)") (class "Default")
      (node (ref "D9") (pin "CATHODE") (pinfunction "CATHODE_CATHODE") (pintype "passive"))
      (node (ref "R76") (pin "2") (pinfunction "2_2") (pintype "passive"))
    )
    (net (code "44") (name "Net-(D10-PadC)") (class "Default")
      (node (ref "D10") (pin "C") (pinfunction "C_C") (pintype "passive"))
      (node (ref "R17") (pin "1") (pinfunction "1_1") (pintype "passive"))
    )
    (net (code "45") (name "Net-(J100-CD#)") (class "Default")
      (node (ref "J100") (pin "CD") (pinfunction "CD#_CD") (pintype "bidirectional"))
      (node (ref "R8") (pin "6") (pinfunction "66_6") (pintype "passive"))
      (node (ref "TP22") (pin "P$1") (pinfunction "1_P$1") (pintype "bidirectional"))
      (node (ref "U7") (pin "C14") (pinfunction "SPI0_CS1_C14") (pintype "bidirectional"))
    )
    (net (code "46") (name "Net-(J100-CLK)") (class "Default")
      (node (ref "J100") (pin "5") (pinfunction "CLK_5") (pintype "bidirectional"))
      (node (ref "R8") (pin "3") (pinfunction "33_3") (pintype "passive"))
      (node (ref "U7") (pin "B15") (pinfunction "MMC0_CLK_B15") (pintype "bidirectional"))
    )
    (net (code "47") (name "Net-(J100-CMD{slash}DI)") (class "Default")
      (node (ref "J100") (pin "3") (pinfunction "CMD/DI_3") (pintype "bidirectional"))
      (node (ref "R8") (pin "8") (pinfunction "88_8") (pintype "passive"))
      (node (ref "U7") (pin "B16") (pinfunction "MMC0_CMD_B16") (pintype "bidirectional"))
    )
    (net (code "48") (name "Net-(J100-DAT0{slash}DO)") (class "Default")
      (node (ref "J100") (pin "7") (pinfunction "DAT0/DO_7") (pintype "bidirectional"))
      (node (ref "R8") (pin "7") (pinfunction "77_7") (pintype "passive"))
      (node (ref "U7") (pin "A16") (pinfunction "MMC0_DAT0_A16") (pintype "bidirectional"))
    )
    (net (code "49") (name "Net-(J100-DAT1)") (class "Default")
      (node (ref "J100") (pin "8") (pinfunction "DAT1_8") (pintype "bidirectional"))
      (node (ref "R8") (pin "4") (pinfunction "44_4") (pintype "passive"))
      (node (ref "U7") (pin "A15") (pinfunction "MMC0_DAT1_A15") (pintype "bidirectional"))
    )
    (net (code "50") (name "Net-(J100-DAT2)") (class "Default")
      (node (ref "J100") (pin "1") (pinfunction "DAT2_1") (pintype "bidirectional"))
      (node (ref "R8") (pin "9") (pinfunction "99_9") (pintype "passive"))
      (node (ref "U7") (pin "C16") (pinfunction "MMC0_DAT2_C16") (pintype "bidirectional"))
    )
    (net (code "51") (name "Net-(J100-DAT3{slash}CS)") (class "Default")
      (node (ref "J100") (pin "2") (pinfunction "DAT3/CS_2") (pintype "bidirectional"))
      (node (ref "R8") (pin "2") (pinfunction "22_2") (pintype "passive"))
      (node (ref "U7") (pin "C15") (pinfunction "MMC0_DAT3_C15") (pintype "bidirectional"))
    )
    (net (code "52") (name "Net-(J102-NC{slash}TDI)") (class "Default")
      (node (ref "J102") (pin "8") (pinfunction "NC/TDI_8") (pintype "passive"))
      (node (ref "U7") (pin "C1") (pinfunction "TDI_C1") (pintype "bidirectional"))
    )
    (net (code "53") (name "Net-(J102-SWDCLK{slash}TCK)") (class "Default")
      (node (ref "J102") (pin "4") (pinfunction "SWDCLK/TCK_4") (pintype "passive"))
      (node (ref "U7") (pin "D1") (pinfunction "TCK_D1") (pintype "bidirectional"))
    )
    (net (code "54") (name "Net-(J102-SWDIO{slash}TMS)") (class "Default")
      (node (ref "J102") (pin "2") (pinfunction "SWDIO/TMS_2") (pintype "passive"))
      (node (ref "U7") (pin "D2") (pinfunction "TMS_D2") (pintype "bidirectional"))
    )
    (net (code "55") (name "Net-(J102-SWO{slash}TDO)") (class "Default")
      (node (ref "J102") (pin "6") (pinfunction "SWO/TDO_6") (pintype "passive"))
      (node (ref "U7") (pin "C2") (pinfunction "TDO_C2") (pintype "bidirectional"))
    )
    (net (code "56") (name "Net-(J102-~{RESET})") (class "Default")
      (node (ref "J102") (pin "10") (pinfunction "~{RESET}_10") (pintype "passive"))
      (node (ref "JP1") (pin "2") (pinfunction "2_2") (pintype "passive"))
    )
    (net (code "57") (name "Net-(JP101-Pad2)") (class "Default")
      (node (ref "JP101") (pin "2") (pinfunction "2_2") (pintype "passive"))
      (node (ref "Q1") (pin "E") (pinfunction "E_E") (pintype "passive"))
      (node (ref "R23") (pin "2") (pinfunction "2_2") (pintype "passive"))
      (node (ref "R28") (pin "2") (pinfunction "2_2") (pintype "passive"))
    )
    (net (code "58") (name "Net-(L1-Pad1)") (class "Default")
      (node (ref "L1") (pin "1") (pinfunction "1_1") (pintype "passive"))
      (node (ref "U15") (pin "14") (pinfunction "SW_14") (pintype "output"))
      (node (ref "U15") (pin "15") (pinfunction "SW_15") (pintype "output"))
    )
    (net (code "59") (name "Net-(Q3A-G)") (class "Default")
      (node (ref "Q3") (pin "1") (pinfunction "G_1") (pintype "passive"))
      (node (ref "R35") (pin "2") (pinfunction "2_2") (pintype "passive"))
    )
    (net (code "60") (name "Net-(Q3A-S)") (class "Default")
      (node (ref "Q3") (pin "5") (pinfunction "S_5") (pintype "passive"))
      (node (ref "R48") (pin "2") (pinfunction "2_2") (pintype "passive"))
    )
    (net (code "61") (name "Net-(Q3B-G)") (class "Default")
      (node (ref "Q3") (pin "3") (pinfunction "G_3") (pintype "passive"))
      (node (ref "R43") (pin "2") (pinfunction "2_2") (pintype "passive"))
    )
    (net (code "62") (name "Net-(Q3B-S)") (class "Default")
      (node (ref "Q3") (pin "2") (pinfunction "S_2") (pintype "passive"))
      (node (ref "R41") (pin "2") (pinfunction "2_2") (pintype "passive"))
    )
    (net (code "63") (name "Net-(Q4-D)") (class "Default")
      (node (ref "Q4") (pin "3") (pinfunction "D_3") (pintype "passive"))
      (node (ref "Q6") (pin "3") (pinfunction "G_3") (pintype "passive"))
      (node (ref "R52") (pin "1") (pinfunction "1_1") (pintype "passive"))
    )
    (net (code "64") (name "Net-(Q5-S)") (class "Default")
      (node (ref "Q5") (pin "4") (pinfunction "S_4") (pintype "passive"))
      (node (ref "R63") (pin "2") (pinfunction "2_2") (pintype "passive"))
      (node (ref "R64") (pin "2") (pinfunction "2_2") (pintype "passive"))
      (node (ref "U14") (pin "15") (pinfunction "RS-_15") (pintype "passive"))
    )
    (net (code "65") (name "Net-(R9-22)") (class "Default")
      (node (ref "R9") (pin "2") (pinfunction "22_2") (pintype "passive"))
      (node (ref "U3") (pin "M5") (pinfunction "CMD_M5") (pintype "input"))
      (node (ref "U7") (pin "P1") (pinfunction "GPMC_CSN2_P1") (pintype "bidirectional"))
    )
    (net (code "66") (name "Net-(R9-33)") (class "Default")
      (node (ref "R9") (pin "3") (pinfunction "33_3") (pintype "passive"))
      (node (ref "U3") (pin "B4") (pinfunction "D5_B4") (pintype "input"))
      (node (ref "U7") (pin "T1") (pinfunction "GPMC_AD5_T1") (pintype "bidirectional"))
    )
    (net (code "67") (name "Net-(R9-44)") (class "Default")
      (node (ref "R9") (pin "4") (pinfunction "44_4") (pintype "passive"))
      (node (ref "U3") (pin "B3") (pinfunction "D4_B3") (pintype "input"))
      (node (ref "U7") (pin "T2") (pinfunction "GPMC_AD4_T2") (pintype "bidirectional"))
    )
    (net (code "68") (name "Net-(R9-66)") (class "Default")
      (node (ref "R9") (pin "6") (pinfunction "66_6") (pintype "passive"))
      (node (ref "U3") (pin "A3") (pinfunction "D0_A3") (pintype "input"))
      (node (ref "U7") (pin "R3") (pinfunction "GPMC_AD0_R3") (pintype "bidirectional"))
    )
    (net (code "69") (name "Net-(R9-77)") (class "Default")
      (node (ref "R9") (pin "7") (pinfunction "77_7") (pintype "passive"))
      (node (ref "U3") (pin "B2") (pinfunction "D3_B2") (pintype "input"))
      (node (ref "U7") (pin "T3") (pinfunction "GPMC_AD3_T3") (pintype "bidirectional"))
    )
    (net (code "70") (name "Net-(R9-88)") (class "Default")
      (node (ref "R9") (pin "8") (pinfunction "88_8") (pintype "passive"))
      (node (ref "U3") (pin "M6") (pinfunction "SCK_M6") (pintype "input"))
      (node (ref "U7") (pin "P2") (pinfunction "GPMC_CSN1_P2") (pintype "bidirectional"))
    )
    (net (code "71") (name "Net-(R10-11)") (class "Default")
      (node (ref "R10") (pin "1") (pinfunction "11_1") (pintype "passive"))
      (node (ref "U3") (pin "A4") (pinfunction "D1_A4") (pintype "input"))
      (node (ref "U7") (pin "R2") (pinfunction "GPMC_AD1_R2") (pintype "bidirectional"))
    )
    (net (code "72") (name "Net-(R10-22)") (class "Default")
      (node (ref "R10") (pin "2") (pinfunction "22_2") (pintype "passive"))
      (node (ref "U3") (pin "B6") (pinfunction "D7_B6") (pintype "input"))
      (node (ref "U7") (pin "R4") (pinfunction "GPMC_AD7_R4") (pintype "bidirectional"))
    )
    (net (code "73") (name "Net-(R10-33)") (class "Default")
      (node (ref "R10") (pin "3") (pinfunction "33_3") (pintype "passive"))
      (node (ref "U3") (pin "K5") (pinfunction "~{RST}_K5") (pintype "input"))
      (node (ref "U7") (pin "R13") (pinfunction "GPMC_A4_R13") (pintype "bidirectional"))
    )
    (net (code "74") (name "Net-(R10-88)") (class "Default")
      (node (ref "R10") (pin "8") (pinfunction "88_8") (pintype "passive"))
      (node (ref "U3") (pin "B5") (pinfunction "D6_B5") (pintype "bidirectional"))
      (node (ref "U7") (pin "P4") (pinfunction "GPMC_AD6_P4") (pintype "bidirectional"))
    )
    (net (code "75") (name "Net-(R10-99)") (class "Default")
      (node (ref "R10") (pin "9") (pinfunction "99_9") (pintype "passive"))
      (node (ref "U3") (pin "A5") (pinfunction "D2_A5") (pintype "input"))
      (node (ref "U7") (pin "R1") (pinfunction "GPMC_AD2_R1") (pintype "bidirectional"))
    )
    (net (code "76") (name "Net-(R24-22)") (class "Default")
      (node (ref "JP106") (pin "1") (pinfunction "1_1") (pintype "passive"))
      (node (ref "R24") (pin "2") (pinfunction "22_2") (pintype "passive"))
    )
    (net (code "77") (name "Net-(R24-33)") (class "Default")
      (node (ref "JP108") (pin "3") (pinfunction "3_3") (pintype "passive"))
      (node (ref "R24") (pin "3") (pinfunction "33_3") (pintype "passive"))
    )
    (net (code "78") (name "Net-(R24-44)") (class "Default")
      (node (ref "R24") (pin "4") (pinfunction "44_4") (pintype "passive"))
      (node (ref "U7") (pin "L1") (pinfunction "LCD_DATA14_L1") (pintype "bidirectional"))
    )
    (net (code "79") (name "Net-(R24-66)") (class "Default")
      (node (ref "JP109") (pin "3") (pinfunction "3_3") (pintype "passive"))
      (node (ref "R24") (pin "6") (pinfunction "66_6") (pintype "passive"))
    )
    (net (code "80") (name "Net-(R24-88)") (class "Default")
      (node (ref "JP107") (pin "3") (pinfunction "3_3") (pintype "passive"))
      (node (ref "R24") (pin "8") (pinfunction "88_8") (pintype "passive"))
    )
    (net (code "81") (name "Net-(R24-99)") (class "Default")
      (node (ref "JP105") (pin "1") (pinfunction "1_1") (pintype "passive"))
      (node (ref "R24") (pin "9") (pinfunction "99_9") (pintype "passive"))
    )
    (net (code "82") (name "Net-(R25-11)") (class "Default")
      (node (ref "JP107") (pin "1") (pinfunction "1_1") (pintype "passive"))
      (node (ref "R25") (pin "1") (pinfunction "11_1") (pintype "passive"))
    )
    (net (code "83") (name "Net-(R25-22)") (class "Default")
      (node (ref "JP106") (pin "3") (pinfunction "3_3") (pintype "passive"))
      (node (ref "R25") (pin "2") (pinfunction "22_2") (pintype "passive"))
    )
    (net (code "84") (name "Net-(R25-33)") (class "Default")
      (node (ref "JP105") (pin "3") (pinfunction "3_3") (pintype "passive"))
      (node (ref "R25") (pin "3") (pinfunction "33_3") (pintype "passive"))
    )
    (net (code "85") (name "Net-(R25-44)") (class "Default")
      (node (ref "R25") (pin "4") (pinfunction "44_4") (pintype "passive"))
      (node (ref "U7") (pin "H1") (pinfunction "LCD_DATA5_H1") (pintype "bidirectional"))
    )
    (net (code "86") (name "Net-(R25-66)") (class "Default")
      (node (ref "JP109") (pin "1") (pinfunction "1_1") (pintype "passive"))
      (node (ref "R25") (pin "6") (pinfunction "66_6") (pintype "passive"))
    )
    (net (code "87") (name "Net-(R25-77)") (class "Default")
      (node (ref "R25") (pin "7") (pinfunction "77_7") (pintype "passive"))
      (node (ref "U7") (pin "J3") (pinfunction "LCD_DATA6_J3") (pintype "bidirectional"))
    )
    (net (code "88") (name "Net-(R25-99)") (class "Default")
      (node (ref "JP108") (pin "1") (pinfunction "1_1") (pintype "passive"))
      (node (ref "R25") (pin "9") (pinfunction "99_9") (pintype "passive"))
    )
    (net (code "89") (name "Net-(R26-11)") (class "Default")
      (node (ref "R26") (pin "1") (pinfunction "11_1") (pintype "passive"))
      (node (ref "U7") (pin "M3") (pinfunction "LCD_DATA15_M3") (pintype "bidirectional"))
    )
    (net (code "90") (name "Net-(R26-22)") (class "Default")
      (node (ref "R26") (pin "2") (pinfunction "22_2") (pintype "passive"))
      (node (ref "U7") (pin "L3") (pinfunction "LCD_DATA12_L3") (pintype "bidirectional"))
    )
    (net (code "91") (name "Net-(R26-33)") (class "Default")
      (node (ref "R26") (pin "3") (pinfunction "33_3") (pintype "passive"))
      (node (ref "U7") (pin "K2") (pinfunction "LCD_DATA10_K2") (pintype "bidirectional"))
    )
    (net (code "92") (name "Net-(R26-44)") (class "Default")
      (node (ref "R26") (pin "4") (pinfunction "44_4") (pintype "passive"))
      (node (ref "U7") (pin "J1") (pinfunction "LCD_DATA8_J1") (pintype "bidirectional"))
    )
    (net (code "93") (name "Net-(R26-66)") (class "Default")
      (node (ref "R26") (pin "6") (pinfunction "66_6") (pintype "passive"))
      (node (ref "U7") (pin "J2") (pinfunction "LCD_DATA7_J2") (pintype "bidirectional"))
    )
    (net (code "94") (name "Net-(R26-77)") (class "Default")
      (node (ref "R26") (pin "7") (pinfunction "77_7") (pintype "passive"))
      (node (ref "U7") (pin "K3") (pinfunction "LCD_DATA9_K3") (pintype "bidirectional"))
    )
    (net (code "95") (name "Net-(R26-88)") (class "Default")
      (node (ref "R26") (pin "8") (pinfunction "88_8") (pintype "passive"))
      (node (ref "U7") (pin "K1") (pinfunction "LCD_DATA11_K1") (pintype "bidirectional"))
    )
    (net (code "96") (name "Net-(R26-99)") (class "Default")
      (node (ref "R26") (pin "9") (pinfunction "99_9") (pintype "passive"))
      (node (ref "U7") (pin "L2") (pinfunction "LCD_DATA13_L2") (pintype "bidirectional"))
    )
    (net (code "97") (name "Net-(TP7-1)") (class "Default")
      (node (ref "TP7") (pin "P$1") (pinfunction "1_P$1") (pintype "passive"))
      (node (ref "U24") (pin "40") (pinfunction "P1PPS_40") (pintype "output"))
    )
    (net (code "98") (name "Net-(TP8-1)") (class "Default")
      (node (ref "TP8") (pin "P$1") (pinfunction "1_P$1") (pintype "passive"))
      (node (ref "U24") (pin "17") (pinfunction "V12O_RTC_17") (pintype "output"))
    )
    (net (code "99") (name "Net-(TP9-1)") (class "Default")
      (node (ref "C46") (pin "2") (pinfunction "2_2") (pintype "passive"))
      (node (ref "TP9") (pin "P$1") (pinfunction "1_P$1") (pintype "passive"))
      (node (ref "U23") (pin "3") (pinfunction "XTAL_3") (pintype "input"))
    )
    (net (code "100") (name "Net-(TP12-1)") (class "Default")
      (node (ref "TP12") (pin "P$1") (pinfunction "1_P$1") (pintype "bidirectional"))
      (node (ref "U7") (pin "E14") (pinfunction "MII1_RXD0_E14") (pintype "bidirectional"))
    )
    (net (code "101") (name "Net-(TP13-1)") (class "Default")
      (node (ref "TP13") (pin "P$1") (pinfunction "1_P$1") (pintype "bidirectional"))
      (node (ref "U7") (pin "D16") (pinfunction "MII1_RXD1_D16") (pintype "bidirectional"))
    )
    (net (code "102") (name "Net-(TP14-1)") (class "Default")
      (node (ref "C18") (pin "1") (pinfunction "1_1") (pintype "passive"))
      (node (ref "JP104") (pin "1") (pinfunction "1_1") (pintype "passive"))
      (node (ref "TP14") (pin "P$1") (pinfunction "1_P$1") (pintype "bidirectional"))
      (node (ref "TP164") (pin "P$1") (pinfunction "1_P$1") (pintype "bidirectional"))
      (node (ref "U4") (pin "5") (pinfunction "VCC_5") (pintype "bidirectional"))
      (node (ref "U7") (pin "K11") (pinfunction "SYS_RTC_1P8V_K11") (pintype "power_in"))
      (node (ref "U7") (pin "L11") (pinfunction "SYS_RTC_1P8V_L11") (pintype "power_in"))
    )
    (net (code "103") (name "Net-(TP16-1)") (class "Default")
      (node (ref "TP16") (pin "P$1") (pinfunction "1_P$1") (pintype "bidirectional"))
      (node (ref "U7") (pin "D15") (pinfunction "MII1_RXD2_D15") (pintype "bidirectional"))
    )
    (net (code "104") (name "Net-(TP17-1)") (class "Default")
      (node (ref "TP17") (pin "P$1") (pinfunction "1_P$1") (pintype "bidirectional"))
      (node (ref "U7") (pin "D14") (pinfunction "MII1_RXD3_D14") (pintype "bidirectional"))
    )
    (net (code "105") (name "Net-(TP23-1)") (class "Default")
      (node (ref "TP23") (pin "P$1") (pinfunction "1_P$1") (pintype "bidirectional"))
      (node (ref "U7") (pin "C4") (pinfunction "MCASP0_AHCLKX_C4") (pintype "bidirectional"))
    )
    (net (code "106") (name "Net-(TP24-1)") (class "Default")
      (node (ref "TP24") (pin "P$1") (pinfunction "1_P$1") (pintype "bidirectional"))
      (node (ref "U7") (pin "C3") (pinfunction "MCASP0_AXR1_C3") (pintype "bidirectional"))
    )
    (net (code "107") (name "Net-(TP26-1)") (class "Default")
      (node (ref "TP26") (pin "P$1") (pinfunction "1_P$1") (pintype "bidirectional"))
      (node (ref "U7") (pin "B3") (pinfunction "MCASP0_FSR_B3") (pintype "bidirectional"))
    )
    (net (code "108") (name "Net-(TP28-1)") (class "Default")
      (node (ref "C61") (pin "2") (pinfunction "2_2") (pintype "passive"))
      (node (ref "R21") (pin "1") (pinfunction "1_1") (pintype "passive"))
      (node (ref "TP28") (pin "P$1") (pinfunction "1_P$1") (pintype "passive"))
      (node (ref "U24") (pin "1") (pinfunction "RSTN_1") (pintype "input"))
    )
    (net (code "109") (name "Net-(TP29-1)") (class "Default")
      (node (ref "R17") (pin "2") (pinfunction "2_2") (pintype "passive"))
      (node (ref "TP29") (pin "P$1") (pinfunction "1_P$1") (pintype "passive"))
      (node (ref "U24") (pin "7") (pinfunction "LED_7") (pintype "output"))
    )
    (net (code "110") (name "Net-(TP30-1)") (class "Default")
      (node (ref "TP30") (pin "P$1") (pinfunction "1_P$1") (pintype "bidirectional"))
      (node (ref "U7") (pin "A4") (pinfunction "XDMA_EVENT_INTR0_A4") (pintype "bidirectional"))
    )
    (net (code "111") (name "Net-(TP31-1)") (class "Default")
      (node (ref "R19") (pin "2") (pinfunction "2_2") (pintype "passive"))
      (node (ref "TP31") (pin "P$1") (pinfunction "1_P$1") (pintype "bidirectional"))
      (node (ref "U7") (pin "D3") (pinfunction "TRSTN_D3") (pintype "bidirectional"))
    )
    (net (code "112") (name "Net-(TP32-1)") (class "Default")
      (node (ref "TP32") (pin "P$1") (pinfunction "1_P$1") (pintype "bidirectional"))
      (node (ref "U7") (pin "A3") (pinfunction "MCASP0_ACLKR_A3") (pintype "bidirectional"))
    )
    (net (code "113") (name "Net-(TP35-1)") (class "Default")
      (node (ref "TP35") (pin "P$1") (pinfunction "1_P$1") (pintype "bidirectional"))
      (node (ref "U11") (pin "5") (pinfunction "SHDN_5") (pintype "input"))
    )
    (net (code "114") (name "Net-(TP38-1)") (class "Default")
      (node (ref "TP38") (pin "P$1") (pinfunction "1_P$1") (pintype "bidirectional"))
      (node (ref "U7") (pin "B8") (pinfunction "AIN1_B8") (pintype "bidirectional"))
    )
    (net (code "115") (name "Net-(TP39-1)") (class "Default")
      (node (ref "TP39") (pin "P$1") (pinfunction "1_P$1") (pintype "bidirectional"))
      (node (ref "U7") (pin "A8") (pinfunction "AIN0_A8") (pintype "bidirectional"))
    )
    (net (code "116") (name "Net-(TP40-1)") (class "Default")
      (node (ref "TP40") (pin "P$1") (pinfunction "1_P$1") (pintype "bidirectional"))
      (node (ref "U11") (pin "8") (pinfunction "S_8") (pintype "input"))
    )
    (net (code "117") (name "Net-(TP69-1)") (class "Default")
      (node (ref "TP69") (pin "P$1") (pinfunction "1_P$1") (pintype "bidirectional"))
      (node (ref "U17") (pin "7") (pinfunction "~{HOLD}_7") (pintype "input"))
    )
    (net (code "118") (name "Net-(TP100-1)") (class "Default")
      (node (ref "TP100") (pin "P$1") (pinfunction "1_P$1") (pintype "bidirectional"))
      (node (ref "U7") (pin "T12") (pinfunction "GPMC_A0_T12") (pintype "bidirectional"))
    )
    (net (code "119") (name "Net-(TP101-1)") (class "Default")
      (node (ref "TP101") (pin "P$1") (pinfunction "1_P$1") (pintype "bidirectional"))
      (node (ref "U7") (pin "T13") (pinfunction "GPMC_A3_T13") (pintype "bidirectional"))
    )
    (net (code "120") (name "Net-(TP102-1)") (class "Default")
      (node (ref "TP102") (pin "P$1") (pinfunction "1_P$1") (pintype "bidirectional"))
      (node (ref "U7") (pin "T11") (pinfunction "PMIC_PB_IN_T11") (pintype "bidirectional"))
    )
    (net (code "121") (name "Net-(TP103-1)") (class "Default")
      (node (ref "TP103") (pin "P$1") (pinfunction "1_P$1") (pintype "bidirectional"))
      (node (ref "U7") (pin "T16") (pinfunction "GPMC_A11_T16") (pintype "bidirectional"))
    )
    (net (code "122") (name "Net-(TP104-1)") (class "Default")
      (node (ref "TP104") (pin "P$1") (pinfunction "1_P$1") (pintype "bidirectional"))
      (node (ref "U7") (pin "T4") (pinfunction "GPMC_AD8_T4") (pintype "bidirectional"))
    )
    (net (code "123") (name "Net-(TP105-1)") (class "Default")
      (node (ref "TP105") (pin "P$1") (pinfunction "1_P$1") (pintype "bidirectional"))
      (node (ref "U7") (pin "T5") (pinfunction "GPMC_AD11_T5") (pintype "bidirectional"))
    )
    (net (code "124") (name "Net-(TP106-1)") (class "Default")
      (node (ref "TP106") (pin "P$1") (pinfunction "1_P$1") (pintype "bidirectional"))
      (node (ref "U7") (pin "T7") (pinfunction "GPMC_CLK_T7") (pintype "bidirectional"))
    )
    (net (code "125") (name "Net-(TP107-1)") (class "Default")
      (node (ref "TP107") (pin "P$1") (pinfunction "1_P$1") (pintype "bidirectional"))
      (node (ref "U7") (pin "R7") (pinfunction "GPMC_CSN3_R7") (pintype "bidirectional"))
    )
    (net (code "126") (name "Net-(TP108-1)") (class "Default")
      (node (ref "TP108") (pin "P$1") (pinfunction "1_P$1") (pintype "bidirectional"))
      (node (ref "U7") (pin "T15") (pinfunction "GPMC_A9_T15") (pintype "bidirectional"))
    )
    (net (code "127") (name "Net-(TP111-1)") (class "Default")
      (node (ref "TP111") (pin "P$1") (pinfunction "1_P$1") (pintype "bidirectional"))
      (node (ref "U7") (pin "R16") (pinfunction "GPMC_WPN_R16") (pintype "bidirectional"))
    )
    (net (code "128") (name "Net-(TP114-1)") (class "Default")
      (node (ref "TP114") (pin "P$1") (pinfunction "1_P$1") (pintype "bidirectional"))
      (node (ref "U7") (pin "P15") (pinfunction "GPMC_WAIT0_P15") (pintype "bidirectional"))
    )
    (net (code "129") (name "Net-(TP115-1)") (class "Default")
      (node (ref "TP115") (pin "P$1") (pinfunction "1_P$1") (pintype "bidirectional"))
      (node (ref "U7") (pin "R5") (pinfunction "GPMC_AD10_R5") (pintype "bidirectional"))
    )
    (net (code "130") (name "Net-(TP117-1)") (class "Default")
      (node (ref "TP117") (pin "P$1") (pinfunction "1_P$1") (pintype "bidirectional"))
      (node (ref "U7") (pin "R15") (pinfunction "GPMC_A10_R15") (pintype "bidirectional"))
    )
    (net (code "131") (name "Net-(TP118-1)") (class "Default")
      (node (ref "TP118") (pin "P$1") (pinfunction "1_P$1") (pintype "bidirectional"))
      (node (ref "U7") (pin "R12") (pinfunction "GPMC_A1_R12") (pintype "bidirectional"))
    )
    (net (code "132") (name "Net-(TP120-1)") (class "Default")
      (node (ref "TP120") (pin "P$1") (pinfunction "1_P$1") (pintype "bidirectional"))
      (node (ref "U7") (pin "R6") (pinfunction "GPMC_AD13_R6") (pintype "bidirectional"))
    )
    (net (code "133") (name "Net-(TP121-1)") (class "Default")
      (node (ref "TP121") (pin "P$1") (pinfunction "1_P$1") (pintype "bidirectional"))
      (node (ref "U7") (pin "N10") (pinfunction "PMIC_POWER_EN_N10") (pintype "output"))
      (node (ref "U7") (pin "N11") (pinfunction "PMIC_PWR_EN_N11") (pintype "input"))
    )
    (net (code "134") (name "Net-(TP122-1)") (class "Default")
      (node (ref "TP122") (pin "P$1") (pinfunction "1_P$1") (pintype "bidirectional"))
      (node (ref "U7") (pin "P3") (pinfunction "GPMC_CSN0_P3") (pintype "bidirectional"))
    )
    (net (code "135") (name "Net-(TP123-1)") (class "Default")
      (node (ref "TP123") (pin "P$1") (pinfunction "1_P$1") (pintype "bidirectional"))
      (node (ref "U7") (pin "P5") (pinfunction "GPMC_AD9_P5") (pintype "bidirectional"))
    )
    (net (code "136") (name "Net-(TP124-1)") (class "Default")
      (node (ref "TP124") (pin "P$1") (pinfunction "1_P$1") (pintype "bidirectional"))
      (node (ref "U7") (pin "P6") (pinfunction "GPMC_AD12_P6") (pintype "bidirectional"))
    )
    (net (code "137") (name "Net-(TP125-1)") (class "Default")
      (node (ref "TP125") (pin "P$1") (pinfunction "1_P$1") (pintype "bidirectional"))
      (node (ref "U7") (pin "N14") (pinfunction "GPMC_BEN1_N14") (pintype "bidirectional"))
    )
    (net (code "138") (name "Net-(TP126-1)") (class "Default")
      (node (ref "TP126") (pin "P$1") (pinfunction "1_P$1") (pintype "bidirectional"))
      (node (ref "U7") (pin "P12") (pinfunction "GPMC_A2_P12") (pintype "bidirectional"))
    )
    (net (code "139") (name "Net-(TP127-1)") (class "Default")
      (node (ref "TP127") (pin "P$1") (pinfunction "1_P$1") (pintype "bidirectional"))
      (node (ref "U7") (pin "N2") (pinfunction "GPMC_WEN_N2") (pintype "bidirectional"))
    )
    (net (code "140") (name "Net-(TP128-1)") (class "Default")
      (node (ref "TP128") (pin "P$1") (pinfunction "1_P$1") (pintype "bidirectional"))
      (node (ref "U7") (pin "N1") (pinfunction "GPMC_OEN_REN_N1") (pintype "bidirectional"))
    )
    (net (code "141") (name "Net-(TP129-1)") (class "Default")
      (node (ref "TP129") (pin "P$1") (pinfunction "1_P$1") (pintype "bidirectional"))
      (node (ref "U7") (pin "N6") (pinfunction "PMIC_TS_N6") (pintype "bidirectional"))
    )
    (net (code "142") (name "Net-(TP130-1)") (class "Default")
      (node (ref "TP130") (pin "P$1") (pinfunction "1_P$1") (pintype "bidirectional"))
      (node (ref "TP4") (pin "P$1") (pinfunction "1_P$1") (pintype "bidirectional"))
      (node (ref "U7") (pin "N7") (pinfunction "PMIC_BAT_SENSE_N7") (pintype "bidirectional"))
      (node (ref "U7") (pin "P8") (pinfunction "VIN_BAT_P8") (pintype "power_in"))
      (node (ref "U7") (pin "R8") (pinfunction "VIN_BAT_R8") (pintype "power_in"))
      (node (ref "U7") (pin "T8") (pinfunction "VIN_BAT_T8") (pintype "power_in"))
    )
    (net (code "143") (name "Net-(TP131-1)") (class "Default")
      (node (ref "TP131") (pin "P$1") (pinfunction "1_P$1") (pintype "bidirectional"))
      (node (ref "U7") (pin "N3") (pinfunction "GPMC_BEN0_CLE_N3") (pintype "bidirectional"))
    )
    (net (code "144") (name "Net-(TP132-1)") (class "Default")
      (node (ref "TP132") (pin "P$1") (pinfunction "1_P$1") (pintype "bidirectional"))
      (node (ref "U7") (pin "N4") (pinfunction "PMIC_LDO_PGOOD_N4") (pintype "output"))
      (node (ref "U7") (pin "N5") (pinfunction "RTC_PWRONRSTN_N5") (pintype "bidirectional"))
    )
    (net (code "145") (name "Net-(TP133-1)") (class "Default")
      (node (ref "TP133") (pin "P$1") (pinfunction "1_P$1") (pintype "bidirectional"))
      (node (ref "U7") (pin "N13") (pinfunction "PMIC_MUX_IN_N13") (pintype "bidirectional"))
    )
    (net (code "146") (name "Net-(TP134-1)") (class "Default")
      (node (ref "TP134") (pin "P$1") (pinfunction "1_P$1") (pintype "bidirectional"))
      (node (ref "U7") (pin "M1") (pinfunction "GPMC_ADVN_ALE_M1") (pintype "bidirectional"))
    )
    (net (code "147") (name "Net-(TP135-1)") (class "Default")
      (node (ref "TP135") (pin "P$1") (pinfunction "1_P$1") (pintype "bidirectional"))
      (node (ref "U7") (pin "G16") (pinfunction "MII1_TXD2_G16") (pintype "bidirectional"))
    )
    (net (code "148") (name "Net-(TP136-1)") (class "Default")
      (node (ref "TP136") (pin "P$1") (pinfunction "1_P$1") (pintype "bidirectional"))
      (node (ref "U7") (pin "M13") (pinfunction "PMIC_NRESET_M13") (pintype "bidirectional"))
    )
    (net (code "149") (name "Net-(TP137-1)") (class "Default")
      (node (ref "TP137") (pin "P$1") (pinfunction "1_P$1") (pintype "bidirectional"))
      (node (ref "U7") (pin "H15") (pinfunction "MII1_TXD0_H15") (pintype "bidirectional"))
    )
    (net (code "150") (name "Net-(TP138-1)") (class "Default")
      (node (ref "TP138") (pin "P$1") (pinfunction "1_P$1") (pintype "bidirectional"))
      (node (ref "U7") (pin "K14") (pinfunction "USB0_ID_K14") (pintype "bidirectional"))
    )
    (net (code "151") (name "Net-(TP139-1)") (class "Default")
      (node (ref "TP139") (pin "P$1") (pinfunction "1_P$1") (pintype "bidirectional"))
      (node (ref "U7") (pin "J15") (pinfunction "USB0_DRVVBUS_J15") (pintype "bidirectional"))
    )
    (net (code "152") (name "Net-(TP140-1)") (class "Default")
      (node (ref "TP140") (pin "P$1") (pinfunction "1_P$1") (pintype "bidirectional"))
      (node (ref "U7") (pin "L4") (pinfunction "PMIC_NWAKEUP_L4") (pintype "output"))
      (node (ref "U7") (pin "M4") (pinfunction "EXT_WAKEUP_M4") (pintype "bidirectional"))
    )
    (net (code "153") (name "Net-(TP141-1)") (class "Default")
      (node (ref "TP141") (pin "P$1") (pinfunction "1_P$1") (pintype "bidirectional"))
      (node (ref "U7") (pin "K13") (pinfunction "USB0_CE_K13") (pintype "bidirectional"))
    )
    (net (code "154") (name "Net-(TP144-1)") (class "Default")
      (node (ref "TP144") (pin "P$1") (pinfunction "1_P$1") (pintype "bidirectional"))
      (node (ref "U7") (pin "L13") (pinfunction "USB1_CE_L13") (pintype "bidirectional"))
    )
    (net (code "155") (name "Net-(TP145-1)") (class "Default")
      (node (ref "TP145") (pin "P$1") (pinfunction "1_P$1") (pintype "bidirectional"))
      (node (ref "U7") (pin "K4") (pinfunction "NC_K4") (pintype "bidirectional"))
    )
    (net (code "156") (name "Net-(TP149-1)") (class "Default")
      (node (ref "TP149") (pin "P$1") (pinfunction "1_P$1") (pintype "bidirectional"))
      (node (ref "U7") (pin "H14") (pinfunction "MII1_TXD1_H14") (pintype "bidirectional"))
    )
    (net (code "157") (name "Net-(TP150-1)") (class "Default")
      (node (ref "TP150") (pin "P$1") (pinfunction "1_P$1") (pintype "bidirectional"))
      (node (ref "U7") (pin "J6") (pinfunction "NC_J6") (pintype "bidirectional"))
    )
    (net (code "158") (name "Net-(TP152-1)") (class "Default")
      (node (ref "TP152") (pin "P$1") (pinfunction "1_P$1") (pintype "bidirectional"))
      (node (ref "U7") (pin "F2") (pinfunction "LCD_HSYNC_F2") (pintype "bidirectional"))
    )
    (net (code "159") (name "Net-(TP153-1)") (class "Default")
      (node (ref "TP153") (pin "P$1") (pinfunction "1_P$1") (pintype "bidirectional"))
      (node (ref "U7") (pin "F3") (pinfunction "LCD_VSYNC_F3") (pintype "bidirectional"))
    )
    (net (code "160") (name "Net-(TP154-1)") (class "Default")
      (node (ref "TP154") (pin "P$1") (pinfunction "1_P$1") (pintype "bidirectional"))
      (node (ref "U7") (pin "G4") (pinfunction "VDD_CORE_G4") (pintype "bidirectional"))
    )
    (net (code "161") (name "Net-(TP156-1)") (class "Default")
      (node (ref "TP156") (pin "P$1") (pinfunction "1_P$1") (pintype "bidirectional"))
      (node (ref "U7") (pin "F4") (pinfunction "VDDS_DDR_F4") (pintype "bidirectional"))
    )
    (net (code "162") (name "Net-(TP157-1)") (class "Default")
      (node (ref "TP157") (pin "P$1") (pinfunction "1_P$1") (pintype "bidirectional"))
      (node (ref "U7") (pin "H6") (pinfunction "VPP_H6") (pintype "bidirectional"))
    )
    (net (code "163") (name "Net-(TP158-1)") (class "Default")
      (node (ref "TP158") (pin "P$1") (pinfunction "1_P$1") (pintype "bidirectional"))
      (node (ref "U7") (pin "E13") (pinfunction "MDIO_E13") (pintype "bidirectional"))
    )
    (net (code "164") (name "Net-(TP159-1)") (class "Default")
      (node (ref "TP159") (pin "P$1") (pinfunction "1_P$1") (pintype "bidirectional"))
      (node (ref "U7") (pin "E1") (pinfunction "LCD_AC_BIAS_EN_E1") (pintype "bidirectional"))
    )
    (net (code "165") (name "Net-(TP160-1)") (class "Default")
      (node (ref "TP160") (pin "P$1") (pinfunction "1_P$1") (pintype "bidirectional"))
      (node (ref "U7") (pin "F13") (pinfunction "VDD_MPU_F13") (pintype "bidirectional"))
    )
    (net (code "166") (name "Net-(TP161-1)") (class "Default")
      (node (ref "TP161") (pin "P$1") (pinfunction "1_P$1") (pintype "bidirectional"))
      (node (ref "U7") (pin "F11") (pinfunction "SYS_VDD2_3P3V_F11") (pintype "power_in"))
      (node (ref "U7") (pin "G11") (pinfunction "SYS_VDD2_3P3V_G11") (pintype "power_in"))
    )
    (net (code "167") (name "Net-(TP162-1)") (class "Default")
      (node (ref "TP162") (pin "P$1") (pinfunction "1_P$1") (pintype "bidirectional"))
      (node (ref "U7") (pin "F1") (pinfunction "LCD_PCLK_F1") (pintype "bidirectional"))
    )
    (net (code "168") (name "Net-(TP163-1)") (class "Default")
      (node (ref "TP163") (pin "P$1") (pinfunction "1_P$1") (pintype "bidirectional"))
      (node (ref "U7") (pin "F10") (pinfunction "SYS_VDD_1P8V_F10") (pintype "power_in"))
      (node (ref "U7") (pin "G10") (pinfunction "SYS_VDD_1P8V_G10") (pintype "power_in"))
      (node (ref "U7") (pin "H10") (pinfunction "SYS_VDD_1P8V_H10") (pintype "power_in"))
      (node (ref "U7") (pin "H11") (pinfunction "SYS_VDD_1P8V_H11") (pintype "power_in"))
      (node (ref "U7") (pin "J10") (pinfunction "SYS_VDD_1P8V_J10") (pintype "power_in"))
      (node (ref "U7") (pin "J11") (pinfunction "SYS_VDD_1P8V_J11") (pintype "power_in"))
      (node (ref "U7") (pin "K10") (pinfunction "SYS_VDD_1P8V_K10") (pintype "power_in"))
      (node (ref "U7") (pin "L10") (pinfunction "SYS_VDD_1P8V_L10") (pintype "power_in"))
    )
    (net (code "169") (name "Net-(TP166-1)") (class "Default")
      (node (ref "TP166") (pin "P$1") (pinfunction "1_P$1") (pintype "bidirectional"))
      (node (ref "U7") (pin "G13") (pinfunction "VDDS_PLL_G13") (pintype "bidirectional"))
    )
    (net (code "170") (name "Net-(TP167-1)") (class "Default")
      (node (ref "TP167") (pin "P$1") (pinfunction "1_P$1") (pintype "bidirectional"))
      (node (ref "U7") (pin "D4") (pinfunction "EXTINTN_D4") (pintype "bidirectional"))
      (node (ref "U7") (pin "E4") (pinfunction "PMIC_NINT_E4") (pintype "output"))
    )
    (net (code "171") (name "Net-(TP168-1)") (class "Default")
      (node (ref "TP168") (pin "P$1") (pinfunction "1_P$1") (pintype "bidirectional"))
      (node (ref "U7") (pin "D6") (pinfunction "PMIC_MUX_OUT_D6") (pintype "bidirectional"))
    )
    (net (code "172") (name "Net-(TP169-1)") (class "Default")
      (node (ref "TP169") (pin "P$1") (pinfunction "1_P$1") (pintype "bidirectional"))
      (node (ref "U7") (pin "C8") (pinfunction "AIN5_C8") (pintype "bidirectional"))
    )
    (net (code "173") (name "Net-(TP170-1)") (class "Default")
      (node (ref "TP170") (pin "P$1") (pinfunction "1_P$1") (pintype "bidirectional"))
      (node (ref "U7") (pin "D7") (pinfunction "AIN7_D7") (pintype "bidirectional"))
    )
    (net (code "174") (name "Net-(TP171-1)") (class "Default")
      (node (ref "TP171") (pin "P$1") (pinfunction "1_P$1") (pintype "bidirectional"))
      (node (ref "U7") (pin "A9") (pinfunction "AGND_ADC_A9") (pintype "bidirectional"))
      (node (ref "U7") (pin "B7") (pinfunction "VREFP_B7") (pintype "bidirectional"))
      (node (ref "U7") (pin "B9") (pinfunction "VREFN_B9") (pintype "bidirectional"))
    )
    (net (code "175") (name "Net-(TP172-1)") (class "Default")
      (node (ref "TP172") (pin "P$1") (pinfunction "1_P$1") (pintype "bidirectional"))
      (node (ref "U7") (pin "D12") (pinfunction "NC_D12") (pintype "bidirectional"))
    )
    (net (code "176") (name "Net-(TP173-1)") (class "Default")
      (node (ref "TP173") (pin "P$1") (pinfunction "1_P$1") (pintype "bidirectional"))
      (node (ref "U7") (pin "D5") (pinfunction "CAP_VDD_RTC_D5") (pintype "bidirectional"))
    )
    (net (code "177") (name "Net-(TP174-1)") (class "Default")
      (node (ref "TP174") (pin "P$1") (pinfunction "1_P$1") (pintype "bidirectional"))
      (node (ref "U7") (pin "D13") (pinfunction "MDC_D13") (pintype "bidirectional"))
    )
    (net (code "178") (name "Net-(TP175-1)") (class "Default")
      (node (ref "TP175") (pin "P$1") (pinfunction "1_P$1") (pintype "bidirectional"))
      (node (ref "U7") (pin "C6") (pinfunction "AIN3_C6") (pintype "bidirectional"))
    )
    (net (code "179") (name "Net-(TP176-1)") (class "Default")
      (node (ref "TP176") (pin "P$1") (pinfunction "1_P$1") (pintype "bidirectional"))
      (node (ref "U7") (pin "C7") (pinfunction "AIN4_C7") (pintype "bidirectional"))
    )
    (net (code "180") (name "Net-(TP177-1)") (class "Default")
      (node (ref "TP177") (pin "P$1") (pinfunction "1_P$1") (pintype "bidirectional"))
      (node (ref "U7") (pin "C12") (pinfunction "UART0_CTSN_C12") (pintype "bidirectional"))
    )
    (net (code "181") (name "Net-(TP178-1)") (class "Default")
      (node (ref "TP178") (pin "P$1") (pinfunction "1_P$1") (pintype "bidirectional"))
      (node (ref "U7") (pin "C13") (pinfunction "UART0_RTSN_C13") (pintype "bidirectional"))
    )
    (net (code "182") (name "Net-(TP179-1)") (class "Default")
      (node (ref "TP179") (pin "P$1") (pinfunction "1_P$1") (pintype "bidirectional"))
      (node (ref "U7") (pin "C9") (pinfunction "AIN6_C9") (pintype "bidirectional"))
    )
    (net (code "183") (name "Net-(TP180-1)") (class "Default")
      (node (ref "TP180") (pin "P$1") (pinfunction "1_P$1") (pintype "bidirectional"))
      (node (ref "U7") (pin "C5") (pinfunction "ECAP0_IN_PWM0_OUT_C5") (pintype "bidirectional"))
    )
    (net (code "184") (name "Net-(TP181-1)") (class "Default")
      (node (ref "TP181") (pin "P$1") (pinfunction "1_P$1") (pintype "bidirectional"))
      (node (ref "U7") (pin "B6") (pinfunction "AIN2_B6") (pintype "bidirectional"))
    )
    (net (code "185") (name "Net-(TP182-1)") (class "Default")
      (node (ref "TP182") (pin "P$1") (pinfunction "1_P$1") (pintype "bidirectional"))
      (node (ref "U7") (pin "A7") (pinfunction "SYS_ADC_1P8V_A7") (pintype "bidirectional"))
    )
    (net (code "186") (name "Net-(U2-EN)") (class "Default")
      (node (ref "R6") (pin "2") (pinfunction "2_2") (pintype "passive"))
      (node (ref "U2") (pin "4") (pinfunction "EN_4") (pintype "input"))
      (node (ref "U7") (pin "M14") (pinfunction "USB1_DRVVBUS_M14") (pintype "bidirectional"))
    )
    (net (code "187") (name "Net-(U2-~{FLT})") (class "Default")
      (node (ref "R7") (pin "1") (pinfunction "1_1") (pintype "passive"))
      (node (ref "U2") (pin "3") (pinfunction "~{FLT}_3") (pintype "output"))
    )
    (net (code "188") (name "Net-(U3-VDDI)") (class "Default")
      (node (ref "C10") (pin "1") (pinfunction "1_1") (pintype "passive"))
      (node (ref "C12") (pin "1") (pinfunction "1_1") (pintype "passive"))
      (node (ref "U3") (pin "C2") (pinfunction "VDDI_C2") (pintype "power_in"))
    )
    (net (code "189") (name "Net-(U5-VEN)") (class "Default")
      (node (ref "R77") (pin "2") (pinfunction "2_2") (pintype "passive"))
      (node (ref "U5") (pin "2") (pinfunction "VEN_2") (pintype "input"))
    )
    (net (code "190") (name "Net-(U6-OUT)") (class "Default")
      (node (ref "C46") (pin "1") (pinfunction "1_1") (pintype "passive"))
      (node (ref "U6") (pin "3") (pinfunction "OUT_3") (pintype "bidirectional"))
    )
    (net (code "191") (name "Net-(U7A-EEPROM_WP)") (class "Default")
      (node (ref "R75") (pin "2") (pinfunction "2_2") (pintype "passive"))
      (node (ref "U7") (pin "M2") (pinfunction "EEPROM_WP_M2") (pintype "bidirectional"))
    )
    (net (code "192") (name "Net-(U7A-I2C0_SCL)") (class "Default")
      (node (ref "R73") (pin "2") (pinfunction "2_2") (pintype "passive"))
      (node (ref "U7") (pin "C10") (pinfunction "I2C0_SCL_C10") (pintype "bidirectional"))
      (node (ref "U7") (pin "D10") (pinfunction "PMIC_SCL_D10") (pintype "bidirectional"))
    )
    (net (code "193") (name "Net-(U7A-I2C0_SDA)") (class "Default")
      (node (ref "R74") (pin "2") (pinfunction "2_2") (pintype "passive"))
      (node (ref "U7") (pin "C11") (pinfunction "I2C0_SDA_C11") (pintype "bidirectional"))
      (node (ref "U7") (pin "D11") (pinfunction "PMIC_SDA_D11") (pintype "bidirectional"))
    )
    (net (code "194") (name "Net-(U7A-RTC_KALDO_ENN)") (class "Default")
      (node (ref "R15") (pin "2") (pinfunction "2_2") (pintype "passive"))
      (node (ref "U7") (pin "M16") (pinfunction "RTC_KALDO_ENN_M16") (pintype "bidirectional"))
    )
    (net (code "195") (name "Net-(U7B-EMU0)") (class "Default")
      (node (ref "R22") (pin "1") (pinfunction "1_1") (pintype "passive"))
      (node (ref "U7") (pin "E2") (pinfunction "EMU0_E2") (pintype "bidirectional"))
    )
    (net (code "196") (name "Net-(U7B-EMU1)") (class "Default")
      (node (ref "R20") (pin "1") (pinfunction "1_1") (pintype "passive"))
      (node (ref "U7") (pin "E3") (pinfunction "EMU1_E3") (pintype "bidirectional"))
    )
    (net (code "197") (name "Net-(U7B-OSC1_GND)") (class "Default")
      (node (ref "C29") (pin "2") (pinfunction "2_2") (pintype "passive"))
      (node (ref "C30") (pin "2") (pinfunction "2_2") (pintype "passive"))
      (node (ref "U7") (pin "B5") (pinfunction "OSC1_GND_B5") (pintype "bidirectional"))
    )
    (net (code "198") (name "Net-(U7B-OSC1_IN)") (class "Default")
      (node (ref "C30") (pin "1") (pinfunction "1_1") (pintype "passive"))
      (node (ref "R27") (pin "2") (pinfunction "2_2") (pintype "passive"))
      (node (ref "U7") (pin "A6") (pinfunction "OSC1_IN_A6") (pintype "bidirectional"))
      (node (ref "Y2") (pin "P$2") (pinfunction "P$2_P$2") (pintype "passive"))
    )
    (net (code "199") (name "Net-(U7B-OSC1_OUT)") (class "Default")
      (node (ref "C29") (pin "1") (pinfunction "1_1") (pintype "passive"))
      (node (ref "R27") (pin "1") (pinfunction "1_1") (pintype "passive"))
      (node (ref "U7") (pin "A5") (pinfunction "OSC1_OUT_A5") (pintype "bidirectional"))
      (node (ref "Y2") (pin "P$1") (pinfunction "P$1_P$1") (pintype "passive"))
    )
    (net (code "200") (name "Net-(U7B-USB1_ID)") (class "Default")
      (node (ref "JP100") (pin "1") (pinfunction "1_1") (pintype "passive"))
      (node (ref "U7") (pin "L14") (pinfunction "USB1_ID_L14") (pintype "bidirectional"))
    )
    (net (code "201") (name "Net-(U7C-GPMC_A5)") (class "Default")
      (node (ref "R2") (pin "1") (pinfunction "1_1") (pintype "passive"))
      (node (ref "U7") (pin "P13") (pinfunction "GPMC_A5_P13") (pintype "bidirectional"))
    )
    (net (code "202") (name "Net-(U7C-GPMC_A6)") (class "Default")
      (node (ref "R3") (pin "1") (pinfunction "1_1") (pintype "passive"))
      (node (ref "U7") (pin "T14") (pinfunction "GPMC_A6_T14") (pintype "bidirectional"))
    )
    (net (code "203") (name "Net-(U7C-GPMC_A7)") (class "Default")
      (node (ref "R4") (pin "1") (pinfunction "1_1") (pintype "passive"))
      (node (ref "U7") (pin "R14") (pinfunction "GPMC_A7_R14") (pintype "bidirectional"))
    )
    (net (code "204") (name "Net-(U7C-GPMC_A8)") (class "Default")
      (node (ref "R5") (pin "1") (pinfunction "1_1") (pintype "passive"))
      (node (ref "U7") (pin "P14") (pinfunction "GPMC_A8_P14") (pintype "bidirectional"))
    )
    (net (code "205") (name "Net-(U7D-LCD_DATA0)") (class "Default")
      (node (ref "JP105") (pin "2") (pinfunction "2_2") (pintype "passive"))
      (node (ref "U7") (pin "G3") (pinfunction "LCD_DATA0_G3") (pintype "bidirectional"))
    )
    (net (code "206") (name "Net-(U7D-LCD_DATA1)") (class "Default")
      (node (ref "JP106") (pin "2") (pinfunction "2_2") (pintype "passive"))
      (node (ref "U7") (pin "G2") (pinfunction "LCD_DATA1_G2") (pintype "bidirectional"))
    )
    (net (code "207") (name "Net-(U7D-LCD_DATA2)") (class "Default")
      (node (ref "J3") (pin "2") (pinfunction "2_2") (pintype "passive"))
      (node (ref "JP107") (pin "2") (pinfunction "2_2") (pintype "passive"))
      (node (ref "U7") (pin "G1") (pinfunction "LCD_DATA2_G1") (pintype "bidirectional"))
    )
    (net (code "208") (name "Net-(U7D-LCD_DATA3)") (class "Default")
      (node (ref "JP108") (pin "2") (pinfunction "2_2") (pintype "passive"))
      (node (ref "U7") (pin "H3") (pinfunction "LCD_DATA3_H3") (pintype "bidirectional"))
    )
    (net (code "209") (name "Net-(U7D-LCD_DATA4)") (class "Default")
      (node (ref "JP109") (pin "2") (pinfunction "2_2") (pintype "passive"))
      (node (ref "U7") (pin "H2") (pinfunction "LCD_DATA4_H2") (pintype "bidirectional"))
    )
    (net (code "210") (name "Net-(U8-BP)") (class "Default")
      (node (ref "C60") (pin "2") (pinfunction "2_2") (pintype "passive"))
      (node (ref "U8") (pin "4") (pinfunction "BP_4") (pintype "input"))
    )
    (net (code "211") (name "Net-(U9-BP)") (class "Default")
      (node (ref "C50") (pin "2") (pinfunction "2_2") (pintype "passive"))
      (node (ref "U9") (pin "4") (pinfunction "BP_4") (pintype "input"))
    )
    (net (code "212") (name "Net-(U10-ANODE)") (class "Default")
      (node (ref "JP104") (pin "2") (pinfunction "2_2") (pintype "passive"))
      (node (ref "Q1") (pin "C") (pinfunction "C_C") (pintype "passive"))
      (node (ref "R31") (pin "1") (pinfunction "1_1") (pintype "passive"))
      (node (ref "U10") (pin "3") (pinfunction "ANODE_3") (pintype "bidirectional"))
    )
    (net (code "213") (name "Net-(U10-CATHODE)") (class "Default")
      (node (ref "Q1") (pin "B") (pinfunction "B_B") (pintype "passive"))
      (node (ref "R23") (pin "1") (pinfunction "1_1") (pintype "passive"))
      (node (ref "U10") (pin "2") (pinfunction "CATHODE_2") (pintype "bidirectional"))
    )
    (net (code "214") (name "Net-(U10-REF)") (class "Default")
      (node (ref "R28") (pin "1") (pinfunction "1_1") (pintype "passive"))
      (node (ref "R31") (pin "2") (pinfunction "2_2") (pintype "passive"))
      (node (ref "U10") (pin "1") (pinfunction "REF_1") (pintype "bidirectional"))
    )
    (net (code "215") (name "Net-(U11-RXD)") (class "Default")
      (node (ref "U11") (pin "4") (pinfunction "RXD_4") (pintype "output"))
      (node (ref "U7") (pin "B11") (pinfunction "UART1_TXD_B11") (pintype "bidirectional"))
    )
    (net (code "216") (name "Net-(U11-TXD)") (class "Default")
      (node (ref "U11") (pin "1") (pinfunction "TXD_1") (pintype "input"))
      (node (ref "U7") (pin "A11") (pinfunction "UART1_RXD_A11") (pintype "bidirectional"))
    )
    (net (code "217") (name "Net-(U12-INP)") (class "Default")
      (node (ref "C32") (pin "1") (pinfunction "1_1") (pintype "passive"))
      (node (ref "R36") (pin "1") (pinfunction "1_1") (pintype "passive"))
      (node (ref "R37") (pin "1") (pinfunction "1_1") (pintype "passive"))
      (node (ref "U12") (pin "1") (pinfunction "INP_1") (pintype "input"))
    )
    (net (code "218") (name "Net-(U12-OUT)") (class "Default")
      (node (ref "R35") (pin "1") (pinfunction "1_1") (pintype "passive"))
      (node (ref "TP44") (pin "1") (pinfunction "1_1") (pintype "passive"))
      (node (ref "U12") (pin "4") (pinfunction "OUT_4") (pintype "output"))
    )
    (net (code "219") (name "Net-(U13-INP)") (class "Default")
      (node (ref "C35") (pin "1") (pinfunction "1_1") (pintype "passive"))
      (node (ref "R44") (pin "1") (pinfunction "1_1") (pintype "passive"))
      (node (ref "R45") (pin "1") (pinfunction "1_1") (pintype "passive"))
      (node (ref "U13") (pin "1") (pinfunction "INP_1") (pintype "input"))
    )
    (net (code "220") (name "Net-(U13-OUT)") (class "Default")
      (node (ref "R43") (pin "1") (pinfunction "1_1") (pintype "passive"))
      (node (ref "TP43") (pin "1") (pinfunction "1_1") (pintype "passive"))
      (node (ref "U13") (pin "4") (pinfunction "OUT_4") (pintype "output"))
    )
    (net (code "221") (name "Net-(U14-CIN1+)") (class "Default")
      (node (ref "R50") (pin "1") (pinfunction "1_1") (pintype "passive"))
      (node (ref "R51") (pin "2") (pinfunction "2_2") (pintype "passive"))
      (node (ref "TP57") (pin "1") (pinfunction "1_1") (pintype "passive"))
      (node (ref "U14") (pin "10") (pinfunction "CIN1+_10") (pintype "input"))
    )
    (net (code "222") (name "Net-(U14-CIN1-)") (class "Default")
      (node (ref "R42") (pin "2") (pinfunction "2_2") (pintype "passive"))
      (node (ref "R47") (pin "1") (pinfunction "1_1") (pintype "passive"))
      (node (ref "TP47") (pin "1") (pinfunction "1_1") (pintype "passive"))
      (node (ref "U14") (pin "11") (pinfunction "CIN1-_11") (pintype "input"))
    )
    (net (code "223") (name "Net-(U14-CIN2+)") (class "Default")
      (node (ref "R47") (pin "2") (pinfunction "2_2") (pintype "passive"))
      (node (ref "U14") (pin "12") (pinfunction "REF_12") (pintype "output"))
      (node (ref "U14") (pin "8") (pinfunction "CIN2+_8") (pintype "input"))
    )
    (net (code "224") (name "Net-(U14-INHIBIT)") (class "Default")
      (node (ref "R38") (pin "1") (pinfunction "1_1") (pintype "passive"))
      (node (ref "U14") (pin "5") (pinfunction "INHIBIT_5") (pintype "input"))
    )
    (net (code "225") (name "Net-(U14-IOUT)") (class "Default")
      (node (ref "R50") (pin "2") (pinfunction "2_2") (pintype "passive"))
      (node (ref "U14") (pin "14") (pinfunction "IOUT_14") (pintype "output"))
    )
    (net (code "226") (name "Net-(U14-RS+)") (class "Default")
      (node (ref "C62") (pin "1") (pinfunction "1_1") (pintype "passive"))
      (node (ref "Q6") (pin "1") (pinfunction "D_1") (pintype "passive"))
      (node (ref "Q6") (pin "2") (pinfunction "D_2") (pintype "passive"))
      (node (ref "Q6") (pin "5") (pinfunction "D_5") (pintype "passive"))
      (node (ref "Q6") (pin "6") (pinfunction "D_6") (pintype "passive"))
      (node (ref "R63") (pin "1") (pinfunction "1_1") (pintype "passive"))
      (node (ref "U14") (pin "16") (pinfunction "RS+_16") (pintype "passive"))
    )
    (net (code "227") (name "Net-(U15-PG)") (class "Default")
      (node (ref "TP48") (pin "1") (pinfunction "1_1") (pintype "passive"))
      (node (ref "U15") (pin "13") (pinfunction "PG_13") (pintype "open_collector"))
    )
    (net (code "228") (name "Net-(U15-SYNC)") (class "Default")
      (node (ref "R34") (pin "1") (pinfunction "1_1") (pintype "passive"))
      (node (ref "R40") (pin "2") (pinfunction "2_2") (pintype "passive"))
      (node (ref "TP46") (pin "1") (pinfunction "1_1") (pintype "passive"))
      (node (ref "U15") (pin "5") (pinfunction "SYNC_5") (pintype "input"))
    )
    (net (code "229") (name "Net-(U16-IO6)") (class "Default")
      (node (ref "TP53") (pin "1") (pinfunction "1_1") (pintype "passive"))
      (node (ref "U16") (pin "11") (pinfunction "IO6_11") (pintype "bidirectional"))
    )
    (net (code "230") (name "Net-(U16-IO7)") (class "Default")
      (node (ref "TP56") (pin "1") (pinfunction "1_1") (pintype "passive"))
      (node (ref "U16") (pin "12") (pinfunction "IO7_12") (pintype "bidirectional"))
    )
    (net (code "231") (name "Net-(U16-~{RESET})") (class "Default")
      (node (ref "R72") (pin "1") (pinfunction "1_1") (pintype "passive"))
      (node (ref "U16") (pin "13") (pinfunction "~{RESET}_13") (pintype "input"))
    )
    (net (code "232") (name "Net-(U17-MISO)") (class "Default")
      (node (ref "U17") (pin "2") (pinfunction "MISO_2") (pintype "output"))
      (node (ref "U7") (pin "B13") (pinfunction "SPI0_D0_B13") (pintype "bidirectional"))
    )
    (net (code "233") (name "Net-(U17-MOSI)") (class "Default")
      (node (ref "U17") (pin "5") (pinfunction "MOSI_5") (pintype "input"))
      (node (ref "U7") (pin "B14") (pinfunction "SPI0_D1_B14") (pintype "bidirectional"))
    )
    (net (code "234") (name "Net-(U17-SCK)") (class "Default")
      (node (ref "U17") (pin "6") (pinfunction "SCK_6") (pintype "input"))
      (node (ref "U7") (pin "A13") (pinfunction "SPI0_SCLK_A13") (pintype "bidirectional"))
    )
    (net (code "235") (name "Net-(U17-~{CS})") (class "Default")
      (node (ref "U17") (pin "1") (pinfunction "~{CS}_1") (pintype "input"))
      (node (ref "U7") (pin "A14") (pinfunction "SPI0_CS0_A14") (pintype "bidirectional"))
    )
    (net (code "236") (name "Net-(U17-~{WP})") (class "Default")
      (node (ref "R59") (pin "1") (pinfunction "1_1") (pintype "passive"))
      (node (ref "R60") (pin "2") (pinfunction "2_2") (pintype "passive"))
      (node (ref "U17") (pin "3") (pinfunction "~{WP}_3") (pintype "input"))
    )
    (net (code "237") (name "Net-(U19-SUM)") (class "Default")
      (node (ref "U19") (pin "2") (pinfunction "SUM_2") (pintype "passive"))
      (node (ref "U5") (pin "6") (pinfunction "RF_OUT_6") (pintype "output"))
    )
    (net (code "238") (name "Net-(U20-BP)") (class "Default")
      (node (ref "C69") (pin "2") (pinfunction "2_2") (pintype "passive"))
      (node (ref "U20") (pin "4") (pinfunction "BP_4") (pintype "input"))
    )
    (net (code "239") (name "Net-(U21-IN)") (class "Default")
      (node (ref "U21") (pin "1") (pinfunction "IN_1") (pintype "passive"))
      (node (ref "U23") (pin "24") (pinfunction "LNAOUT_HI_24") (pintype "output"))
    )
    (net (code "240") (name "Net-(U21-OUT)") (class "Default")
      (node (ref "U21") (pin "4") (pinfunction "OUT_4") (pintype "passive"))
      (node (ref "U23") (pin "25") (pinfunction "MIXIN_HI_25") (pintype "input"))
    )
    (net (code "241") (name "Net-(U22A-+IN)") (class "Default")
      (node (ref "R78") (pin "2") (pinfunction "2_2") (pintype "passive"))
      (node (ref "TP71") (pin "1") (pinfunction "1_1") (pintype "passive"))
      (node (ref "U22") (pin "3") (pinfunction "+IN_3") (pintype "input"))
      (node (ref "U23") (pin "4") (pinfunction "CLKOUT_4") (pintype "output"))
    )
    (net (code "242") (name "Net-(U22A--IN)") (class "Default")
      (node (ref "C84") (pin "1") (pinfunction "1_1") (pintype "passive"))
      (node (ref "R78") (pin "1") (pinfunction "1_1") (pintype "passive"))
      (node (ref "U22") (pin "1") (pinfunction "-IN_1") (pintype "input"))
    )
    (net (code "243") (name "Net-(U23-CPOUT)") (class "Default")
      (node (ref "C16") (pin "1") (pinfunction "1_1") (pintype "passive"))
      (node (ref "R11") (pin "1") (pinfunction "1_1") (pintype "passive"))
      (node (ref "U23") (pin "1") (pinfunction "CPOUT_1") (pintype "output"))
    )
    (net (code "244") (name "Net-(U23-LNAIN_HI)") (class "Default")
      (node (ref "L3") (pin "2") (pinfunction "2_2") (pintype "passive"))
      (node (ref "U23") (pin "19") (pinfunction "LNAIN_HI_19") (pintype "input"))
    )
    (net (code "245") (name "Net-(U24-BAUDSEL0)") (class "Default")
      (node (ref "R80") (pin "2") (pinfunction "2_2") (pintype "passive"))
      (node (ref "U24") (pin "37") (pinfunction "BAUDSEL0_37") (pintype "input"))
    )
    (net (code "246") (name "Net-(U24-BAUDSEL1)") (class "Default")
      (node (ref "R81") (pin "2") (pinfunction "2_2") (pintype "passive"))
      (node (ref "U24") (pin "14") (pinfunction "BAUDSEL1_14") (pintype "input"))
    )
    (net (code "247") (name "Net-(U24-PSE_SEL)") (class "Default")
      (node (ref "R29") (pin "2") (pinfunction "2_2") (pintype "passive"))
      (node (ref "U24") (pin "8") (pinfunction "PSE_SEL_8") (pintype "input"))
    )
    (net (code "248") (name "Net-(U24-RXD0)") (class "Default")
      (node (ref "R14") (pin "2") (pinfunction "2_2") (pintype "passive"))
      (node (ref "U24") (pin "42") (pinfunction "RXD0_42") (pintype "input"))
    )
    (net (code "249") (name "Net-(U24-TXD0)") (class "Default")
      (node (ref "R18") (pin "2") (pinfunction "2_2") (pintype "passive"))
      (node (ref "U24") (pin "44") (pinfunction "TXD0_44") (pintype "output"))
    )
    (net (code "250") (name "Net-(U24-VBAT)") (class "Default")
      (node (ref "C82") (pin "2") (pinfunction "2_2") (pintype "passive"))
      (node (ref "C85") (pin "+") (pinfunction "+_+") (pintype "passive"))
      (node (ref "R76") (pin "1") (pinfunction "1_1") (pintype "passive"))
      (node (ref "U24") (pin "18") (pinfunction "VBAT_18") (pintype "power_in"))
    )
    (net (code "251") (name "ON{slash}~{OFF}") (class "Default")
      (node (ref "C34") (pin "1") (pinfunction "1_1") (pintype "passive"))
      (node (ref "Q4") (pin "1") (pinfunction "G_1") (pintype "passive"))
      (node (ref "R46") (pin "2") (pinfunction "2_2") (pintype "passive"))
      (node (ref "R49") (pin "2") (pinfunction "2_2") (pintype "passive"))
      (node (ref "TP50") (pin "1") (pinfunction "1_1") (pintype "passive"))
      (node (ref "U14") (pin "1") (pinfunction "VCC_1") (pintype "power_in"))
      (node (ref "U16") (pin "8") (pinfunction "IO3_8") (pintype "bidirectional"))
    )
    (net (code "252") (name "OPD_PWR") (class "Default")
      (node (ref "J4") (pin "15") (pinfunction "15_15") (pintype "passive"))
      (node (ref "J4") (pin "16") (pinfunction "16_16") (pintype "passive"))
      (node (ref "R71") (pin "1") (pinfunction "1_1") (pintype "passive"))
    )
    (net (code "253") (name "OPD_SCL") (class "Default")
      (node (ref "J4") (pin "13") (pinfunction "13_13") (pintype "passive"))
      (node (ref "J4") (pin "14") (pinfunction "14_14") (pintype "passive"))
      (node (ref "R48") (pin "1") (pinfunction "1_1") (pintype "passive"))
    )
    (net (code "254") (name "OPD_SDA") (class "Default")
      (node (ref "J4") (pin "11") (pinfunction "11_11") (pintype "passive"))
      (node (ref "J4") (pin "12") (pinfunction "12_12") (pintype "passive"))
      (node (ref "R41") (pin "1") (pinfunction "1_1") (pintype "passive"))
    )
    (net (code "255") (name "OSC0_GND") (class "Default")
      (node (ref "C19") (pin "1") (pinfunction "1_1") (pintype "passive"))
      (node (ref "C22") (pin "1") (pinfunction "1_1") (pintype "passive"))
      (node (ref "U7") (pin "N15") (pinfunction "OSC0_GND_N15") (pintype "bidirectional"))
    )
    (net (code "256") (name "OSC0_IN") (class "Default")
      (node (ref "C19") (pin "2") (pinfunction "2_2") (pintype "passive"))
      (node (ref "R13") (pin "2") (pinfunction "2_2") (pintype "passive"))
      (node (ref "U7") (pin "P16") (pinfunction "OSC0_IN_P16") (pintype "bidirectional"))
      (node (ref "Y1") (pin "1") (pinfunction "X1_1") (pintype "passive"))
    )
    (net (code "257") (name "OSC0_OUT") (class "Default")
      (node (ref "C22") (pin "2") (pinfunction "2_2") (pintype "passive"))
      (node (ref "R13") (pin "1") (pinfunction "1_1") (pintype "passive"))
      (node (ref "U7") (pin "N16") (pinfunction "OSC0_OUT_N16") (pintype "bidirectional"))
      (node (ref "Y1") (pin "3") (pinfunction "X2_3") (pintype "passive"))
    )
    (net (code "258") (name "PB6{slash}SCL") (class "Default")
      (node (ref "TP67") (pin "1") (pinfunction "1_1") (pintype "passive"))
      (node (ref "U16") (pin "4") (pinfunction "IO0_4") (pintype "bidirectional"))
    )
    (net (code "259") (name "PB7{slash}SDA") (class "Default")
      (node (ref "TP68") (pin "1") (pinfunction "1_1") (pintype "passive"))
      (node (ref "U16") (pin "5") (pinfunction "IO1_5") (pintype "bidirectional"))
    )
    (net (code "260") (name "PEN-SCL-FILT") (class "Default")
      (node (ref "Q3") (pin "6") (pinfunction "D_6") (pintype "passive"))
      (node (ref "R37") (pin "2") (pinfunction "2_2") (pintype "passive"))
      (node (ref "R65") (pin "1") (pinfunction "1_1") (pintype "passive"))
      (node (ref "R67") (pin "1") (pinfunction "1_1") (pintype "passive"))
      (node (ref "R69") (pin "1") (pinfunction "1_1") (pintype "passive"))
      (node (ref "TP42") (pin "1") (pinfunction "1_1") (pintype "passive"))
      (node (ref "TP66") (pin "1") (pinfunction "1_1") (pintype "passive"))
      (node (ref "U16") (pin "15") (pinfunction "SCL_15") (pintype "input"))
    )
    (net (code "261") (name "PEN-SDA-FILT") (class "Default")
      (node (ref "Q3") (pin "4") (pinfunction "D_4") (pintype "passive"))
      (node (ref "R45") (pin "2") (pinfunction "2_2") (pintype "passive"))
      (node (ref "R66") (pin "2") (pinfunction "2_2") (pintype "passive"))
      (node (ref "R68") (pin "2") (pinfunction "2_2") (pintype "passive"))
      (node (ref "R70") (pin "2") (pinfunction "2_2") (pintype "passive"))
      (node (ref "TP41") (pin "1") (pinfunction "1_1") (pintype "passive"))
      (node (ref "TP65") (pin "1") (pinfunction "1_1") (pintype "passive"))
      (node (ref "U16") (pin "16") (pinfunction "SDA_16") (pintype "bidirectional"))
    )
    (net (code "262") (name "PMIC_PGOOD") (class "Default")
      (node (ref "TP110") (pin "P$1") (pinfunction "1_P$1") (pintype "bidirectional"))
      (node (ref "U4") (pin "2") (pinfunction "A_2") (pintype "bidirectional"))
      (node (ref "U7") (pin "N12") (pinfunction "PMIC_PGOOD_N12") (pintype "output"))
      (node (ref "U7") (pin "P11") (pinfunction "PWRONRSTN_P11") (pintype "bidirectional"))
    )
    (net (code "263") (name "POUT") (class "Default")
      (node (ref "TP64") (pin "1") (pinfunction "1_1") (pintype "passive"))
      (node (ref "U14") (pin "13") (pinfunction "POUT_13") (pintype "output"))
    )
    (net (code "264") (name "Q0") (class "Default")
      (node (ref "TP33") (pin "1") (pinfunction "1_1") (pintype "passive"))
      (node (ref "U23") (pin "11") (pinfunction "Q0_11") (pintype "output"))
      (node (ref "U7") (pin "B1") (pinfunction "MCASP0_AHCLKR_B1") (pintype "bidirectional"))
    )
    (net (code "265") (name "Q1") (class "Default")
      (node (ref "TP34") (pin "1") (pinfunction "1_1") (pintype "passive"))
      (node (ref "U23") (pin "10") (pinfunction "Q1_10") (pintype "output"))
      (node (ref "U7") (pin "B2") (pinfunction "MCASP0_AXR0_B2") (pintype "bidirectional"))
    )
    (net (code "266") (name "RESET#") (class "Default")
      (node (ref "JP1") (pin "1") (pinfunction "1_1") (pintype "passive"))
      (node (ref "TP109") (pin "P$1") (pinfunction "1_P$1") (pintype "bidirectional"))
      (node (ref "U4") (pin "4") (pinfunction "Y_4") (pintype "bidirectional"))
      (node (ref "U7") (pin "R11") (pinfunction "WARMRSTN_R11") (pintype "bidirectional"))
    )
    (net (code "267") (name "RF-IN") (class "Default")
      (node (ref "CM1") (pin "RF") (pinfunction "CENTER_RF") (pintype "passive"))
      (node (ref "U5") (pin "3") (pinfunction "RF_IN_3") (pintype "input"))
    )
    (net (code "268") (name "SPARE1") (class "Default")
      (node (ref "J4") (pin "10") (pinfunction "10_10") (pintype "passive"))
      (node (ref "J4") (pin "9") (pinfunction "9_9") (pintype "passive"))
      (node (ref "TP58") (pin "P$1") (pinfunction "1_P$1") (pintype "bidirectional"))
    )
    (net (code "269") (name "SPARE2") (class "Default")
      (node (ref "J4") (pin "7") (pinfunction "7_7") (pintype "passive"))
      (node (ref "J4") (pin "8") (pinfunction "8_8") (pintype "passive"))
      (node (ref "TP59") (pin "P$1") (pinfunction "1_P$1") (pintype "bidirectional"))
    )
    (net (code "270") (name "SPARE3") (class "Default")
      (node (ref "J4") (pin "5") (pinfunction "5_5") (pintype "passive"))
      (node (ref "J4") (pin "6") (pinfunction "6_6") (pintype "passive"))
      (node (ref "TP60") (pin "P$1") (pinfunction "1_P$1") (pintype "bidirectional"))
    )
    (net (code "271") (name "SPARE4") (class "Default")
      (node (ref "J4") (pin "3") (pinfunction "3_3") (pintype "passive"))
      (node (ref "J4") (pin "4") (pinfunction "4_4") (pintype "passive"))
      (node (ref "TP61") (pin "P$1") (pinfunction "1_P$1") (pintype "bidirectional"))
    )
    (net (code "272") (name "STQ-EN") (class "Default")
      (node (ref "R79") (pin "2") (pinfunction "2_2") (pintype "passive"))
      (node (ref "TP18") (pin "P$1") (pinfunction "1_P$1") (pintype "bidirectional"))
      (node (ref "U20") (pin "3") (pinfunction "EN_3") (pintype "input"))
      (node (ref "U7") (pin "E15") (pinfunction "MII1_RX_ER_E15") (pintype "bidirectional"))
    )
    (net (code "273") (name "STQ-RF") (class "Default")
      (node (ref "U19") (pin "8") (pinfunction "PORT1_8") (pintype "passive"))
      (node (ref "U24") (pin "32") (pinfunction "RFIN_32") (pintype "input"))
    )
    (net (code "274") (name "STQ_UART2_RX") (class "Default")
      (node (ref "JP2") (pin "2") (pinfunction "2_2") (pintype "passive"))
      (node (ref "R18") (pin "1") (pinfunction "1_1") (pintype "passive"))
      (node (ref "TP147") (pin "P$1") (pinfunction "1_P$1") (pintype "bidirectional"))
      (node (ref "TP27") (pin "P$1") (pinfunction "1_P$1") (pintype "passive"))
      (node (ref "U7") (pin "H16") (pinfunction "MII1_TX_CLK_H16") (pintype "bidirectional"))
    )
    (net (code "275") (name "STQ_UART2_TX") (class "Default")
      (node (ref "JP2") (pin "1") (pinfunction "1_1") (pintype "passive"))
      (node (ref "R14") (pin "1") (pinfunction "1_1") (pintype "passive"))
      (node (ref "TP6") (pin "P$1") (pinfunction "1_P$1") (pintype "passive"))
      (node (ref "U7") (pin "E16") (pinfunction "MII1_RX_CLK_E16") (pintype "bidirectional"))
    )
    (net (code "276") (name "UART0_RX") (class "Default")
      (node (ref "J1") (pin "12") (pinfunction "CARD-RX_12") (pintype "passive"))
      (node (ref "TP146") (pin "P$1") (pinfunction "1_P$1") (pintype "bidirectional"))
      (node (ref "U7") (pin "A12") (pinfunction "UART0_RXD_A12") (pintype "bidirectional"))
    )
    (net (code "277") (name "UART0_TX") (class "Default")
      (node (ref "J1") (pin "13") (pinfunction "CARD-TX_13") (pintype "passive"))
      (node (ref "TP142") (pin "P$1") (pinfunction "1_P$1") (pintype "bidirectional"))
      (node (ref "U7") (pin "B12") (pinfunction "UART0_TXD_B12") (pintype "bidirectional"))
    )
    (net (code "278") (name "USB_CLI_N") (class "Default")
      (node (ref "J1") (pin "5") (pinfunction "DEVICE-D-_5") (pintype "passive"))
      (node (ref "U1") (pin "1") (pinfunction "I1_1") (pintype "bidirectional"))
      (node (ref "U7") (pin "K16") (pinfunction "USB0_DM_K16") (pintype "bidirectional"))
    )
    (net (code "279") (name "USB_CLI_P") (class "Default")
      (node (ref "J1") (pin "4") (pinfunction "DEVICE-D+_4") (pintype "passive"))
      (node (ref "U1") (pin "3") (pinfunction "I2_3") (pintype "bidirectional"))
      (node (ref "U7") (pin "K15") (pinfunction "USB0_DP_K15") (pintype "bidirectional"))
    )
    (net (code "280") (name "USB_CLI_VBUS") (class "Default")
      (node (ref "FB2") (pin "1") (pinfunction "1_1") (pintype "passive"))
      (node (ref "J1") (pin "1") (pinfunction "VBUSP_1") (pintype "passive"))
      (node (ref "J1") (pin "2") (pinfunction "VBUSP_2") (pintype "passive"))
    )
    (net (code "281") (name "USB_HO_N") (class "Default")
      (node (ref "J1") (pin "8") (pinfunction "HOST-D-_8") (pintype "passive"))
      (node (ref "U1") (pin "6") (pinfunction "I4_6") (pintype "bidirectional"))
      (node (ref "U7") (pin "L16") (pinfunction "USB1_DM_L16") (pintype "bidirectional"))
    )
    (net (code "282") (name "USB_HO_PX") (class "Default")
      (node (ref "J1") (pin "7") (pinfunction "HOST-D+_7") (pintype "passive"))
      (node (ref "U1") (pin "4") (pinfunction "I3_4") (pintype "bidirectional"))
      (node (ref "U7") (pin "L15") (pinfunction "USB1_DP_L15") (pintype "bidirectional"))
    )
    (net (code "283") (name "USB_HO_VBUS") (class "Default")
      (node (ref "FB1") (pin "2") (pinfunction "2_2") (pintype "passive"))
      (node (ref "J1") (pin "17") (pinfunction "DEBUG-0_17") (pintype "passive"))
    )
    (net (code "284") (name "VBUS") (class "Default")
      (node (ref "J4") (pin "21") (pinfunction "21_21") (pintype "passive"))
      (node (ref "J4") (pin "22") (pinfunction "22_22") (pintype "passive"))
      (node (ref "J4") (pin "23") (pinfunction "23_23") (pintype "passive"))
      (node (ref "J4") (pin "24") (pinfunction "24_24") (pintype "passive"))
      (node (ref "J4") (pin "25") (pinfunction "25_25") (pintype "passive"))
      (node (ref "J4") (pin "26") (pinfunction "26_26") (pintype "passive"))
      (node (ref "Q6") (pin "4") (pinfunction "S_4") (pintype "passive"))
      (node (ref "R52") (pin "2") (pinfunction "2_2") (pintype "passive"))
    )
    (net (code "285") (name "VBUSP") (class "Default")
      (node (ref "C33") (pin "2") (pinfunction "2_2") (pintype "passive"))
      (node (ref "C37") (pin "1") (pinfunction "1_1") (pintype "passive"))
      (node (ref "C38") (pin "1") (pinfunction "1_1") (pintype "passive"))
      (node (ref "Q5") (pin "1") (pinfunction "D_1") (pintype "passive"))
      (node (ref "Q5") (pin "2") (pinfunction "D_2") (pintype "passive"))
      (node (ref "Q5") (pin "5") (pinfunction "D_5") (pintype "passive"))
      (node (ref "Q5") (pin "6") (pinfunction "D_6") (pintype "passive"))
      (node (ref "R34") (pin "2") (pinfunction "2_2") (pintype "passive"))
      (node (ref "R61") (pin "2") (pinfunction "2_2") (pintype "passive"))
      (node (ref "TP55") (pin "1") (pinfunction "1_1") (pintype "passive"))
      (node (ref "U15") (pin "2") (pinfunction "VIN_2") (pintype "power_in"))
      (node (ref "U15") (pin "3") (pinfunction "VIN_3") (pintype "power_in"))
      (node (ref "U15") (pin "4") (pinfunction "EN_4") (pintype "input"))
      (node (ref "U15") (pin "8") (pinfunction "VIN_8") (pintype "power_in"))
    )
    (net (code "286") (name "VDD") (class "Default")
      (node (ref "C15") (pin "1") (pinfunction "1_1") (pintype "passive"))
      (node (ref "C7") (pin "1") (pinfunction "1_1") (pintype "passive"))
      (node (ref "R7") (pin "2") (pinfunction "2_2") (pintype "passive"))
      (node (ref "TP3") (pin "P$1") (pinfunction "1_P$1") (pintype "bidirectional"))
      (node (ref "U2") (pin "5") (pinfunction "IN_5") (pintype "input"))
      (node (ref "U7") (pin "K6") (pinfunction "SYS_VOUT_K6") (pintype "power_in"))
      (node (ref "U7") (pin "K7") (pinfunction "SYS_VOUT_K7") (pintype "power_in"))
      (node (ref "U7") (pin "L6") (pinfunction "SYS_VOUT_L6") (pintype "power_in"))
      (node (ref "U7") (pin "L7") (pinfunction "SYS_VOUT_L7") (pintype "power_in"))
    )
    (net (code "287") (name "VIN_USB") (class "Default")
      (node (ref "C13") (pin "1") (pinfunction "1_1") (pintype "passive"))
      (node (ref "C4") (pin "1") (pinfunction "1_1") (pintype "passive"))
      (node (ref "FB2") (pin "2") (pinfunction "2_2") (pintype "passive"))
      (node (ref "TP2") (pin "P$1") (pinfunction "1_P$1") (pintype "bidirectional"))
      (node (ref "U1") (pin "5") (pinfunction "VCC_5") (pintype "power_in"))
      (node (ref "U7") (pin "J16") (pinfunction "USB0_VBUS_J16") (pintype "bidirectional"))
      (node (ref "U7") (pin "P9") (pinfunction "VIN_USB_P9") (pintype "power_in"))
      (node (ref "U7") (pin "R9") (pinfunction "VIN_USB_R9") (pintype "power_in"))
      (node (ref "U7") (pin "T9") (pinfunction "VIN_USB_T9") (pintype "power_in"))
    )
    (net (code "288") (name "VOUT_USB") (class "Default")
      (node (ref "C1") (pin "1") (pinfunction "1_1") (pintype "passive"))
      (node (ref "FB1") (pin "1") (pinfunction "1_1") (pintype "passive"))
      (node (ref "TP1") (pin "P$1") (pinfunction "1_P$1") (pintype "bidirectional"))
      (node (ref "U2") (pin "1") (pinfunction "OUT_1") (pintype "output"))
      (node (ref "U7") (pin "M15") (pinfunction "USB1_VBUS_M15") (pintype "bidirectional"))
    )
    (net (code "289") (name "VPD") (class "Default")
      (node (ref "C39") (pin "2") (pinfunction "2_2") (pintype "passive"))
      (node (ref "R32") (pin "2") (pinfunction "2_2") (pintype "passive"))
      (node (ref "R36") (pin "2") (pinfunction "2_2") (pintype "passive"))
      (node (ref "R44") (pin "2") (pinfunction "2_2") (pintype "passive"))
      (node (ref "R53") (pin "2") (pinfunction "2_2") (pintype "passive"))
      (node (ref "R55") (pin "2") (pinfunction "2_2") (pintype "passive"))
      (node (ref "R57") (pin "2") (pinfunction "2_2") (pintype "passive"))
      (node (ref "R71") (pin "2") (pinfunction "2_2") (pintype "passive"))
      (node (ref "R72") (pin "2") (pinfunction "2_2") (pintype "passive"))
      (node (ref "TP63") (pin "1") (pinfunction "1_1") (pintype "passive"))
      (node (ref "U12") (pin "5") (pinfunction "VDD_5") (pintype "power_in"))
      (node (ref "U13") (pin "5") (pinfunction "VDD_5") (pintype "power_in"))
      (node (ref "U16") (pin "14") (pinfunction "V+_14") (pintype "power_in"))
    )
    (net (code "290") (name "unconnected-(J1-NRST-Pad10)") (class "Default")
      (node (ref "J1") (pin "10") (pinfunction "NRST_10") (pintype "passive"))
    )
    (net (code "291") (name "unconnected-(J1-SWCLK-Pad15)") (class "Default")
      (node (ref "J1") (pin "15") (pinfunction "SWCLK_15") (pintype "passive"))
    )
    (net (code "292") (name "unconnected-(J1-SWDIO-Pad14)") (class "Default")
      (node (ref "J1") (pin "14") (pinfunction "SWDIO_14") (pintype "passive"))
    )
    (net (code "293") (name "unconnected-(J1-SWO-Pad16)") (class "Default")
      (node (ref "J1") (pin "16") (pinfunction "SWO_16") (pintype "passive"))
    )
    (net (code "294") (name "unconnected-(J1-VTARGET-Pad11)") (class "Default")
      (node (ref "J1") (pin "11") (pinfunction "VTARGET_11") (pintype "passive"))
    )
    (net (code "295") (name "unconnected-(R8-11-Pad1)") (class "Default")
      (node (ref "R8") (pin "1") (pinfunction "11_1") (pintype "passive"))
    )
    (net (code "296") (name "unconnected-(R9-11-Pad1)") (class "Default")
      (node (ref "R9") (pin "1") (pinfunction "11_1") (pintype "passive"))
    )
    (net (code "297") (name "unconnected-(R9-99-Pad9)") (class "Default")
      (node (ref "R9") (pin "9") (pinfunction "99_9") (pintype "passive"))
    )
    (net (code "298") (name "unconnected-(R10-44-Pad4)") (class "Default")
      (node (ref "R10") (pin "4") (pinfunction "44_4") (pintype "passive"))
    )
    (net (code "299") (name "unconnected-(R10-66-Pad6)") (class "Default")
      (node (ref "R10") (pin "6") (pinfunction "66_6") (pintype "passive"))
    )
    (net (code "300") (name "unconnected-(R10-77-Pad7)") (class "Default")
      (node (ref "R10") (pin "7") (pinfunction "77_7") (pintype "passive"))
    )
    (net (code "301") (name "unconnected-(R24-11-Pad1)") (class "Default")
      (node (ref "R24") (pin "1") (pinfunction "11_1") (pintype "passive"))
    )
    (net (code "302") (name "unconnected-(R24-77-Pad7)") (class "Default")
      (node (ref "R24") (pin "7") (pinfunction "77_7") (pintype "passive"))
    )
    (net (code "303") (name "unconnected-(R25-88-Pad8)") (class "Default")
      (node (ref "R25") (pin "8") (pinfunction "88_8") (pintype "passive"))
    )
    (net (code "304") (name "unconnected-(U7C-GPMC_AD14-PadT6)") (class "Default")
      (node (ref "U7") (pin "T6") (pinfunction "GPMC_AD14_T6") (pintype "bidirectional"))
    )
    (net (code "305") (name "unconnected-(U7C-GPMC_AD15-PadP7)") (class "Default")
      (node (ref "U7") (pin "P7") (pinfunction "GPMC_AD15_P7") (pintype "bidirectional"))
    )
    (net (code "306") (name "unconnected-(U7C-UART1_CTSN-PadB10)") (class "Default")
      (node (ref "U7") (pin "B10") (pinfunction "UART1_CTSN_B10") (pintype "bidirectional"))
    )
    (net (code "307") (name "unconnected-(U7C-UART1_RTSN-PadA10)") (class "Default")
      (node (ref "U7") (pin "A10") (pinfunction "UART1_RTSN_A10") (pintype "bidirectional"))
    )
    (net (code "308") (name "unconnected-(U18-I3-Pad4)") (class "Default")
      (node (ref "U18") (pin "4") (pinfunction "I3_4") (pintype "bidirectional"))
    )
    (net (code "309") (name "unconnected-(U23-ADC_CLKIN-Pad5)") (class "Default")
      (node (ref "U23") (pin "5") (pinfunction "ADC_CLKIN_5") (pintype "input"))
    )
    (net (code "310") (name "unconnected-(U23-ANAINOUT-Pad16)") (class "Default")
      (node (ref "U23") (pin "16") (pinfunction "ANAINOUT_16") (pintype "output"))
    )
    (net (code "311") (name "unconnected-(U23-ANAIPOUT-Pad15)") (class "Default")
      (node (ref "U23") (pin "15") (pinfunction "ANAIPOUT_15") (pintype "output"))
    )
    (net (code "312") (name "unconnected-(U23-LNAOUT_LO-Pad23)") (class "Default")
      (node (ref "U23") (pin "23") (pinfunction "LNAOUT_LO_23") (pintype "output"))
    )
    (net (code "313") (name "~{FAULT}") (class "Default")
      (node (ref "Q2") (pin "3") (pinfunction "D_3") (pintype "passive"))
      (node (ref "R32") (pin "1") (pinfunction "1_1") (pintype "passive"))
      (node (ref "TP45") (pin "1") (pinfunction "1_1") (pintype "passive"))
      (node (ref "U16") (pin "7") (pinfunction "IO2_7") (pintype "bidirectional"))
    )
    (net (code "314") (name "~{SD}") (class "Default")
      (node (ref "J4") (pin "39") (pinfunction "39_39") (pintype "passive"))
      (node (ref "J4") (pin "40") (pinfunction "40_40") (pintype "passive"))
    )
  )
)
